# PX4FMUv2_4_5.net
KiCad netlist of a schematic drawn in EAGLE
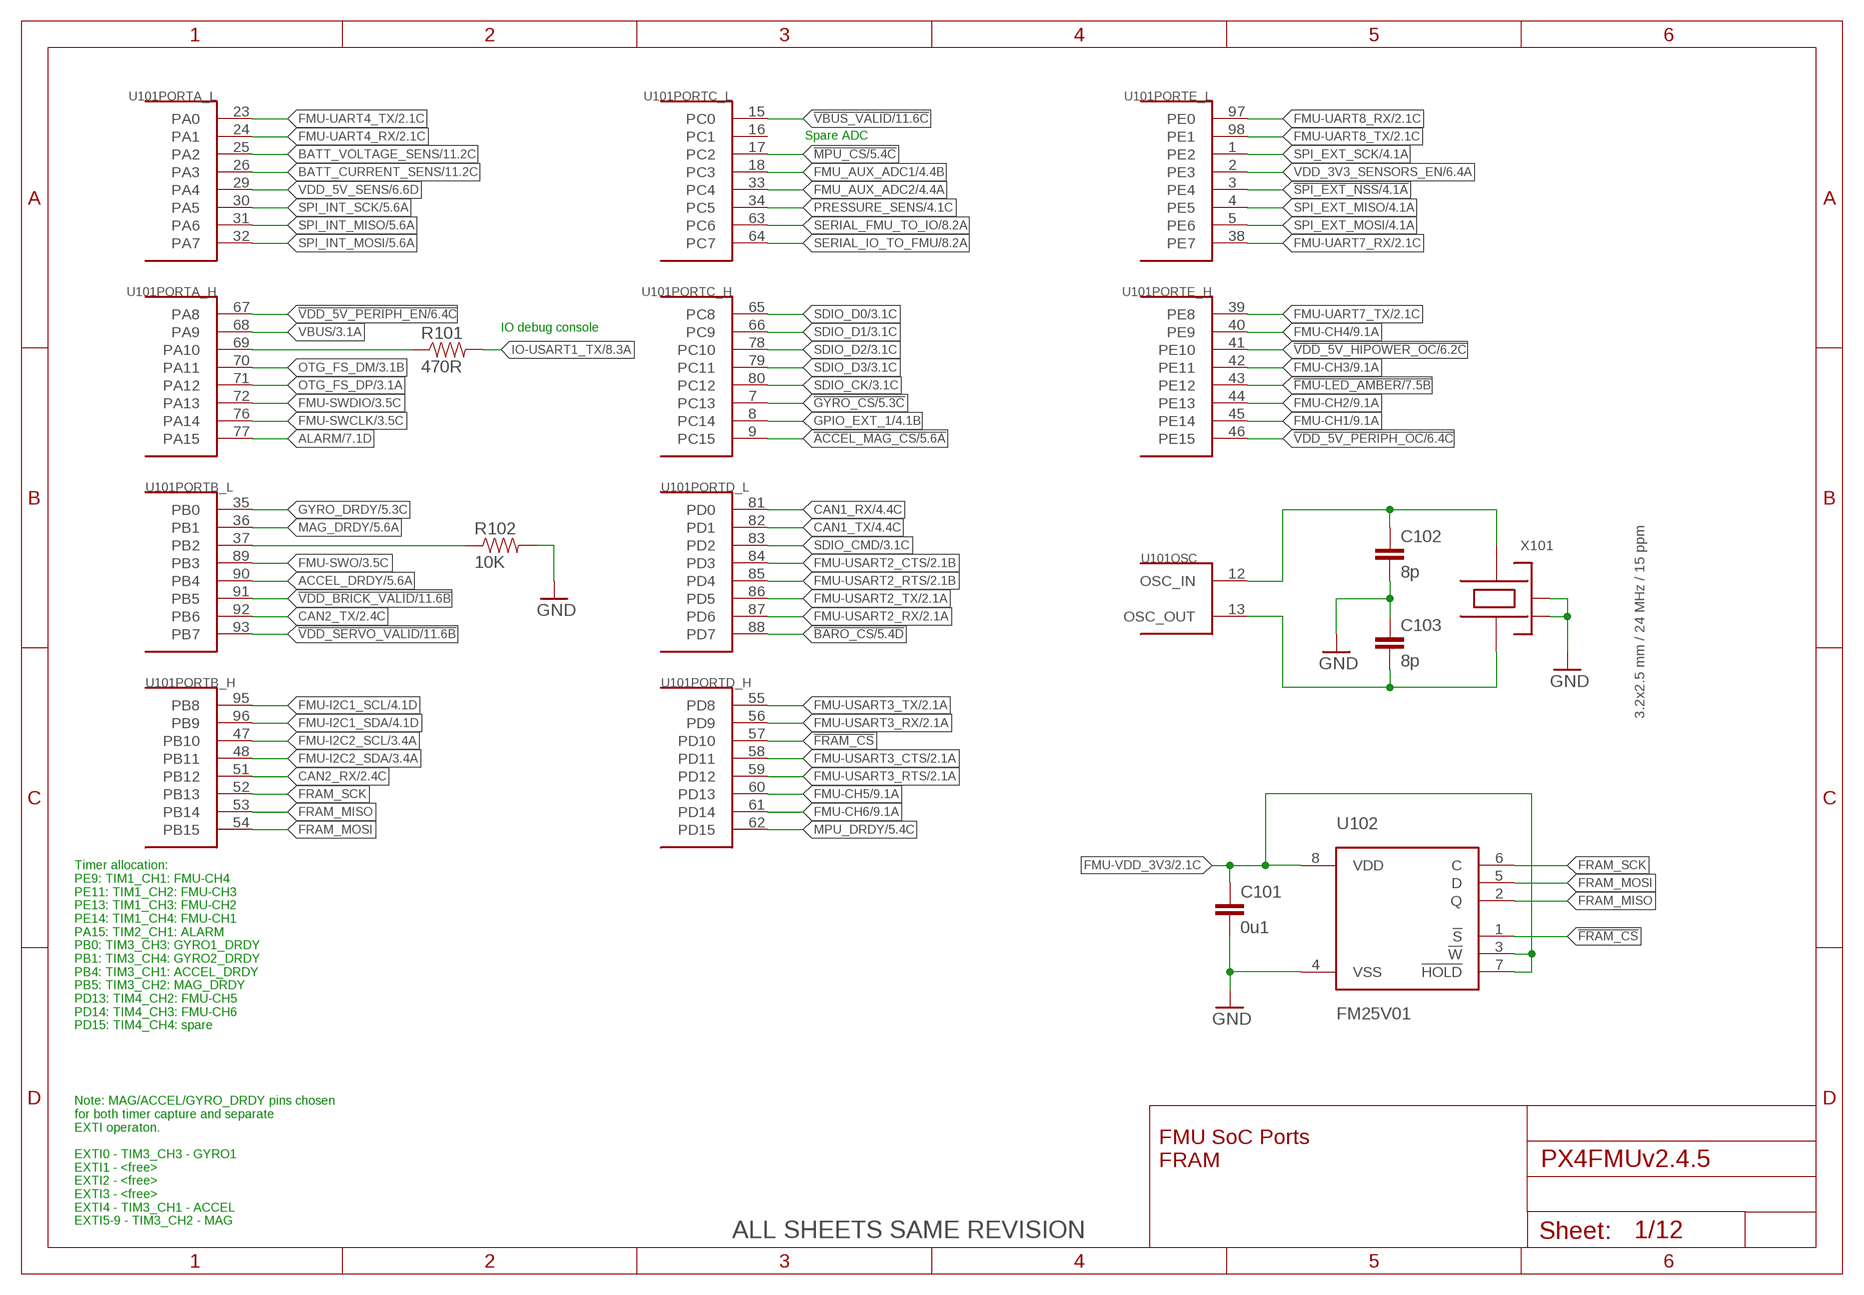
[diagram p0: schematic, sheet 1]
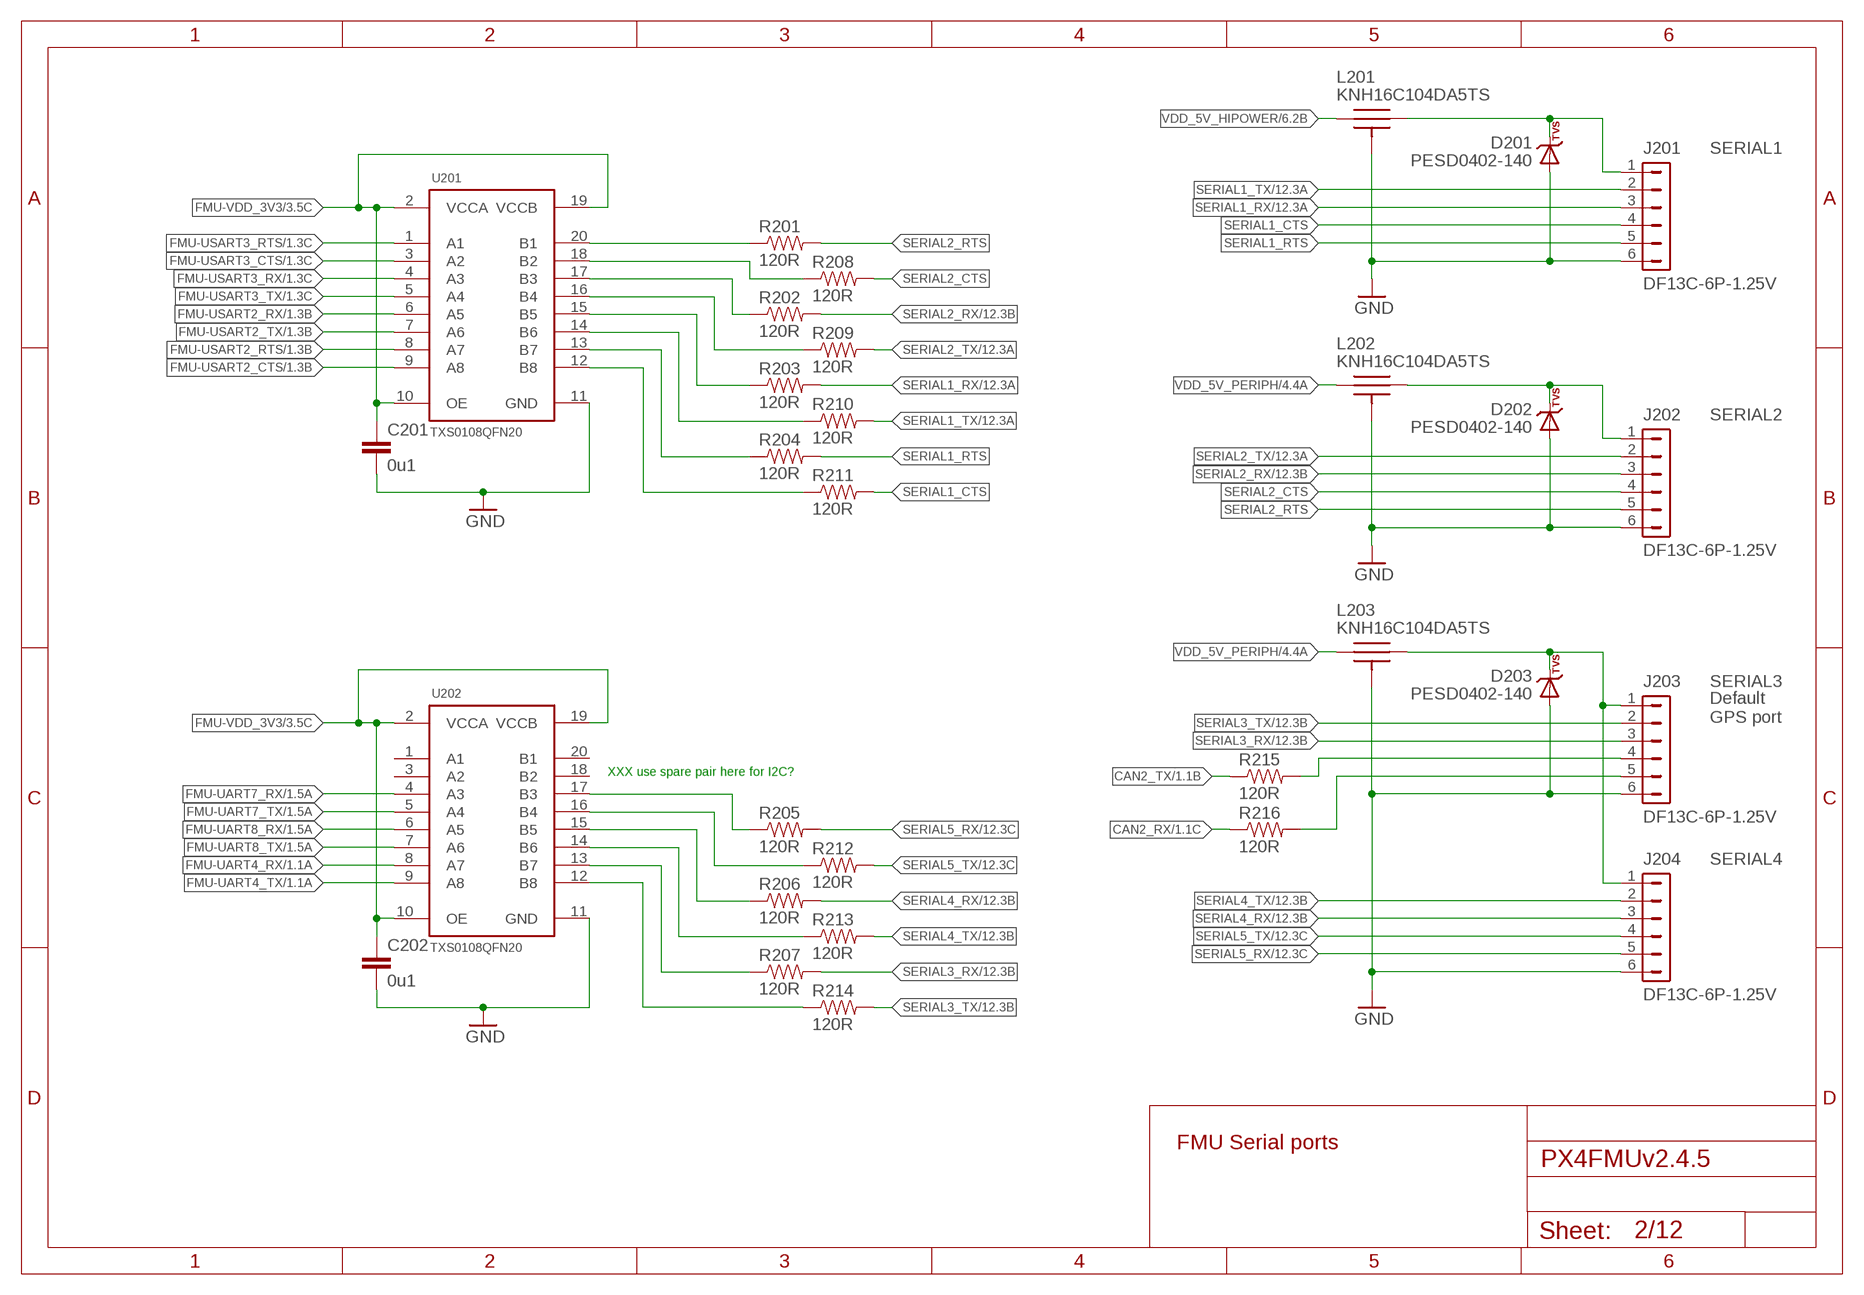
[diagram p1: schematic, sheet 2]
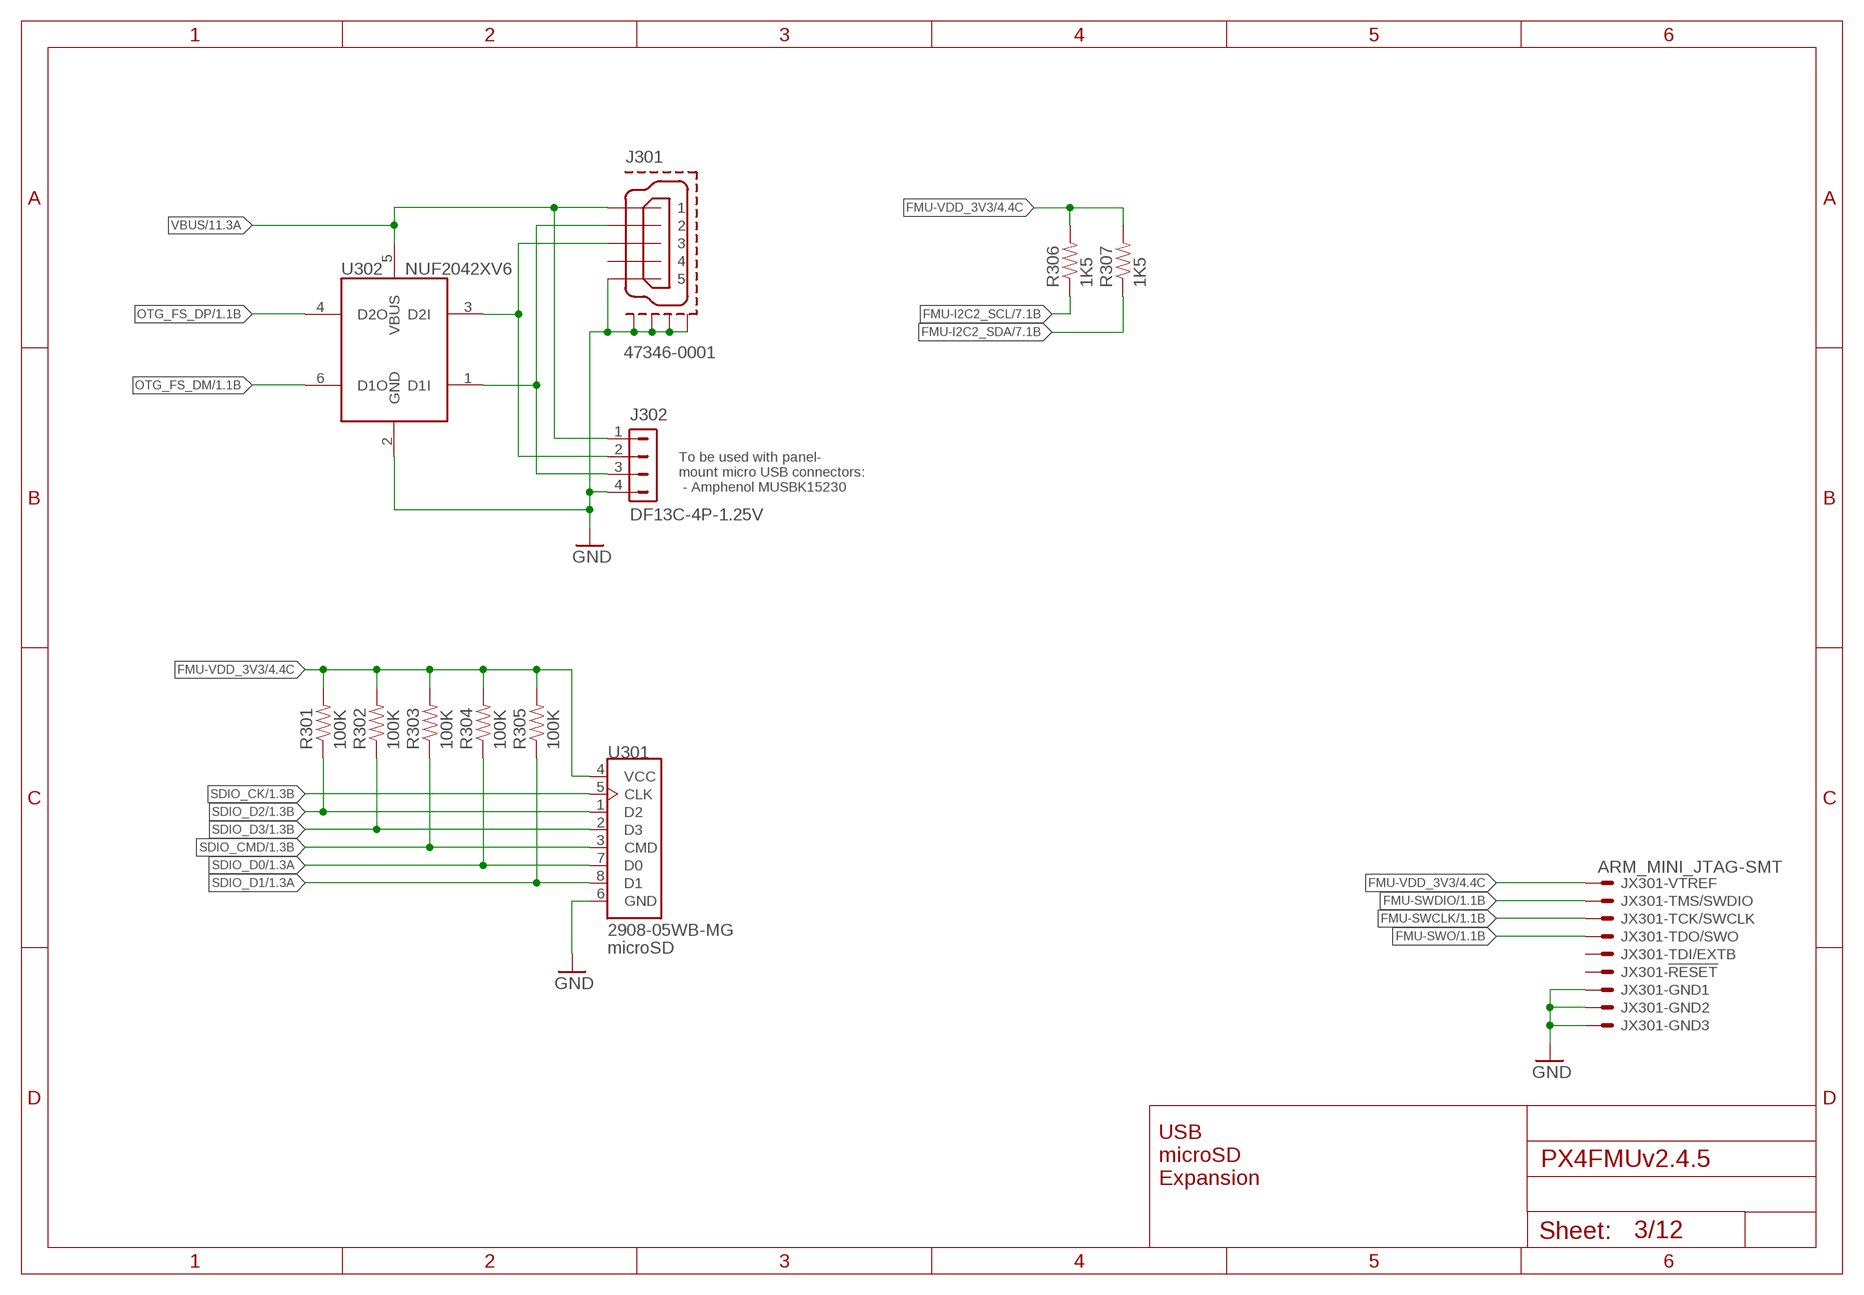
[diagram p2: schematic, sheet 3]
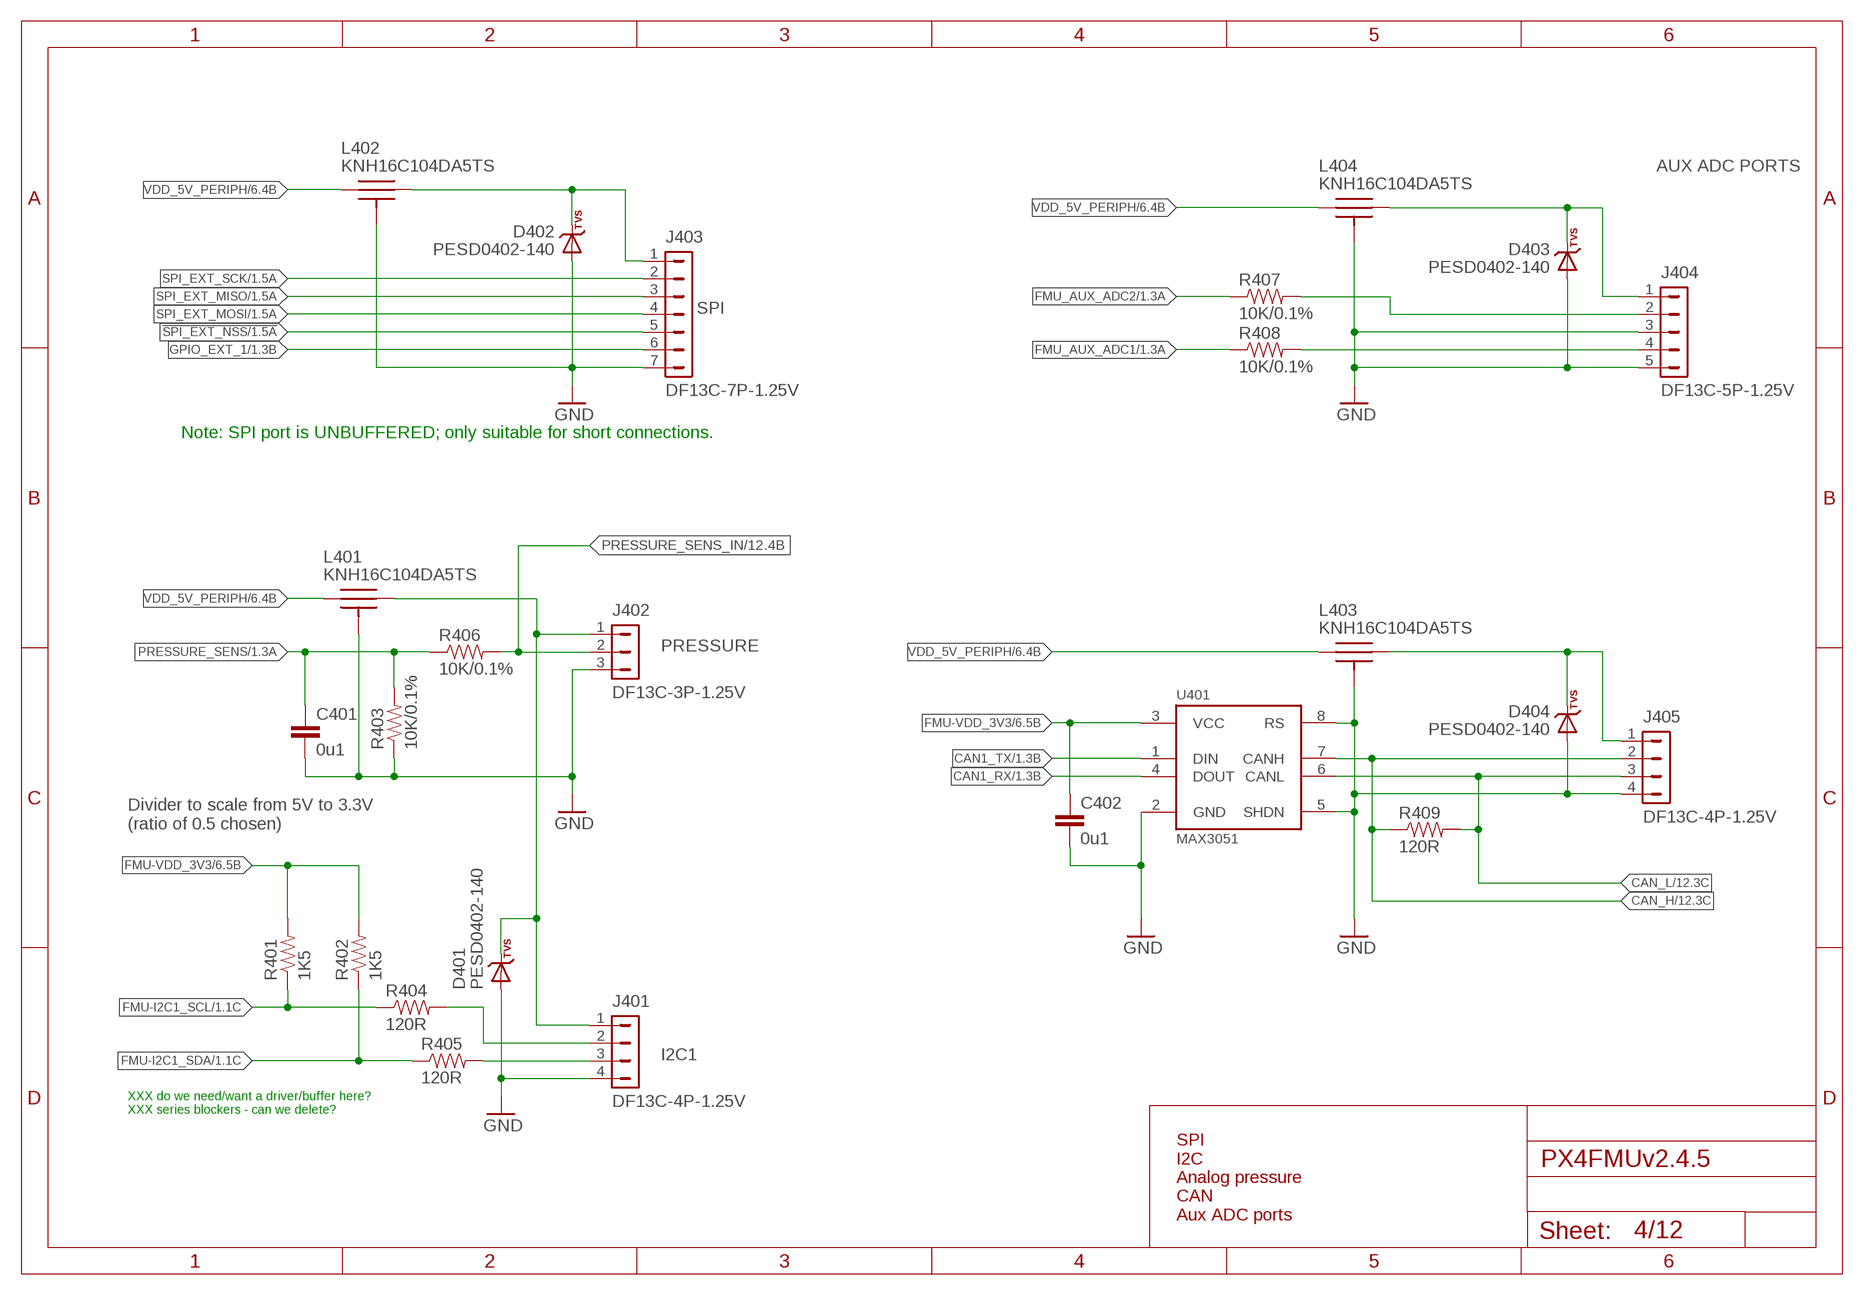
[diagram p3: schematic, sheet 4]
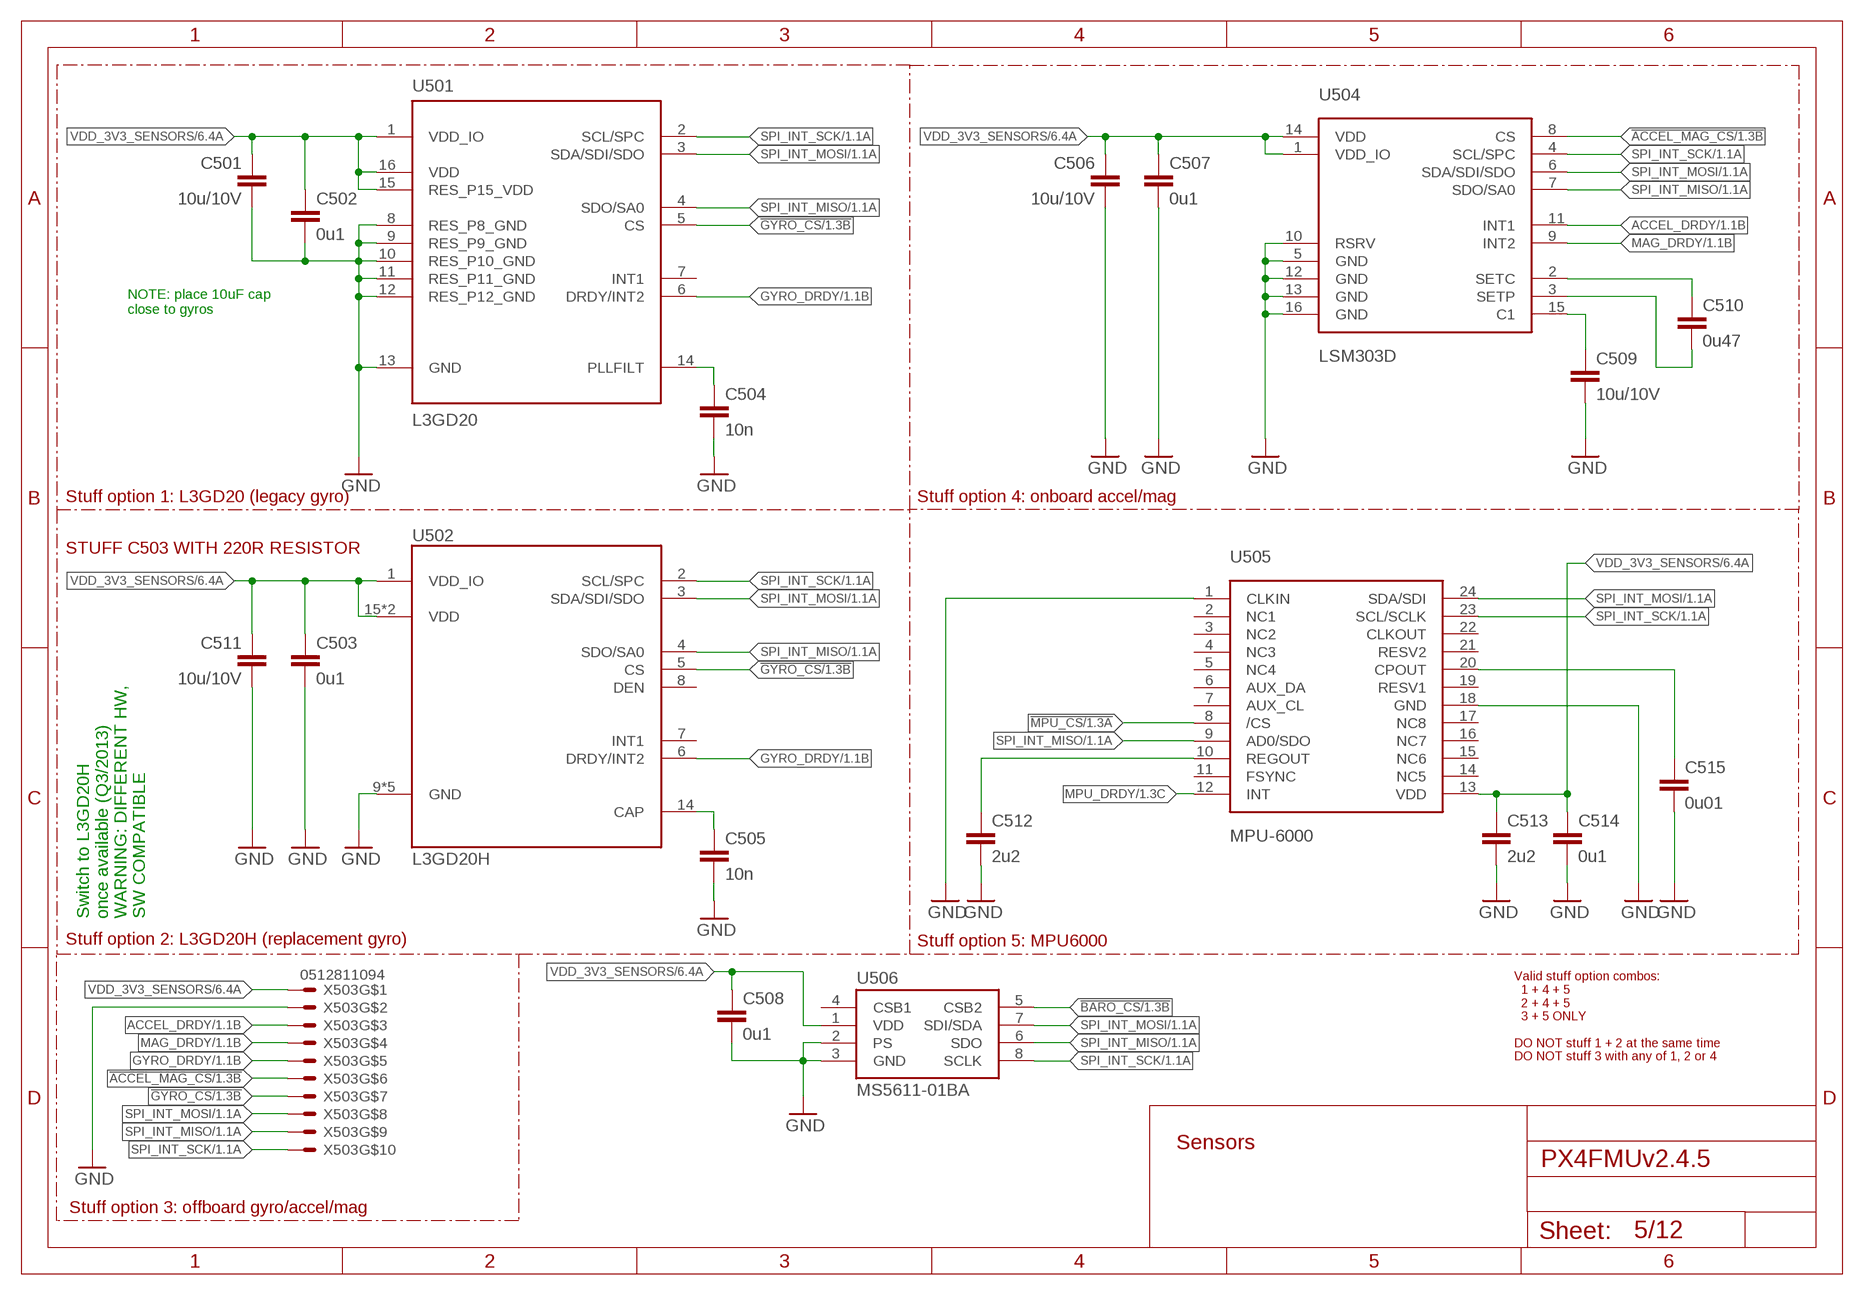
[diagram p4: schematic, sheet 5]
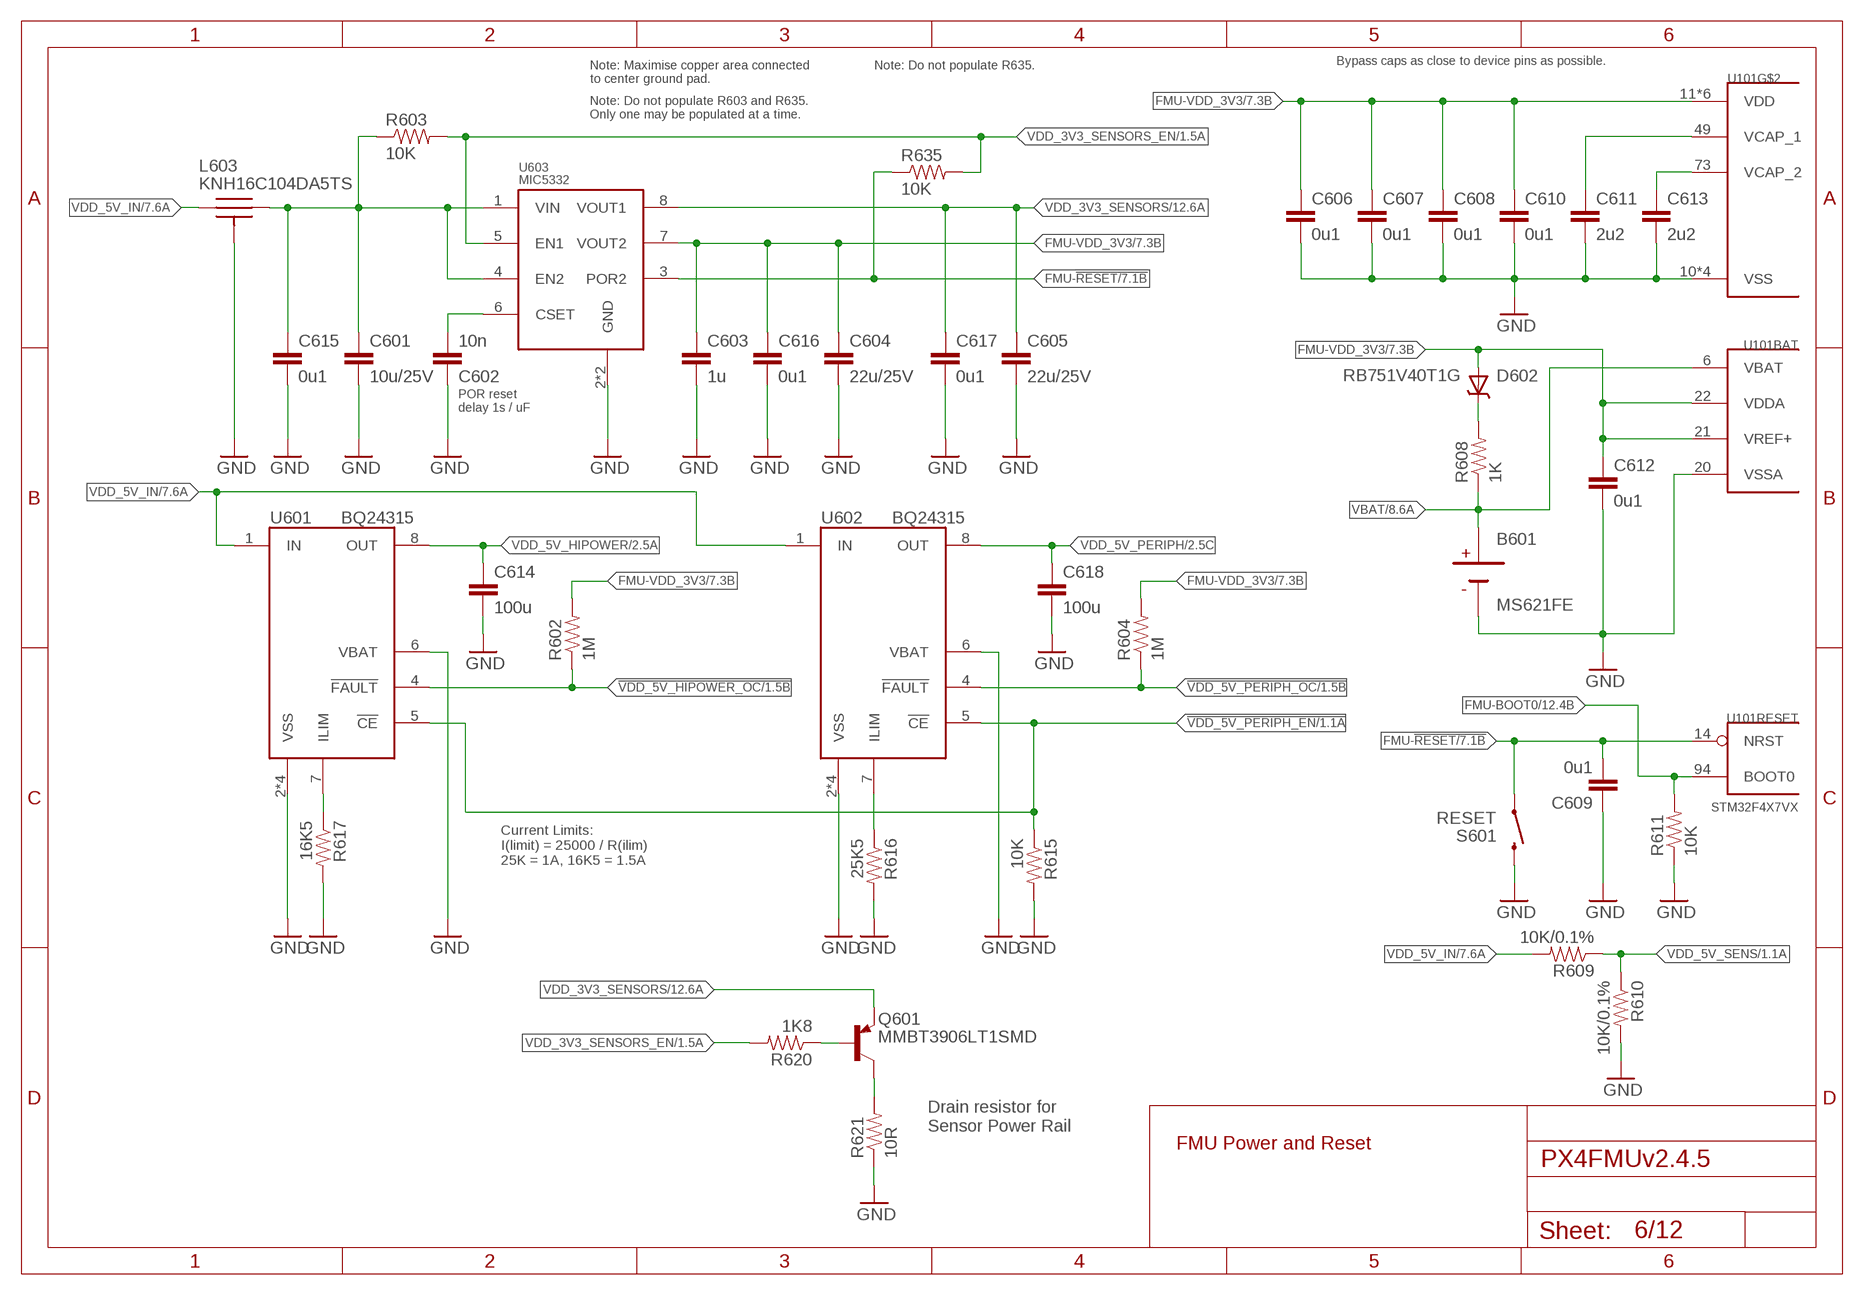
[diagram p5: schematic, sheet 6]
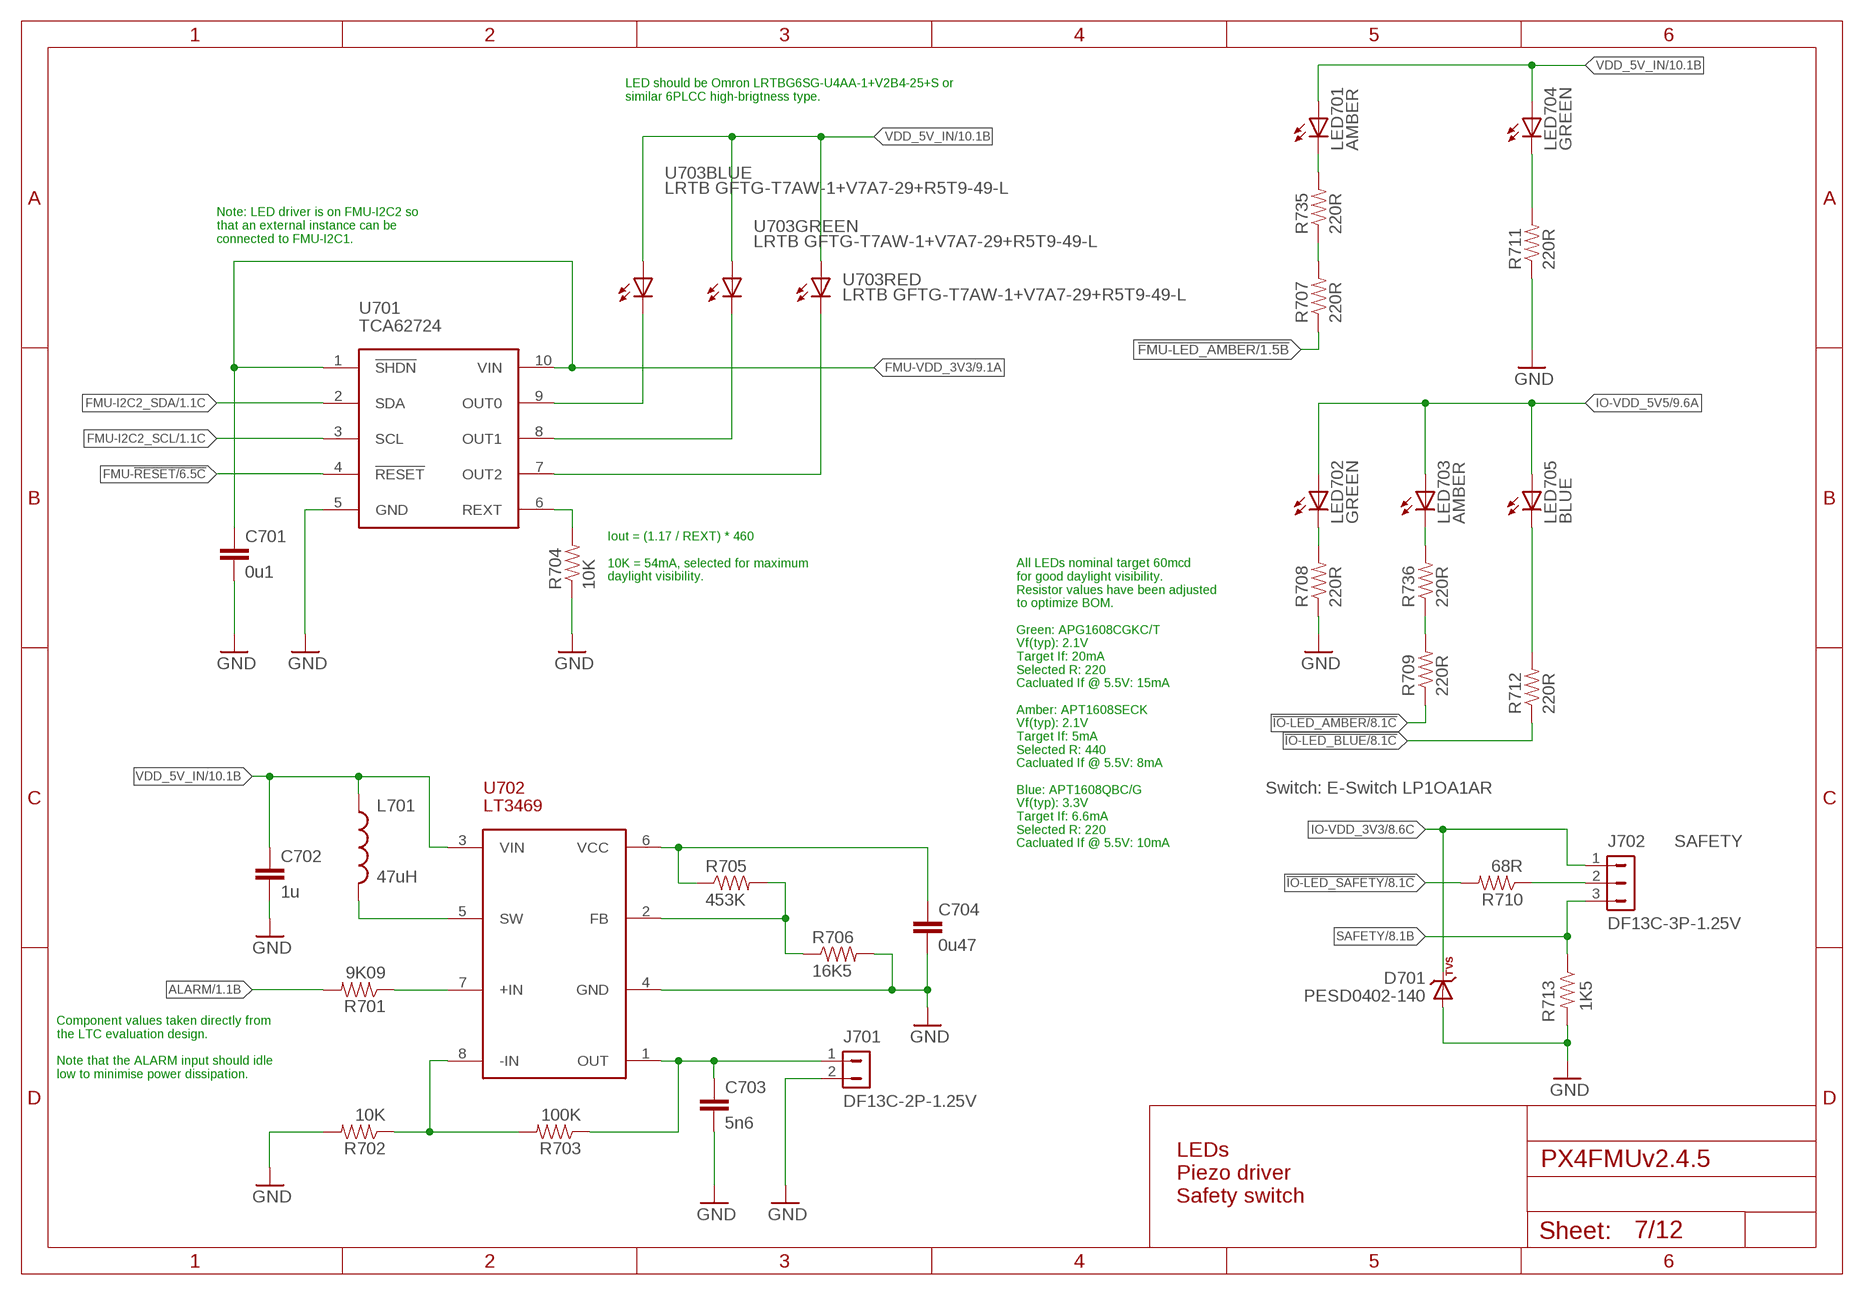
[diagram p6: schematic, sheet 7]
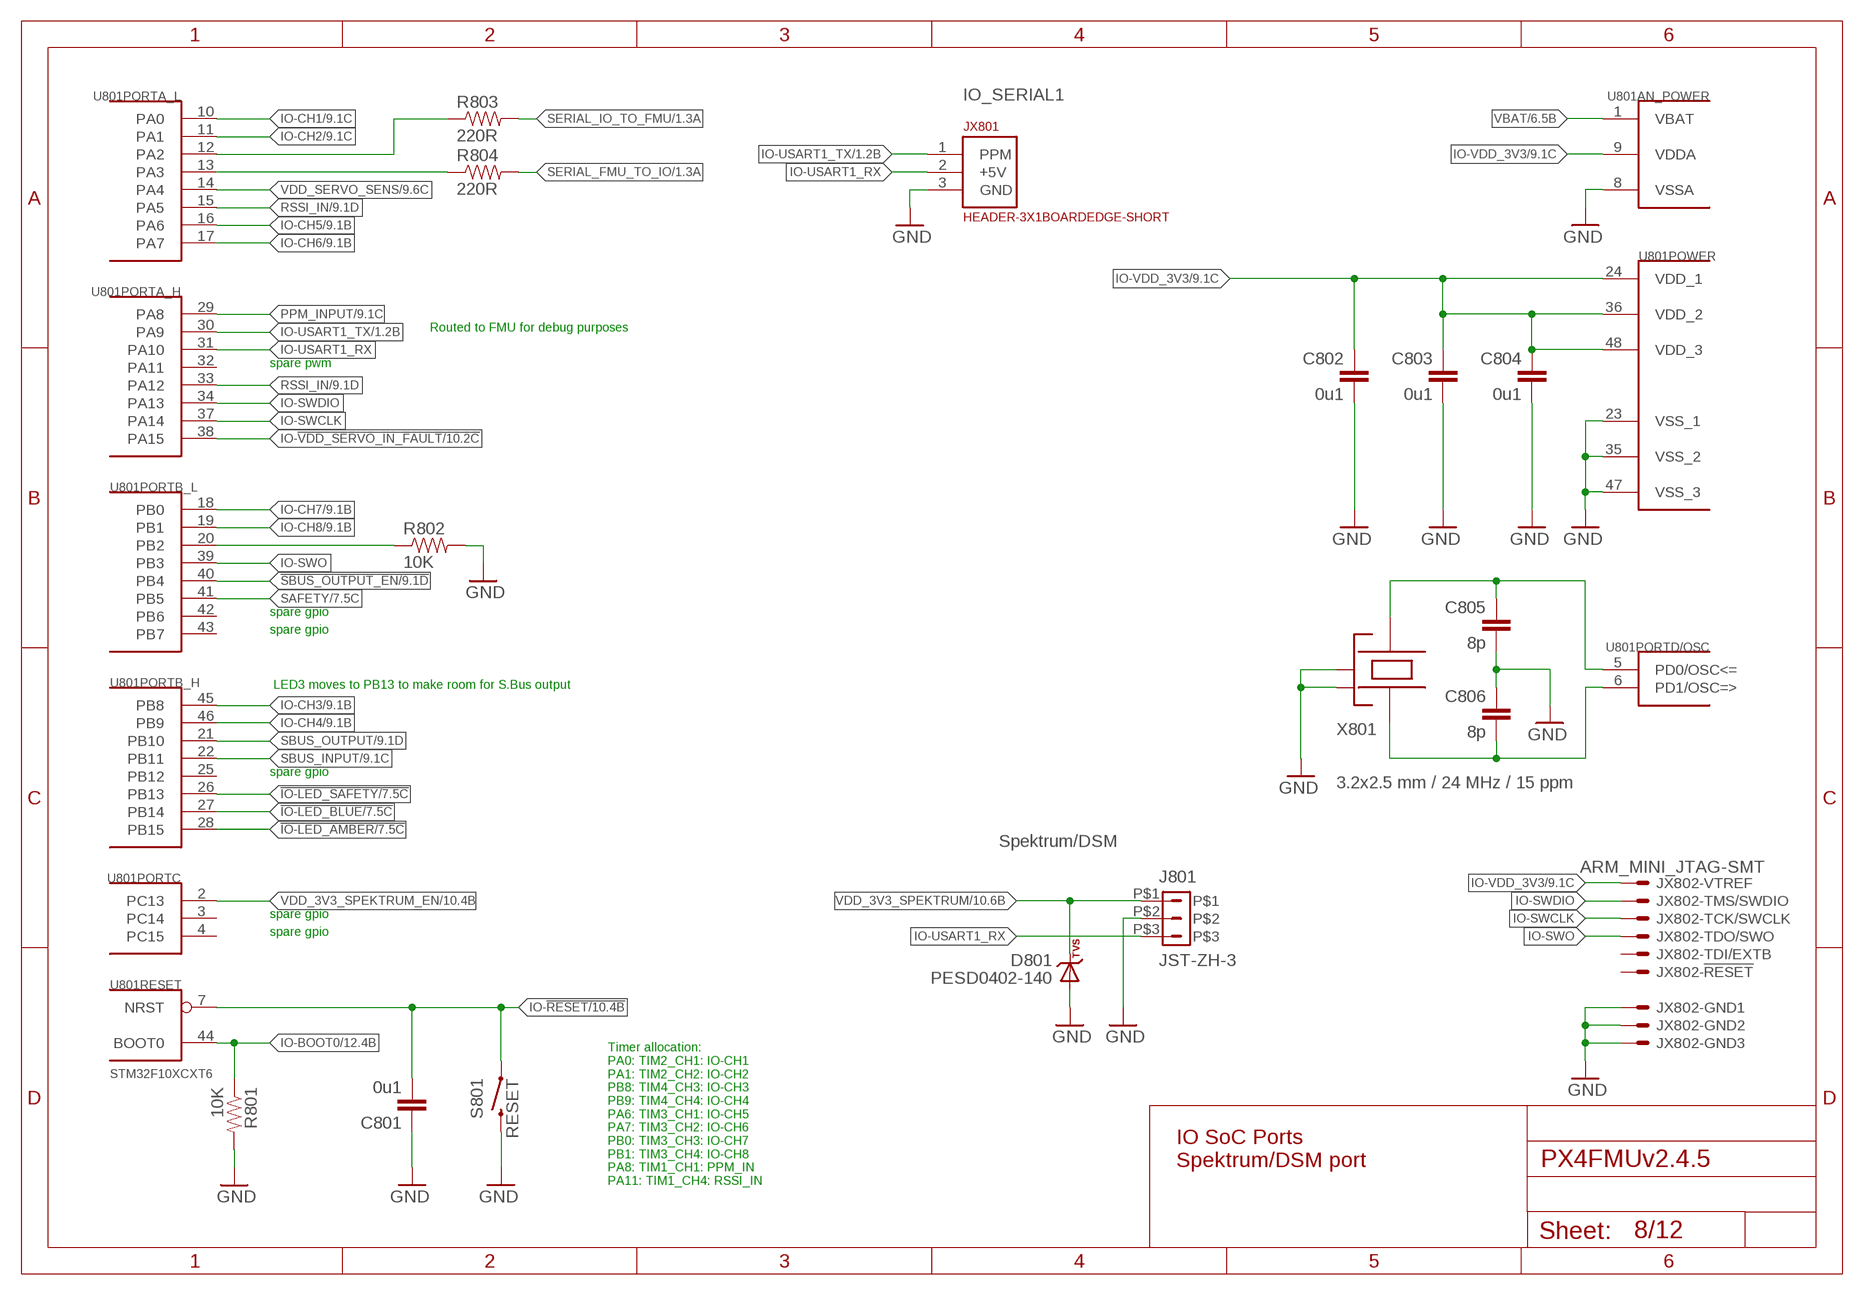
[diagram p7: schematic, sheet 8]
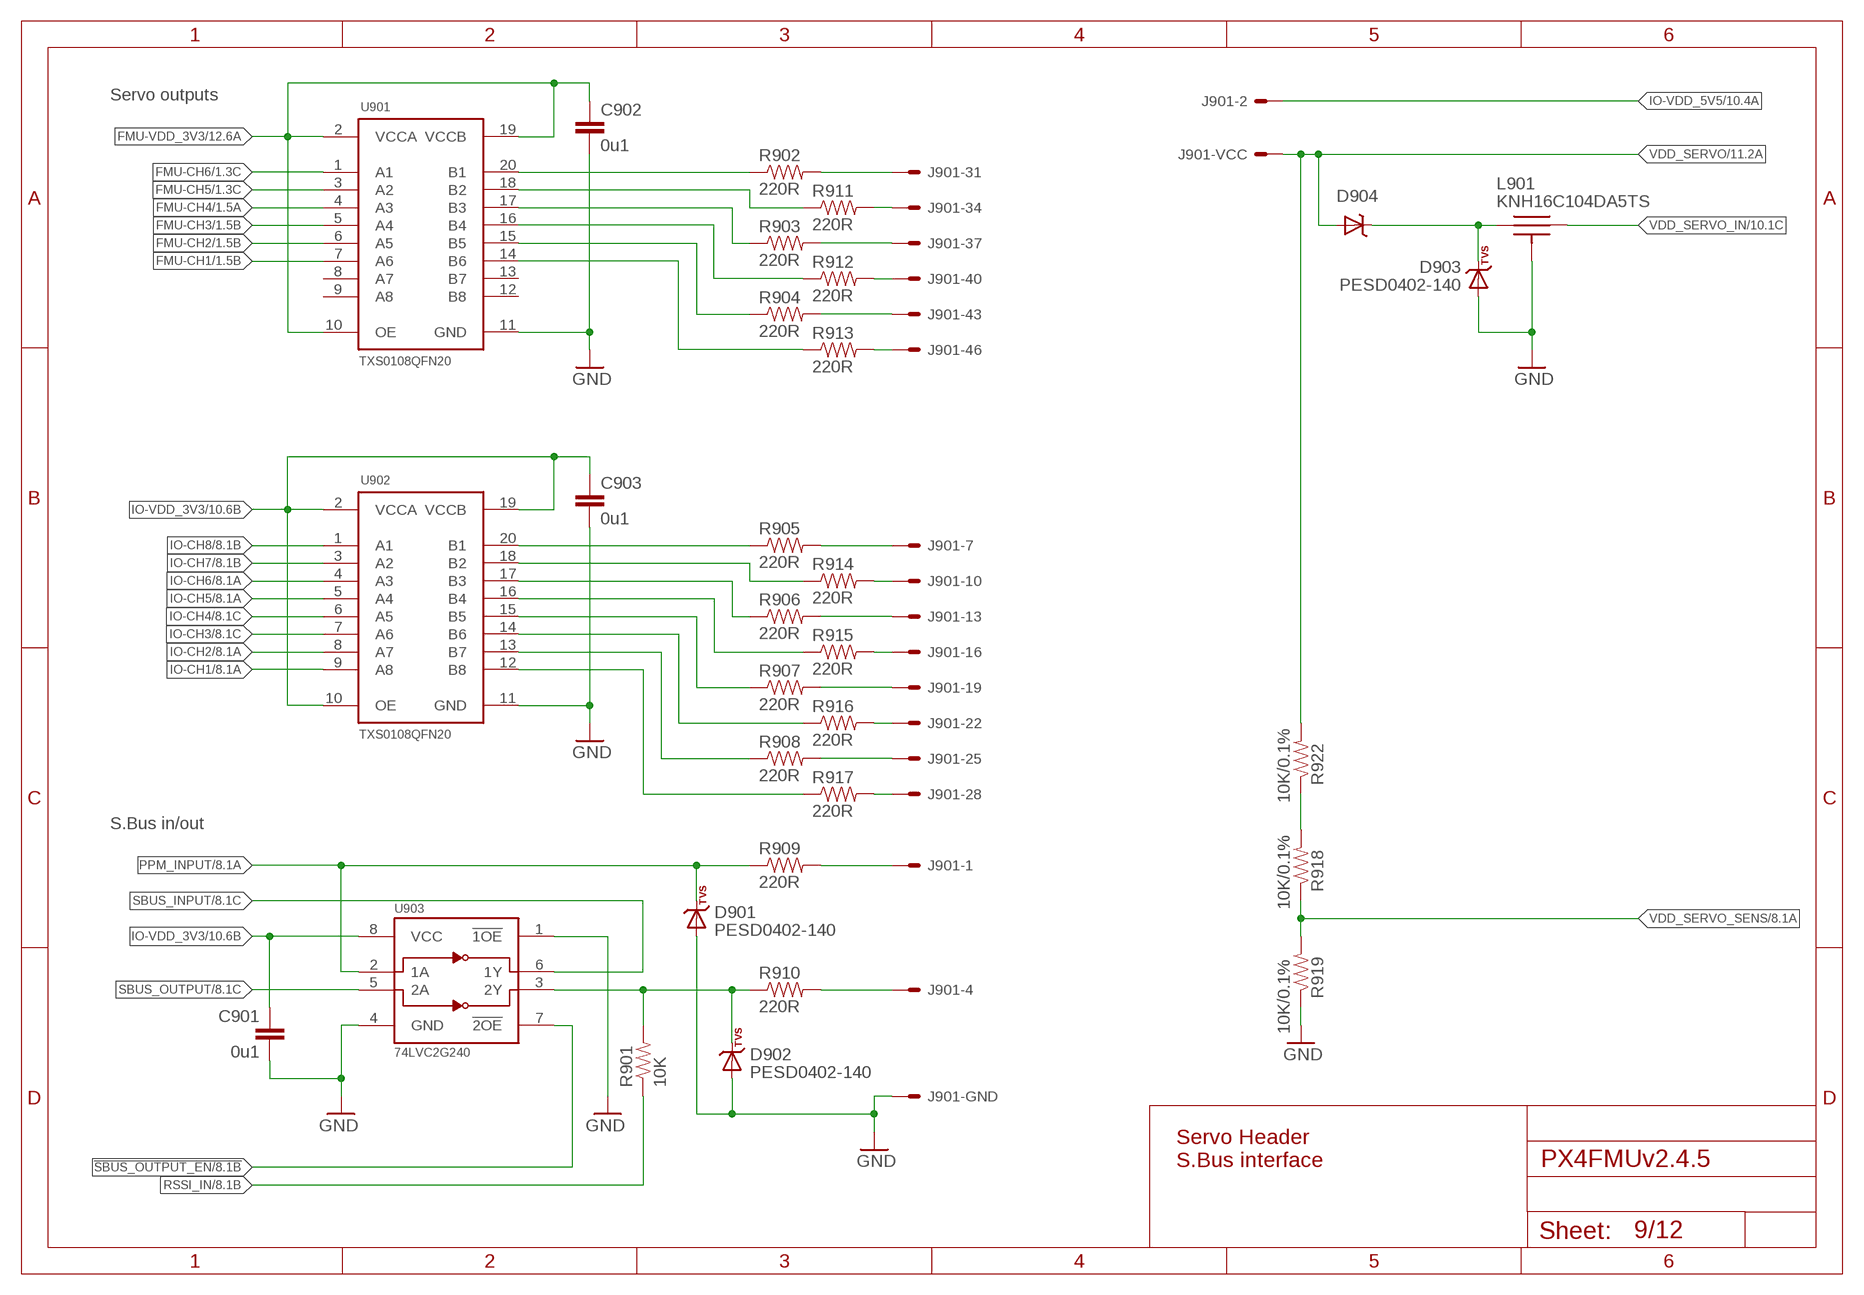
[diagram p8: schematic, sheet 9]
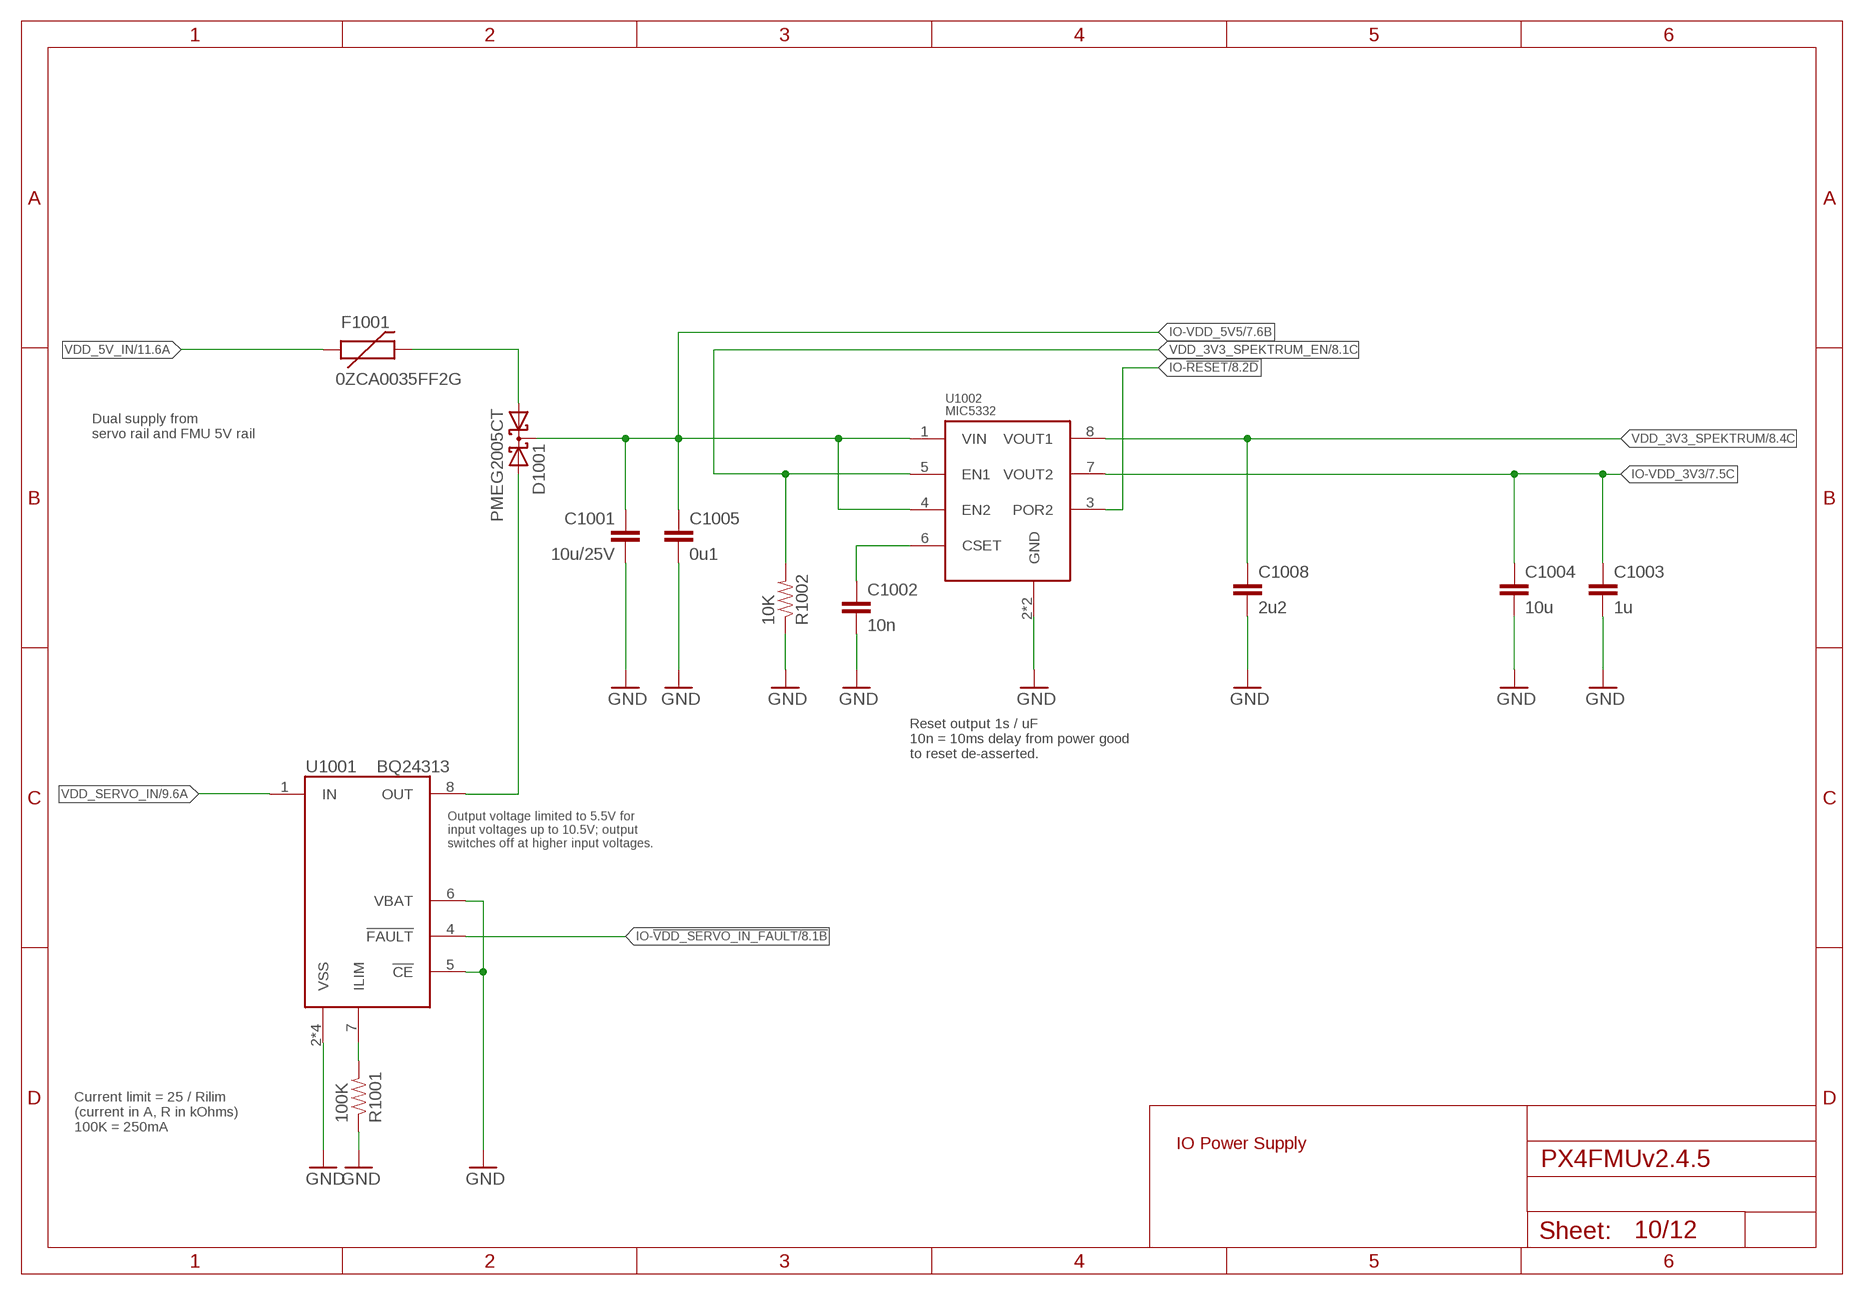
[diagram p9: schematic, sheet 10]
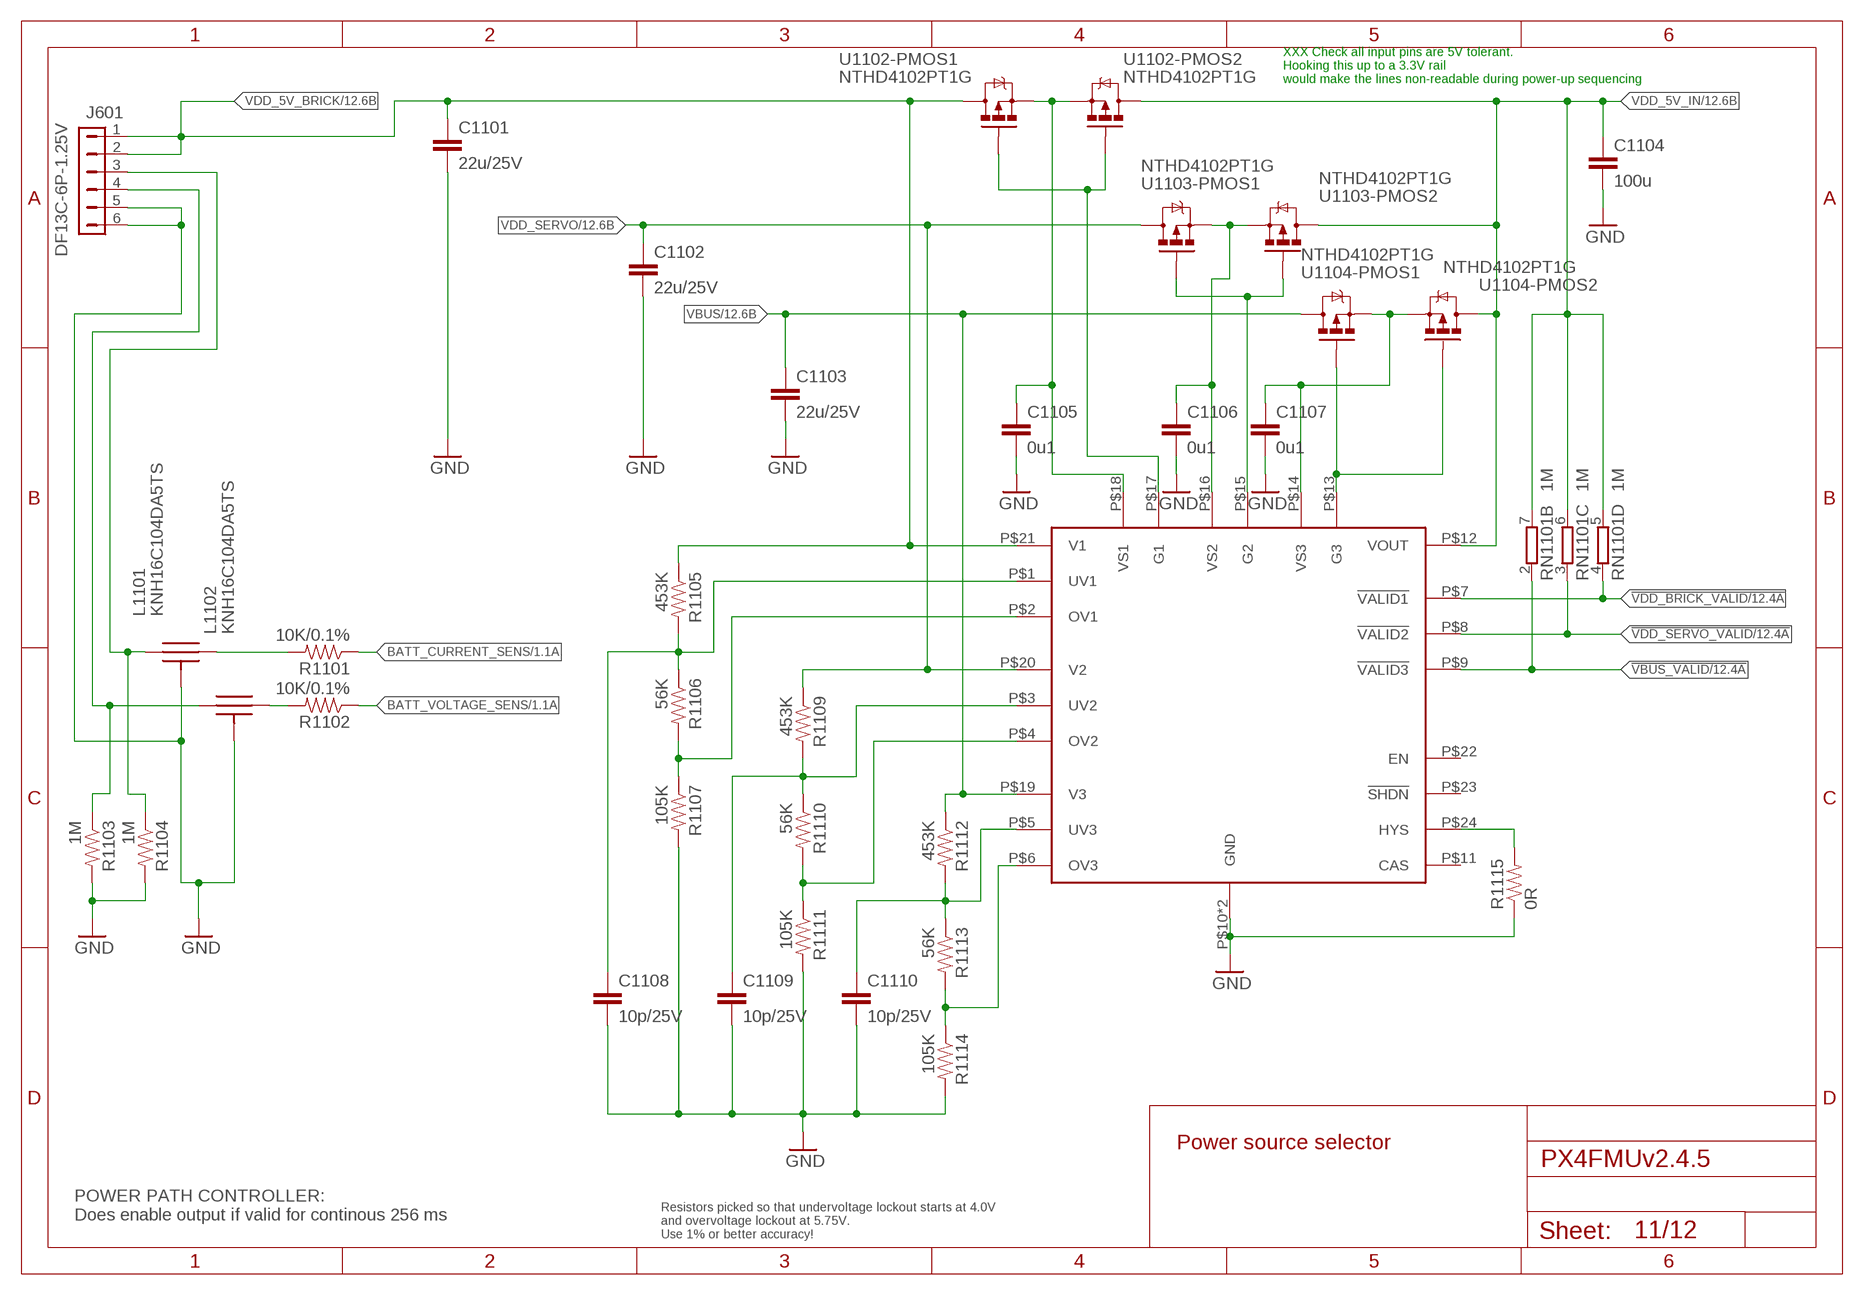
[diagram p10: schematic, sheet 11]
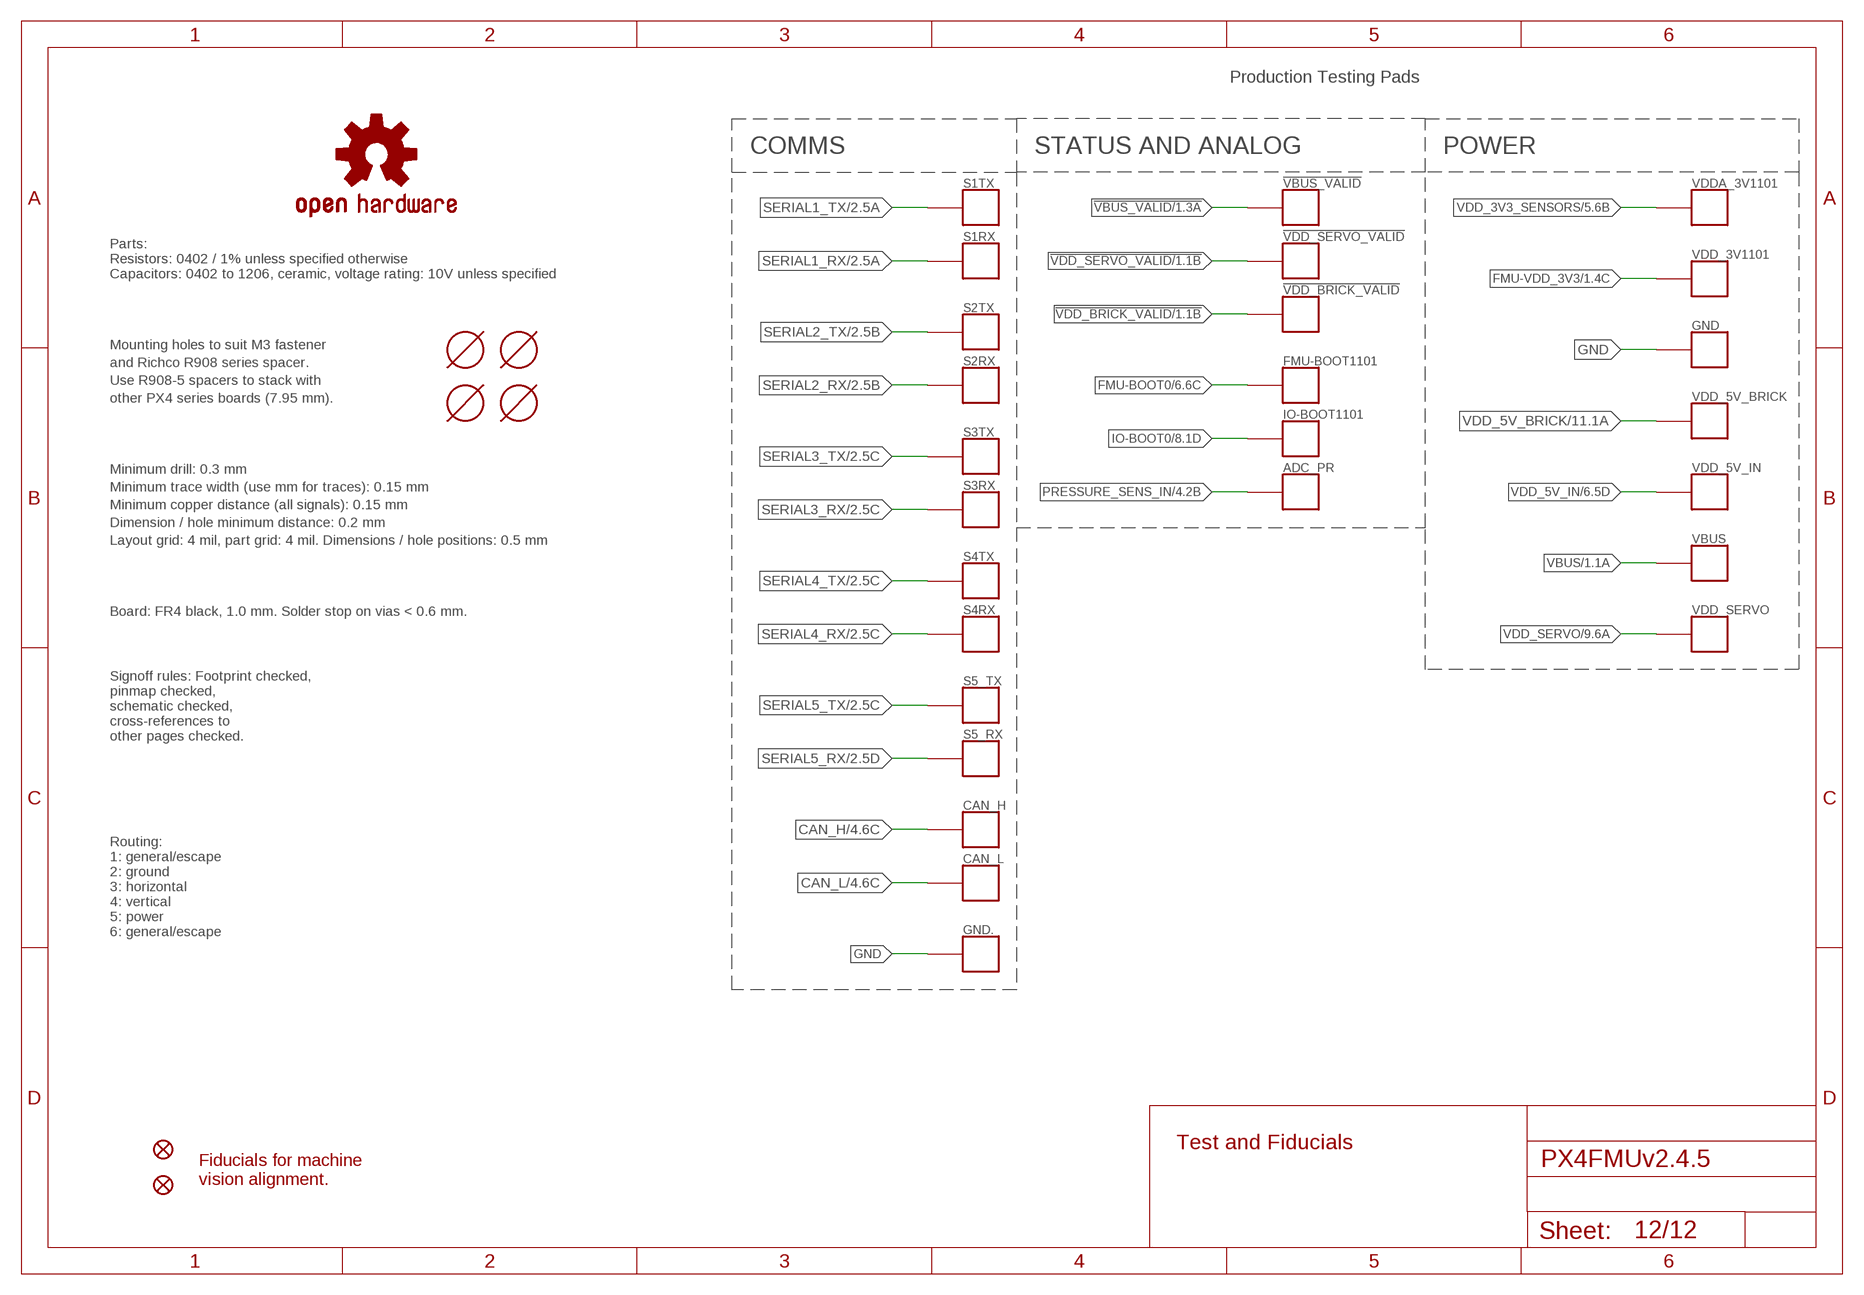
[diagram p11: schematic, sheet 12]

(export (version "E")
  (design (tool "Eeschema 10.0.6"))
  (components
    (comp (ref "C1001")
      (value "10u/25V")
      (footprint "eagle-import:0805-CAP")
      (fields (field (name "PARTNO") "CL21A106KAYNNNE"))
      (libsource (lib "eagle-import") (part "CAP0805"))
    )
    (comp (ref "C1002")
      (value "10n")
      (footprint "eagle-import:0402-CAP")
      (fields (field (name "PARTNO") "CC0402KRX7R7BB103"))
      (libsource (lib "eagle-import") (part "CAP0402"))
    )
    (comp (ref "C1003")
      (value "1u")
      (footprint "eagle-import:0603-CAP")
      (fields (field (name "PARTNO") "CC0603ZRY5V7BB105"))
      (libsource (lib "eagle-import") (part "CAP0603"))
    )
    (comp (ref "C1004")
      (value "10u")
      (footprint "eagle-import:0603-CAP")
      (fields (field (name "PARTNO") "C1608X5R1A106K080AC"))
      (libsource (lib "eagle-import") (part "CAP0603"))
    )
    (comp (ref "C1005")
      (value "0u1")
      (footprint "eagle-import:0402-CAP")
      (fields (field (name "PARTNO") "CC0402ZRY5V7BB104"))
      (libsource (lib "eagle-import") (part "CAP0402"))
    )
    (comp (ref "C1008")
      (value "2u2")
      (footprint "eagle-import:0402-CAP")
      (fields (field (name "PARTNO") "C1005X6S1C225K050BC"))
      (libsource (lib "eagle-import") (part "CAP0402"))
    )
    (comp (ref "D1001")
      (value "PMEG2005CT")
      (footprint "eagle-import:SOT23-3")
      (libsource (lib "eagle-import") (part "PMEG2005CT"))
    )
    (comp (ref "F1001")
      (value "0ZCA0035FF2G")
      (footprint "eagle-import:PTC-1206")
      (libsource (lib "eagle-import") (part "PTCSMD"))
    )
    (comp (ref "R1001")
      (value "100K")
      (footprint "eagle-import:0402-RES")
      (fields (field (name "PARTNO") "RC0402FR-07100KL"))
      (libsource (lib "eagle-import") (part "RESISTOR0402-RES"))
    )
    (comp (ref "R1002")
      (value "10K")
      (footprint "eagle-import:0402-RES")
      (fields (field (name "PARTNO") "RC0402FR-0710KL"))
      (libsource (lib "eagle-import") (part "RESISTOR0402-RES"))
    )
    (comp (ref "U1001")
      (value "BQ24313")
      (footprint "eagle-import:QFN8-DSG")
      (fields (field (name "PARTNO") "BQ24313DSGT"))
      (libsource (lib "eagle-import") (part "BQ24313"))
    )
    (comp (ref "U1002")
      (value "MIC5332")
      (footprint "eagle-import:MLF-8-EPAD")
      (fields (field (name "PARTNO") "MIC5332-SSYMT"))
      (libsource (lib "eagle-import") (part "MIC5332"))
    )
    (comp (ref "C201")
      (value "0u1")
      (footprint "eagle-import:0402-CAP")
      (fields (field (name "PARTNO") "CC0402ZRY5V7BB104"))
      (libsource (lib "eagle-import") (part "CAP0402"))
    )
    (comp (ref "C202")
      (value "0u1")
      (footprint "eagle-import:0402-CAP")
      (fields (field (name "PARTNO") "CC0402ZRY5V7BB104"))
      (libsource (lib "eagle-import") (part "CAP0402"))
    )
    (comp (ref "D201")
      (value "PESD0402-140")
      (footprint "eagle-import:0402-TVS")
      (libsource (lib "eagle-import") (part "DIODE-TVS"))
    )
    (comp (ref "D202")
      (value "PESD0402-140")
      (footprint "eagle-import:0402-TVS")
      (libsource (lib "eagle-import") (part "DIODE-TVS"))
    )
    (comp (ref "D203")
      (value "PESD0402-140")
      (footprint "eagle-import:0402-TVS")
      (libsource (lib "eagle-import") (part "DIODE-TVS"))
    )
    (comp (ref "J201")
      (value "DF13C-6P-1.25V")
      (footprint "eagle-import:DF13C-6P-1.25V")
      (fields (field (name "PARTNO") "DF13C-6P-1.25V(20)"))
      (libsource (lib "eagle-import") (part "DF13-6P-1.25V"))
    )
    (comp (ref "J202")
      (value "DF13C-6P-1.25V")
      (footprint "eagle-import:DF13C-6P-1.25V")
      (fields (field (name "PARTNO") "DF13C-6P-1.25V(20)"))
      (libsource (lib "eagle-import") (part "DF13-6P-1.25V"))
    )
    (comp (ref "J203")
      (value "DF13C-6P-1.25V")
      (footprint "eagle-import:DF13C-6P-1.25V")
      (fields (field (name "PARTNO") "DF13C-6P-1.25V(20)"))
      (libsource (lib "eagle-import") (part "DF13-6P-1.25V"))
    )
    (comp (ref "J204")
      (value "DF13C-6P-1.25V")
      (footprint "eagle-import:DF13C-6P-1.25V")
      (fields (field (name "PARTNO") "DF13C-6P-1.25V(20)"))
      (libsource (lib "eagle-import") (part "DF13-6P-1.25V"))
    )
    (comp (ref "L201")
      (value "KNH16C104DA5TS")
      (footprint "eagle-import:KYOCERA-KNH16-DA")
      (libsource (lib "eagle-import") (part "KNH16C104DA5TS"))
    )
    (comp (ref "L202")
      (value "KNH16C104DA5TS")
      (footprint "eagle-import:KYOCERA-KNH16-DA")
      (libsource (lib "eagle-import") (part "KNH16C104DA5TS"))
    )
    (comp (ref "L203")
      (value "KNH16C104DA5TS")
      (footprint "eagle-import:KYOCERA-KNH16-DA")
      (libsource (lib "eagle-import") (part "KNH16C104DA5TS"))
    )
    (comp (ref "R201")
      (value "120R")
      (footprint "eagle-import:0402-RES")
      (fields (field (name "PARTNO") "RC0402FR-07120RL"))
      (libsource (lib "eagle-import") (part "RESISTOR0402-RES"))
    )
    (comp (ref "R202")
      (value "120R")
      (footprint "eagle-import:0402-RES")
      (fields (field (name "PARTNO") "RC0402FR-07120RL"))
      (libsource (lib "eagle-import") (part "RESISTOR0402-RES"))
    )
    (comp (ref "R203")
      (value "120R")
      (footprint "eagle-import:0402-RES")
      (fields (field (name "PARTNO") "RC0402FR-07120RL"))
      (libsource (lib "eagle-import") (part "RESISTOR0402-RES"))
    )
    (comp (ref "R204")
      (value "120R")
      (footprint "eagle-import:0402-RES")
      (fields (field (name "PARTNO") "RC0402FR-07120RL"))
      (libsource (lib "eagle-import") (part "RESISTOR0402-RES"))
    )
    (comp (ref "R205")
      (value "120R")
      (footprint "eagle-import:0402-RES")
      (fields (field (name "PARTNO") "RC0402FR-07120RL"))
      (libsource (lib "eagle-import") (part "RESISTOR0402-RES"))
    )
    (comp (ref "R206")
      (value "120R")
      (footprint "eagle-import:0402-RES")
      (fields (field (name "PARTNO") "RC0402FR-07120RL"))
      (libsource (lib "eagle-import") (part "RESISTOR0402-RES"))
    )
    (comp (ref "R207")
      (value "120R")
      (footprint "eagle-import:0402-RES")
      (fields (field (name "PARTNO") "RC0402FR-07120RL"))
      (libsource (lib "eagle-import") (part "RESISTOR0402-RES"))
    )
    (comp (ref "R208")
      (value "120R")
      (footprint "eagle-import:0402-RES")
      (fields (field (name "PARTNO") "RC0402FR-07120RL"))
      (libsource (lib "eagle-import") (part "RESISTOR0402-RES"))
    )
    (comp (ref "R209")
      (value "120R")
      (footprint "eagle-import:0402-RES")
      (fields (field (name "PARTNO") "RC0402FR-07120RL"))
      (libsource (lib "eagle-import") (part "RESISTOR0402-RES"))
    )
    (comp (ref "R210")
      (value "120R")
      (footprint "eagle-import:0402-RES")
      (fields (field (name "PARTNO") "RC0402FR-07120RL"))
      (libsource (lib "eagle-import") (part "RESISTOR0402-RES"))
    )
    (comp (ref "R211")
      (value "120R")
      (footprint "eagle-import:0402-RES")
      (fields (field (name "PARTNO") "RC0402FR-07120RL"))
      (libsource (lib "eagle-import") (part "RESISTOR0402-RES"))
    )
    (comp (ref "R212")
      (value "120R")
      (footprint "eagle-import:0402-RES")
      (fields (field (name "PARTNO") "RC0402FR-07120RL"))
      (libsource (lib "eagle-import") (part "RESISTOR0402-RES"))
    )
    (comp (ref "R213")
      (value "120R")
      (footprint "eagle-import:0402-RES")
      (fields (field (name "PARTNO") "RC0402FR-07120RL"))
      (libsource (lib "eagle-import") (part "RESISTOR0402-RES"))
    )
    (comp (ref "R214")
      (value "120R")
      (footprint "eagle-import:0402-RES")
      (fields (field (name "PARTNO") "RC0402FR-07120RL"))
      (libsource (lib "eagle-import") (part "RESISTOR0402-RES"))
    )
    (comp (ref "R215")
      (value "120R")
      (footprint "eagle-import:0402-RES")
      (fields (field (name "PARTNO") "RC0402FR-07120RL"))
      (libsource (lib "eagle-import") (part "RESISTOR0402-RES"))
    )
    (comp (ref "R216")
      (value "120R")
      (footprint "eagle-import:0402-RES")
      (fields (field (name "PARTNO") "RC0402FR-07120RL"))
      (libsource (lib "eagle-import") (part "RESISTOR0402-RES"))
    )
    (comp (ref "U201")
      (value "TXS0108QFN20")
      (footprint "eagle-import:QFN20-RGY")
      (fields (field (name "PARTNO") "TXS0108ERGYR"))
      (libsource (lib "eagle-import") (part "TXS0108QFN20"))
    )
    (comp (ref "U202")
      (value "TXS0108QFN20")
      (footprint "eagle-import:QFN20-RGY")
      (fields (field (name "PARTNO") "TXS0108ERGYR"))
      (libsource (lib "eagle-import") (part "TXS0108QFN20"))
    )
    (comp (ref "!VBUS_VALID")
      (value "PAD.04")
      (footprint "eagle-import:PAD.04X.04")
      (libsource (lib "eagle-import") (part "PAD.04"))
    )
    (comp (ref "!VDD_BRICK_VALID")
      (value "PAD.04")
      (footprint "eagle-import:PAD.04X.04")
      (libsource (lib "eagle-import") (part "PAD.04"))
    )
    (comp (ref "!VDD_SERVO_VALID")
      (value "PAD.04")
      (footprint "eagle-import:PAD.04X.04")
      (libsource (lib "eagle-import") (part "PAD.04"))
    )
    (comp (ref "ADC_PR")
      (value "PAD.04")
      (footprint "eagle-import:PAD.04X.04")
      (libsource (lib "eagle-import") (part "PAD.04"))
    )
    (comp (ref "CAN_H")
      (value "PAD.04")
      (footprint "eagle-import:PAD.04X.04")
      (libsource (lib "eagle-import") (part "PAD.04"))
    )
    (comp (ref "CAN_L")
      (value "PAD.04")
      (footprint "eagle-import:PAD.04X.04")
      (libsource (lib "eagle-import") (part "PAD.04"))
    )
    (comp (ref "FMU-BOOT1101")
      (value "PAD.04")
      (footprint "eagle-import:PAD.04X.04")
      (libsource (lib "eagle-import") (part "PAD.04"))
    )
    (comp (ref "GND")
      (value "PAD.04")
      (footprint "eagle-import:PAD.04X.04")
      (libsource (lib "eagle-import") (part "PAD.04"))
    )
    (comp (ref "GND.")
      (value "PAD.04")
      (footprint "eagle-import:PAD.04X.04")
      (libsource (lib "eagle-import") (part "PAD.04"))
    )
    (comp (ref "IO-BOOT1101")
      (value "PAD.04")
      (footprint "eagle-import:PAD.04X.04")
      (libsource (lib "eagle-import") (part "PAD.04"))
    )
    (comp (ref "JP1")
      (value "FIDUCIAL1.5X3")
      (footprint "eagle-import:FIDUCIAL-1.5X3")
      (libsource (lib "eagle-import") (part "FIDUCIAL1.5X3"))
    )
    (comp (ref "JP2")
      (value "FIDUCIAL1.5X3")
      (footprint "eagle-import:FIDUCIAL-1.5X3")
      (libsource (lib "eagle-import") (part "FIDUCIAL1.5X3"))
    )
    (comp (ref "M3_MOUNT1101")
      (value "MOUNT-HOLE3.1MM")
      (footprint "eagle-import:MOUNT-HOLE3.1")
      (libsource (lib "eagle-import") (part "MOUNT-HOLE3.1MM"))
    )
    (comp (ref "M3_MOUNT1102")
      (value "MOUNT-HOLE3.1MM")
      (footprint "eagle-import:MOUNT-HOLE3.1")
      (libsource (lib "eagle-import") (part "MOUNT-HOLE3.1MM"))
    )
    (comp (ref "M3_MOUNT1103")
      (value "MOUNT-HOLE3.1MM")
      (footprint "eagle-import:MOUNT-HOLE3.1")
      (libsource (lib "eagle-import") (part "MOUNT-HOLE3.1MM"))
    )
    (comp (ref "M3_MOUNT1104")
      (value "MOUNT-HOLE3.1MM")
      (footprint "eagle-import:MOUNT-HOLE3.1")
      (libsource (lib "eagle-import") (part "MOUNT-HOLE3.1MM"))
    )
    (comp (ref "OSHW_LOGO")
      (value "OSHW-LOGOS")
      (footprint "eagle-import:OSHW-LOGO-S")
      (libsource (lib "eagle-import") (part "OSHW-LOGOS"))
    )
    (comp (ref "S1RX")
      (value "PAD.04")
      (footprint "eagle-import:PAD.04X.04")
      (libsource (lib "eagle-import") (part "PAD.04"))
    )
    (comp (ref "S1TX")
      (value "PAD.04")
      (footprint "eagle-import:PAD.04X.04")
      (libsource (lib "eagle-import") (part "PAD.04"))
    )
    (comp (ref "S2RX")
      (value "PAD.04")
      (footprint "eagle-import:PAD.04X.04")
      (libsource (lib "eagle-import") (part "PAD.04"))
    )
    (comp (ref "S2TX")
      (value "PAD.04")
      (footprint "eagle-import:PAD.04X.04")
      (libsource (lib "eagle-import") (part "PAD.04"))
    )
    (comp (ref "S3RX")
      (value "PAD.04")
      (footprint "eagle-import:PAD.04X.04")
      (libsource (lib "eagle-import") (part "PAD.04"))
    )
    (comp (ref "S3TX")
      (value "PAD.04")
      (footprint "eagle-import:PAD.04X.04")
      (libsource (lib "eagle-import") (part "PAD.04"))
    )
    (comp (ref "S4RX")
      (value "PAD.04")
      (footprint "eagle-import:PAD.04X.04")
      (libsource (lib "eagle-import") (part "PAD.04"))
    )
    (comp (ref "S4TX")
      (value "PAD.04")
      (footprint "eagle-import:PAD.04X.04")
      (libsource (lib "eagle-import") (part "PAD.04"))
    )
    (comp (ref "S5_RX")
      (value "PAD.04")
      (footprint "eagle-import:PAD.04X.04")
      (libsource (lib "eagle-import") (part "PAD.04"))
    )
    (comp (ref "S5_TX")
      (value "PAD.04")
      (footprint "eagle-import:PAD.04X.04")
      (libsource (lib "eagle-import") (part "PAD.04"))
    )
    (comp (ref "VBUS")
      (value "PAD.04")
      (footprint "eagle-import:PAD.04X.04")
      (libsource (lib "eagle-import") (part "PAD.04"))
    )
    (comp (ref "VDDA_3V1101")
      (value "PAD.04")
      (footprint "eagle-import:PAD.04X.04")
      (libsource (lib "eagle-import") (part "PAD.04"))
    )
    (comp (ref "VDD_3V1101")
      (value "PAD.04")
      (footprint "eagle-import:PAD.04X.04")
      (libsource (lib "eagle-import") (part "PAD.04"))
    )
    (comp (ref "VDD_5V_BRICK")
      (value "PAD.04")
      (footprint "eagle-import:PAD.04X.04")
      (libsource (lib "eagle-import") (part "PAD.04"))
    )
    (comp (ref "VDD_5V_IN")
      (value "PAD.04")
      (footprint "eagle-import:PAD.04X.04")
      (libsource (lib "eagle-import") (part "PAD.04"))
    )
    (comp (ref "VDD_SERVO")
      (value "PAD.04")
      (footprint "eagle-import:PAD.04X.04")
      (libsource (lib "eagle-import") (part "PAD.04"))
    )
    (comp (ref "C101")
      (value "0u1")
      (footprint "eagle-import:0402-CAP")
      (fields (field (name "PARTNO") "CC0402ZRY5V7BB104"))
      (libsource (lib "eagle-import") (part "CAP0402"))
    )
    (comp (ref "C102")
      (value "8p")
      (footprint "eagle-import:0402-CAP")
      (fields (field (name "PARTNO") "C1005C0G1H080C"))
      (libsource (lib "eagle-import") (part "CAP0402"))
    )
    (comp (ref "C103")
      (value "8p")
      (footprint "eagle-import:0402-CAP")
      (fields (field (name "PARTNO") "C1005C0G1H080C"))
      (libsource (lib "eagle-import") (part "CAP0402"))
    )
    (comp (ref "R101")
      (value "470R")
      (footprint "eagle-import:0402-RES")
      (fields (field (name "PARTNO") "RC0402FR-07470RL"))
      (libsource (lib "eagle-import") (part "RESISTOR0402-RES"))
    )
    (comp (ref "R102")
      (value "10K")
      (footprint "eagle-import:0402-RES")
      (fields (field (name "PARTNO") "RC0402FR-0710KL"))
      (libsource (lib "eagle-import") (part "RESISTOR0402-RES"))
    )
    (comp (ref "U101")
      (value "STM32F4X7VX")
      (footprint "eagle-import:TQFP100")
      (fields (field (name "PARTNO") "STM32F427VI"))
      (libsource (lib "eagle-import") (part "STM32F4X7VX"))
    )
    (comp (ref "U102")
      (value "FM25V01")
      (footprint "eagle-import:SO08")
      (fields (field (name "PARTNO") "FM25V01-G"))
      (libsource (lib "eagle-import") (part "FM25V01"))
    )
    (comp (ref "X101")
      (value "3.2x2.5 mm / 24 MHz / 15 ppm")
      (footprint "eagle-import:OSCILLATOR-3.2X2.5")
      (fields (field (name "PARTNO") "NX3225SA-24.000000MHZ"))
      (libsource (lib "eagle-import") (part "OSCILLATOR-3.2X2.5"))
    )
    (comp (ref "C1101")
      (value "22u/25V")
      (footprint "eagle-import:0805-CAP")
      (fields (field (name "PARTNO") "CL21A226MAQNNNE"))
      (libsource (lib "eagle-import") (part "CAP0805"))
    )
    (comp (ref "C1102")
      (value "22u/25V")
      (footprint "eagle-import:0805-CAP")
      (fields (field (name "PARTNO") "CL21A226MAQNNNE"))
      (libsource (lib "eagle-import") (part "CAP0805"))
    )
    (comp (ref "C1103")
      (value "22u/25V")
      (footprint "eagle-import:0805-CAP")
      (fields (field (name "PARTNO") "CL21A226MAQNNNE"))
      (libsource (lib "eagle-import") (part "CAP0805"))
    )
    (comp (ref "C1104")
      (value "100u")
      (footprint "eagle-import:1206-CAP")
      (fields (field (name "PARTNO") "C3216X5R1A107M160AC"))
      (libsource (lib "eagle-import") (part "CAP1206"))
    )
    (comp (ref "C1105")
      (value "0u1")
      (footprint "eagle-import:0402-CAP")
      (fields (field (name "PARTNO") "C1005X7R1E104K050BB"))
      (libsource (lib "eagle-import") (part "CAP0402"))
    )
    (comp (ref "C1106")
      (value "0u1")
      (footprint "eagle-import:0402-CAP")
      (fields (field (name "PARTNO") "C1005X7R1E104K050BB"))
      (libsource (lib "eagle-import") (part "CAP0402"))
    )
    (comp (ref "C1107")
      (value "0u1")
      (footprint "eagle-import:0402-CAP")
      (fields (field (name "PARTNO") "C1005X7R1E104K050BB"))
      (libsource (lib "eagle-import") (part "CAP0402"))
    )
    (comp (ref "C1108")
      (value "10p/25V")
      (footprint "eagle-import:0402-CAP")
      (fields (field (name "PARTNO") "C0402C100J3GACTU"))
      (libsource (lib "eagle-import") (part "CAP0402"))
    )
    (comp (ref "C1109")
      (value "10p/25V")
      (footprint "eagle-import:0402-CAP")
      (fields (field (name "PARTNO") "C0402C100J3GACTU"))
      (libsource (lib "eagle-import") (part "CAP0402"))
    )
    (comp (ref "C1110")
      (value "10p/25V")
      (footprint "eagle-import:0402-CAP")
      (fields (field (name "PARTNO") "C0402C100J3GACTU"))
      (libsource (lib "eagle-import") (part "CAP0402"))
    )
    (comp (ref "J601")
      (value "DF13C-6P-1.25V")
      (footprint "eagle-import:DF13C-6P-1.25V")
      (fields (field (name "PARTNO") "DF13C-6P-1.25V(20)"))
      (libsource (lib "eagle-import") (part "DF13-6P-1.25V"))
    )
    (comp (ref "L1101")
      (value "KNH16C104DA5TS")
      (footprint "eagle-import:KYOCERA-KNH16-DA")
      (libsource (lib "eagle-import") (part "KNH16C104DA5TS"))
    )
    (comp (ref "L1102")
      (value "KNH16C104DA5TS")
      (footprint "eagle-import:KYOCERA-KNH16-DA")
      (libsource (lib "eagle-import") (part "KNH16C104DA5TS"))
    )
    (comp (ref "R1101")
      (value "10K/0.1%")
      (footprint "eagle-import:0402-RES")
      (fields (field (name "PARTNO") "ERA-2AEB103X"))
      (libsource (lib "eagle-import") (part "RESISTOR0402-RES"))
    )
    (comp (ref "R1102")
      (value "10K/0.1%")
      (footprint "eagle-import:0402-RES")
      (fields (field (name "PARTNO") "ERA-2AEB103X"))
      (libsource (lib "eagle-import") (part "RESISTOR0402-RES"))
    )
    (comp (ref "R1103")
      (value "1M")
      (footprint "eagle-import:0402-RES")
      (fields (field (name "PARTNO") "RC0402FR-071ML"))
      (libsource (lib "eagle-import") (part "RESISTOR0402-RES"))
    )
    (comp (ref "R1104")
      (value "1M")
      (footprint "eagle-import:0402-RES")
      (fields (field (name "PARTNO") "RC0402FR-071ML"))
      (libsource (lib "eagle-import") (part "RESISTOR0402-RES"))
    )
    (comp (ref "R1105")
      (value "453K")
      (footprint "eagle-import:0402-RES")
      (fields (field (name "PARTNO") "RMCF0402FT453K"))
      (libsource (lib "eagle-import") (part "RESISTOR0402-RES"))
    )
    (comp (ref "R1106")
      (value "56K")
      (footprint "eagle-import:0402-RES")
      (fields (field (name "PARTNO") "ERA-2AEB563X"))
      (libsource (lib "eagle-import") (part "RESISTOR0402-RES"))
    )
    (comp (ref "R1107")
      (value "105K")
      (footprint "eagle-import:0402-RES")
      (fields (field (name "PARTNO") "ERJ-2RKF1053X"))
      (libsource (lib "eagle-import") (part "RESISTOR0402-RES"))
    )
    (comp (ref "R1109")
      (value "453K")
      (footprint "eagle-import:0402-RES")
      (fields (field (name "PARTNO") "RMCF0402FT453K"))
      (libsource (lib "eagle-import") (part "RESISTOR0402-RES"))
    )
    (comp (ref "R1110")
      (value "56K")
      (footprint "eagle-import:0402-RES")
      (fields (field (name "PARTNO") "ERA-2AEB563X"))
      (libsource (lib "eagle-import") (part "RESISTOR0402-RES"))
    )
    (comp (ref "R1111")
      (value "105K")
      (footprint "eagle-import:0402-RES")
      (fields (field (name "PARTNO") "ERJ-2RKF1053X"))
      (libsource (lib "eagle-import") (part "RESISTOR0402-RES"))
    )
    (comp (ref "R1112")
      (value "453K")
      (footprint "eagle-import:0402-RES")
      (fields (field (name "PARTNO") "RMCF0402FT453K"))
      (libsource (lib "eagle-import") (part "RESISTOR0402-RES"))
    )
    (comp (ref "R1113")
      (value "56K")
      (footprint "eagle-import:0402-RES")
      (fields (field (name "PARTNO") "ERA-2AEB563X"))
      (libsource (lib "eagle-import") (part "RESISTOR0402-RES"))
    )
    (comp (ref "R1114")
      (value "105K")
      (footprint "eagle-import:0402-RES")
      (fields (field (name "PARTNO") "ERJ-2RKF1053X"))
      (libsource (lib "eagle-import") (part "RESISTOR0402-RES"))
    )
    (comp (ref "R1115")
      (value "0R")
      (footprint "eagle-import:0402-RES")
      (fields (field (name "PARTNO") "ERJ-2GE0R00X"))
      (libsource (lib "eagle-import") (part "RESISTOR0402-RES"))
    )
    (comp (ref "RN1101")
      (value "1M")
      (footprint "eagle-import:EXB28V")
      (fields (field (name "PARTNO") "EXB-28V105JX"))
      (libsource (lib "eagle-import") (part "4R-NEXB28V"))
    )
    (comp (ref "U1101")
      (value "LTC4417")
      (footprint "eagle-import:MO-220")
      (fields (field (name "PARTNO") "LTC4417IUF#PBF"))
      (libsource (lib "eagle-import") (part "LTC4117"))
    )
    (comp (ref "U1102")
      (value "NTHD4102PT1G")
      (footprint "eagle-import:1206-8")
      (fields (field (name "PARTNO") "NTHD4102PT1G"))
      (libsource (lib "eagle-import") (part "MOSFET-DUAL-PCHANNEL-CHIPFET"))
    )
    (comp (ref "U1103")
      (value "NTHD4102PT1G")
      (footprint "eagle-import:1206-8")
      (fields (field (name "PARTNO") "NTHD4102PT1G"))
      (libsource (lib "eagle-import") (part "MOSFET-DUAL-PCHANNEL-CHIPFET"))
    )
    (comp (ref "U1104")
      (value "NTHD4102PT1G")
      (footprint "eagle-import:1206-8")
      (fields (field (name "PARTNO") "NTHD4102PT1G"))
      (libsource (lib "eagle-import") (part "MOSFET-DUAL-PCHANNEL-CHIPFET"))
    )
    (comp (ref "J301")
      (value "47346-0001")
      (footprint "eagle-import:MOLEX-47346-0001")
      (libsource (lib "eagle-import") (part "MOLEX-47346-0001"))
    )
    (comp (ref "J302")
      (value "DF13C-4P-1.25V")
      (footprint "eagle-import:DF13C-4P-1.25V")
      (fields (field (name "PARTNO") "DF13C-4P-1.25V(20)"))
      (libsource (lib "eagle-import") (part "DF13-4P-1.25V"))
    )
    (comp (ref "JX301")
      (value "ARM_MINI_JTAG-SMT")
      (footprint "eagle-import:FTSH-105-01-XXX-DV-K")
      (fields (field (name "BOM") "EXCLUDE") (field (name "PARTNO") "M50-3900542"))
      (libsource (lib "eagle-import") (part "ARM_MINI_JTAG-SMT"))
    )
    (comp (ref "R301")
      (value "100K")
      (footprint "eagle-import:0402-RES")
      (fields (field (name "PARTNO") "RC0402FR-07100KL"))
      (libsource (lib "eagle-import") (part "RESISTOR0402-RES"))
    )
    (comp (ref "R302")
      (value "100K")
      (footprint "eagle-import:0402-RES")
      (fields (field (name "PARTNO") "RC0402FR-07100KL"))
      (libsource (lib "eagle-import") (part "RESISTOR0402-RES"))
    )
    (comp (ref "R303")
      (value "100K")
      (footprint "eagle-import:0402-RES")
      (fields (field (name "PARTNO") "RC0402FR-07100KL"))
      (libsource (lib "eagle-import") (part "RESISTOR0402-RES"))
    )
    (comp (ref "R304")
      (value "100K")
      (footprint "eagle-import:0402-RES")
      (fields (field (name "PARTNO") "RC0402FR-07100KL"))
      (libsource (lib "eagle-import") (part "RESISTOR0402-RES"))
    )
    (comp (ref "R305")
      (value "100K")
      (footprint "eagle-import:0402-RES")
      (fields (field (name "PARTNO") "RC0402FR-07100KL"))
      (libsource (lib "eagle-import") (part "RESISTOR0402-RES"))
    )
    (comp (ref "R306")
      (value "1K5")
      (footprint "eagle-import:0402-RES")
      (fields (field (name "PARTNO") "RC0402FR-071K5L"))
      (libsource (lib "eagle-import") (part "RESISTOR0402-RES"))
    )
    (comp (ref "R307")
      (value "1K5")
      (footprint "eagle-import:0402-RES")
      (fields (field (name "PARTNO") "RC0402FR-071K5L"))
      (libsource (lib "eagle-import") (part "RESISTOR0402-RES"))
    )
    (comp (ref "U301")
      (value "2908-05WB-MG")
      (footprint "eagle-import:MICROSD")
      (libsource (lib "eagle-import") (part "MICROSDSDI"))
    )
    (comp (ref "U302")
      (value "NUF2042XV6")
      (footprint "eagle-import:SOT563-6")
      (fields (field (name "PARTNO") "NUF2042XV6T1G"))
      (libsource (lib "eagle-import") (part "NUF2042XV6"))
    )
    (comp (ref "C901")
      (value "0u1")
      (footprint "eagle-import:0402-CAP")
      (fields (field (name "PARTNO") "CC0402ZRY5V7BB104"))
      (libsource (lib "eagle-import") (part "CAP0402"))
    )
    (comp (ref "C902")
      (value "0u1")
      (footprint "eagle-import:0402-CAP")
      (fields (field (name "PARTNO") "CC0402ZRY5V7BB104"))
      (libsource (lib "eagle-import") (part "CAP0402"))
    )
    (comp (ref "C903")
      (value "0u1")
      (footprint "eagle-import:0402-CAP")
      (fields (field (name "PARTNO") "CC0402ZRY5V7BB104"))
      (libsource (lib "eagle-import") (part "CAP0402"))
    )
    (comp (ref "D901")
      (value "PESD0402-140")
      (footprint "eagle-import:0402-TVS")
      (libsource (lib "eagle-import") (part "DIODE-TVS"))
    )
    (comp (ref "D902")
      (value "PESD0402-140")
      (footprint "eagle-import:0402-TVS")
      (libsource (lib "eagle-import") (part "DIODE-TVS"))
    )
    (comp (ref "D903")
      (value "PESD0402-140")
      (footprint "eagle-import:0402-TVS")
      (libsource (lib "eagle-import") (part "DIODE-TVS"))
    )
    (comp (ref "D904")
      (value "MSS1P4-M3")
      (footprint "eagle-import:MICROSMP")
      (fields (field (name "PARTNO") "MSS1P4-M3/89A"))
      (libsource (lib "eagle-import") (part "DIODE-SCHOTTKY_MSMP"))
    )
    (comp (ref "J901")
      (value "HEADER-3X163X16RA")
      (footprint "eagle-import:3X16RA")
      (fields (field (name "BOM") "EXCLUDE"))
      (libsource (lib "eagle-import") (part "HEADER-3X163X16RA"))
    )
    (comp (ref "L901")
      (value "KNH16C104DA5TS")
      (footprint "eagle-import:KYOCERA-KNH16-DA")
      (libsource (lib "eagle-import") (part "KNH16C104DA5TS"))
    )
    (comp (ref "R901")
      (value "10K")
      (footprint "eagle-import:0402-RES")
      (fields (field (name "PARTNO") "RC0402FR-0710KL"))
      (libsource (lib "eagle-import") (part "RESISTOR0402-RES"))
    )
    (comp (ref "R902")
      (value "220R")
      (footprint "eagle-import:0402-RES")
      (fields (field (name "PARTNO") "RC0402FR-07220RL"))
      (libsource (lib "eagle-import") (part "RESISTOR0402-RES"))
    )
    (comp (ref "R903")
      (value "220R")
      (footprint "eagle-import:0402-RES")
      (fields (field (name "PARTNO") "RC0402FR-07220RL"))
      (libsource (lib "eagle-import") (part "RESISTOR0402-RES"))
    )
    (comp (ref "R904")
      (value "220R")
      (footprint "eagle-import:0402-RES")
      (fields (field (name "PARTNO") "RC0402FR-07220RL"))
      (libsource (lib "eagle-import") (part "RESISTOR0402-RES"))
    )
    (comp (ref "R905")
      (value "220R")
      (footprint "eagle-import:0402-RES")
      (fields (field (name "PARTNO") "RC0402FR-07220RL"))
      (libsource (lib "eagle-import") (part "RESISTOR0402-RES"))
    )
    (comp (ref "R906")
      (value "220R")
      (footprint "eagle-import:0402-RES")
      (fields (field (name "PARTNO") "RC0402FR-07220RL"))
      (libsource (lib "eagle-import") (part "RESISTOR0402-RES"))
    )
    (comp (ref "R907")
      (value "220R")
      (footprint "eagle-import:0402-RES")
      (fields (field (name "PARTNO") "RC0402FR-07220RL"))
      (libsource (lib "eagle-import") (part "RESISTOR0402-RES"))
    )
    (comp (ref "R908")
      (value "220R")
      (footprint "eagle-import:0402-RES")
      (fields (field (name "PARTNO") "RC0402FR-07220RL"))
      (libsource (lib "eagle-import") (part "RESISTOR0402-RES"))
    )
    (comp (ref "R909")
      (value "220R")
      (footprint "eagle-import:0402-RES")
      (fields (field (name "PARTNO") "RC0402FR-07220RL"))
      (libsource (lib "eagle-import") (part "RESISTOR0402-RES"))
    )
    (comp (ref "R910")
      (value "220R")
      (footprint "eagle-import:0402-RES")
      (fields (field (name "PARTNO") "RC0402FR-07220RL"))
      (libsource (lib "eagle-import") (part "RESISTOR0402-RES"))
    )
    (comp (ref "R911")
      (value "220R")
      (footprint "eagle-import:0402-RES")
      (fields (field (name "PARTNO") "RC0402FR-07220RL"))
      (libsource (lib "eagle-import") (part "RESISTOR0402-RES"))
    )
    (comp (ref "R912")
      (value "220R")
      (footprint "eagle-import:0402-RES")
      (fields (field (name "PARTNO") "RC0402FR-07220RL"))
      (libsource (lib "eagle-import") (part "RESISTOR0402-RES"))
    )
    (comp (ref "R913")
      (value "220R")
      (footprint "eagle-import:0402-RES")
      (fields (field (name "PARTNO") "RC0402FR-07220RL"))
      (libsource (lib "eagle-import") (part "RESISTOR0402-RES"))
    )
    (comp (ref "R914")
      (value "220R")
      (footprint "eagle-import:0402-RES")
      (fields (field (name "PARTNO") "RC0402FR-07220RL"))
      (libsource (lib "eagle-import") (part "RESISTOR0402-RES"))
    )
    (comp (ref "R915")
      (value "220R")
      (footprint "eagle-import:0402-RES")
      (fields (field (name "PARTNO") "RC0402FR-07220RL"))
      (libsource (lib "eagle-import") (part "RESISTOR0402-RES"))
    )
    (comp (ref "R916")
      (value "220R")
      (footprint "eagle-import:0402-RES")
      (fields (field (name "PARTNO") "RC0402FR-07220RL"))
      (libsource (lib "eagle-import") (part "RESISTOR0402-RES"))
    )
    (comp (ref "R917")
      (value "220R")
      (footprint "eagle-import:0402-RES")
      (fields (field (name "PARTNO") "RC0402FR-07220RL"))
      (libsource (lib "eagle-import") (part "RESISTOR0402-RES"))
    )
    (comp (ref "R918")
      (value "10K/0.1%")
      (footprint "eagle-import:0402-RES")
      (fields (field (name "PARTNO") "ERA-2AEB103X"))
      (libsource (lib "eagle-import") (part "RESISTOR0402-RES"))
    )
    (comp (ref "R919")
      (value "10K/0.1%")
      (footprint "eagle-import:0402-RES")
      (fields (field (name "PARTNO") "ERA-2AEB103X"))
      (libsource (lib "eagle-import") (part "RESISTOR0402-RES"))
    )
    (comp (ref "R922")
      (value "10K/0.1%")
      (footprint "eagle-import:0402-RES")
      (fields (field (name "PARTNO") "ERA-2AEB103X"))
      (libsource (lib "eagle-import") (part "RESISTOR0402-RES"))
    )
    (comp (ref "U901")
      (value "TXS0108QFN20")
      (footprint "eagle-import:QFN20-RGY")
      (fields (field (name "PARTNO") "TXS0108ERGYR"))
      (libsource (lib "eagle-import") (part "TXS0108QFN20"))
    )
    (comp (ref "U902")
      (value "TXS0108QFN20")
      (footprint "eagle-import:QFN20-RGY")
      (fields (field (name "PARTNO") "TXS0108ERGYR"))
      (libsource (lib "eagle-import") (part "TXS0108QFN20"))
    )
    (comp (ref "U903")
      (value "74LVC2G240")
      (footprint "eagle-import:TSSOP8_SOT505-2")
      (fields (field (name "PARTNO") "74LVC2G240DP,125"))
      (libsource (lib "eagle-import") (part "74LVC2G240-TSSOP-8"))
    )
    (comp (ref "B601")
      (value "MS621FE")
      (footprint "eagle-import:MS621FE")
      (fields (field (name "PARTNO") "MS621FE-FL11E"))
      (libsource (lib "eagle-import") (part "MS621FE"))
    )
    (comp (ref "C601")
      (value "10u/25V")
      (footprint "eagle-import:0805-CAP")
      (fields (field (name "PARTNO") "CL21A106KAYNNNE"))
      (libsource (lib "eagle-import") (part "CAP0805"))
    )
    (comp (ref "C602")
      (value "10n")
      (footprint "eagle-import:0402-CAP")
      (fields (field (name "PARTNO") "CC0402KRX7R7BB103"))
      (libsource (lib "eagle-import") (part "CAP0402"))
    )
    (comp (ref "C603")
      (value "1u")
      (footprint "eagle-import:0603-CAP")
      (fields (field (name "PARTNO") "CC0603ZRY5V7BB105"))
      (libsource (lib "eagle-import") (part "CAP0603"))
    )
    (comp (ref "C604")
      (value "22u/25V")
      (footprint "eagle-import:0805-CAP")
      (fields (field (name "PARTNO") "CL21A226MAQNNNE"))
      (libsource (lib "eagle-import") (part "CAP0805"))
    )
    (comp (ref "C605")
      (value "22u/25V")
      (footprint "eagle-import:0805-CAP")
      (fields (field (name "PARTNO") "CL21A226MAQNNNE"))
      (libsource (lib "eagle-import") (part "CAP0805"))
    )
    (comp (ref "C606")
      (value "0u1")
      (footprint "eagle-import:0402-CAP")
      (fields (field (name "PARTNO") "CC0402ZRY5V7BB104"))
      (libsource (lib "eagle-import") (part "CAP0402"))
    )
    (comp (ref "C607")
      (value "0u1")
      (footprint "eagle-import:0402-CAP")
      (fields (field (name "PARTNO") "CC0402ZRY5V7BB104"))
      (libsource (lib "eagle-import") (part "CAP0402"))
    )
    (comp (ref "C608")
      (value "0u1")
      (footprint "eagle-import:0402-CAP")
      (fields (field (name "PARTNO") "CC0402ZRY5V7BB104"))
      (libsource (lib "eagle-import") (part "CAP0402"))
    )
    (comp (ref "C609")
      (value "0u1")
      (footprint "eagle-import:0402-CAP")
      (fields (field (name "PARTNO") "CC0402ZRY5V7BB104"))
      (libsource (lib "eagle-import") (part "CAP0402"))
    )
    (comp (ref "C610")
      (value "0u1")
      (footprint "eagle-import:0402-CAP")
      (fields (field (name "PARTNO") "CC0402ZRY5V7BB104"))
      (libsource (lib "eagle-import") (part "CAP0402"))
    )
    (comp (ref "C611")
      (value "2u2")
      (footprint "eagle-import:0603-CAP")
      (fields (field (name "PARTNO") "C1608X6S1C225K080AC"))
      (libsource (lib "eagle-import") (part "CAP0603"))
    )
    (comp (ref "C612")
      (value "0u1")
      (footprint "eagle-import:0402-CAP")
      (fields (field (name "PARTNO") "CC0402ZRY5V7BB104"))
      (libsource (lib "eagle-import") (part "CAP0402"))
    )
    (comp (ref "C613")
      (value "2u2")
      (footprint "eagle-import:0603-CAP")
      (fields (field (name "PARTNO") "C1608X6S1C225K080AC"))
      (libsource (lib "eagle-import") (part "CAP0603"))
    )
    (comp (ref "C614")
      (value "100u")
      (footprint "eagle-import:1206-CAP")
      (fields (field (name "PARTNO") "C3216X5R1A107M160AC"))
      (libsource (lib "eagle-import") (part "CAP1206"))
    )
    (comp (ref "C615")
      (value "0u1")
      (footprint "eagle-import:0402-CAP")
      (fields (field (name "PARTNO") "CC0402ZRY5V7BB104"))
      (libsource (lib "eagle-import") (part "CAP0402"))
    )
    (comp (ref "C616")
      (value "0u1")
      (footprint "eagle-import:0402-CAP")
      (fields (field (name "PARTNO") "CC0402ZRY5V7BB104"))
      (libsource (lib "eagle-import") (part "CAP0402"))
    )
    (comp (ref "C617")
      (value "0u1")
      (footprint "eagle-import:0402-CAP")
      (fields (field (name "PARTNO") "CC0402ZRY5V7BB104"))
      (libsource (lib "eagle-import") (part "CAP0402"))
    )
    (comp (ref "C618")
      (value "100u")
      (footprint "eagle-import:1206-CAP")
      (fields (field (name "PARTNO") "C3216X5R1A107M160AC"))
      (libsource (lib "eagle-import") (part "CAP1206"))
    )
    (comp (ref "D602")
      (value "RB751V40T1G")
      (footprint "eagle-import:SOD323")
      (libsource (lib "eagle-import") (part "DIODE-SCHOTTKY_SOD323"))
    )
    (comp (ref "L603")
      (value "KNH16C104DA5TS")
      (footprint "eagle-import:KYOCERA-KNH16-DA")
      (libsource (lib "eagle-import") (part "KNH16C104DA5TS"))
    )
    (comp (ref "Q601")
      (value "MMBT3906LT1SMD")
      (footprint "eagle-import:SOT23-BEC")
      (fields (field (name "PARTNO") "MMBT 3906 LT1"))
      (libsource (lib "eagle-import") (part "MMBT3906SMDLT1"))
    )
    (comp (ref "R602")
      (value "1M")
      (footprint "eagle-import:0402-RES")
      (fields (field (name "PARTNO") "RC0402FR-071ML"))
      (libsource (lib "eagle-import") (part "RESISTOR0402-RES"))
    )
    (comp (ref "R603")
      (value "10K")
      (footprint "eagle-import:0402-RES")
      (fields (field (name "PARTNO") "RC0402FR-0710KL"))
      (libsource (lib "eagle-import") (part "RESISTOR0402-RES"))
    )
    (comp (ref "R604")
      (value "1M")
      (footprint "eagle-import:0402-RES")
      (fields (field (name "PARTNO") "RC0402FR-071ML"))
      (libsource (lib "eagle-import") (part "RESISTOR0402-RES"))
    )
    (comp (ref "R608")
      (value "1K")
      (footprint "eagle-import:0402-RES")
      (fields (field (name "PARTNO") "RC0402FR-071KL"))
      (libsource (lib "eagle-import") (part "RESISTOR0402-RES"))
    )
    (comp (ref "R609")
      (value "10K/0.1%")
      (footprint "eagle-import:0402-RES")
      (fields (field (name "PARTNO") "ERA-2AEB103X"))
      (libsource (lib "eagle-import") (part "RESISTOR0402-RES"))
    )
    (comp (ref "R610")
      (value "10K/0.1%")
      (footprint "eagle-import:0402-RES")
      (fields (field (name "PARTNO") "ERA-2AEB103X"))
      (libsource (lib "eagle-import") (part "RESISTOR0402-RES"))
    )
    (comp (ref "R611")
      (value "10K")
      (footprint "eagle-import:0402-RES")
      (fields (field (name "PARTNO") "RC0402FR-0710KL"))
      (libsource (lib "eagle-import") (part "RESISTOR0402-RES"))
    )
    (comp (ref "R615")
      (value "10K")
      (footprint "eagle-import:0402-RES")
      (fields (field (name "PARTNO") "RC0402FR-0710KL"))
      (libsource (lib "eagle-import") (part "RESISTOR0402-RES"))
    )
    (comp (ref "R616")
      (value "25K5")
      (footprint "eagle-import:0402-RES")
      (fields (field (name "PARTNO") "RMCF0402FT25K5"))
      (libsource (lib "eagle-import") (part "RESISTOR0402-RES"))
    )
    (comp (ref "R617")
      (value "16K5")
      (footprint "eagle-import:0402-RES")
      (fields (field (name "PARTNO") "RMCF0402FT16K5"))
      (libsource (lib "eagle-import") (part "RESISTOR0402-RES"))
    )
    (comp (ref "R620")
      (value "1K8")
      (footprint "eagle-import:0402-RES")
      (fields (field (name "PARTNO") "RC1005F182CS"))
      (libsource (lib "eagle-import") (part "RESISTOR0402-RES"))
    )
    (comp (ref "R621")
      (value "10R")
      (footprint "eagle-import:0603-RES")
      (fields (field (name "PARTNO") "RC1608J100CS"))
      (libsource (lib "eagle-import") (part "RESISTOR0603-RES"))
    )
    (comp (ref "R635")
      (value "10K")
      (footprint "eagle-import:0402-RES")
      (fields (field (name "PARTNO") "RC0402FR-0710KL"))
      (libsource (lib "eagle-import") (part "RESISTOR0402-RES"))
    )
    (comp (ref "S601")
      (value "RESET")
      (footprint "eagle-import:EVQP7J01K")
      (fields (field (name "PARTNO") "EVQ-P7J01P"))
      (libsource (lib "eagle-import") (part "SWITCH-MOMENTARY-2"))
    )
    (comp (ref "U601")
      (value "BQ24315")
      (footprint "eagle-import:QFN8-DSG")
      (fields (field (name "PARTNO") "BQ24315DSGR"))
      (libsource (lib "eagle-import") (part "BQ24315"))
    )
    (comp (ref "U602")
      (value "BQ24315")
      (footprint "eagle-import:QFN8-DSG")
      (fields (field (name "PARTNO") "BQ24315DSGR"))
      (libsource (lib "eagle-import") (part "BQ24315"))
    )
    (comp (ref "U603")
      (value "MIC5332")
      (footprint "eagle-import:MLF-8-EPAD")
      (fields (field (name "PARTNO") "MIC5332-SSYMT"))
      (libsource (lib "eagle-import") (part "MIC5332"))
    )
    (comp (ref "C501")
      (value "10u/10V")
      (footprint "eagle-import:0805-CAP")
      (fields (field (name "PARTNO") "CC0805ZKY5V6BB106"))
      (libsource (lib "eagle-import") (part "CAP0805"))
    )
    (comp (ref "C502")
      (value "0u1")
      (footprint "eagle-import:0402-CAP")
      (fields (field (name "PARTNO") "CC0402ZRY5V7BB104"))
      (libsource (lib "eagle-import") (part "CAP0402"))
    )
    (comp (ref "C503")
      (value "0u1")
      (footprint "eagle-import:0402-CAP")
      (fields (field (name "PARTNO") "CC0402ZRY5V7BB104"))
      (libsource (lib "eagle-import") (part "CAP0402"))
    )
    (comp (ref "C504")
      (value "10n")
      (footprint "eagle-import:0402-CAP")
      (fields (field (name "PARTNO") "CC0402KRX7R7BB103"))
      (libsource (lib "eagle-import") (part "CAP0402"))
    )
    (comp (ref "C505")
      (value "10n")
      (footprint "eagle-import:0402-CAP")
      (fields (field (name "PARTNO") "CC0402KRX7R7BB103"))
      (libsource (lib "eagle-import") (part "CAP0402"))
    )
    (comp (ref "C506")
      (value "10u/10V")
      (footprint "eagle-import:0805-CAP")
      (fields (field (name "PARTNO") "CC0805ZKY5V6BB106"))
      (libsource (lib "eagle-import") (part "CAP0805"))
    )
    (comp (ref "C507")
      (value "0u1")
      (footprint "eagle-import:0402-CAP")
      (fields (field (name "PARTNO") "CC0402ZRY5V7BB104"))
      (libsource (lib "eagle-import") (part "CAP0402"))
    )
    (comp (ref "C508")
      (value "0u1")
      (footprint "eagle-import:0402-CAP")
      (fields (field (name "PARTNO") "CC0402ZRY5V7BB104"))
      (libsource (lib "eagle-import") (part "CAP0402"))
    )
    (comp (ref "C509")
      (value "10u/10V")
      (footprint "eagle-import:0805-CAP")
      (fields (field (name "PARTNO") "CC0805ZKY5V6BB106"))
      (libsource (lib "eagle-import") (part "CAP0805"))
    )
    (comp (ref "C510")
      (value "0u47")
      (footprint "eagle-import:0402-CAP")
      (fields (field (name "PARTNO") "C1005X5R1C474K050BC"))
      (libsource (lib "eagle-import") (part "CAP0402"))
    )
    (comp (ref "C511")
      (value "10u/10V")
      (footprint "eagle-import:0805-CAP")
      (fields (field (name "PARTNO") "CC0805ZKY5V6BB106"))
      (libsource (lib "eagle-import") (part "CAP0805"))
    )
    (comp (ref "C512")
      (value "2u2")
      (footprint "eagle-import:0603-CAP")
      (fields (field (name "PARTNO") "C1608X6S1C225K080AC"))
      (libsource (lib "eagle-import") (part "CAP0603"))
    )
    (comp (ref "C513")
      (value "2u2")
      (footprint "eagle-import:0603-CAP")
      (fields (field (name "PARTNO") "C1608X6S1C225K080AC"))
      (libsource (lib "eagle-import") (part "CAP0603"))
    )
    (comp (ref "C514")
      (value "0u1")
      (footprint "eagle-import:0402-CAP")
      (fields (field (name "PARTNO") "CC0402ZRY5V7BB104"))
      (libsource (lib "eagle-import") (part "CAP0402"))
    )
    (comp (ref "C515")
      (value "0u01")
      (footprint "eagle-import:0603-CAP")
      (fields (field (name "PARTNO") "06033C103JAT2A"))
      (libsource (lib "eagle-import") (part "CAP0603"))
    )
    (comp (ref "U501")
      (value "L3GD20")
      (footprint "eagle-import:L3G4200DH-MAN")
      (libsource (lib "eagle-import") (part "L3G4200DH-LL"))
    )
    (comp (ref "U502")
      (value "L3GD20H")
      (footprint "eagle-import:LGA-16L")
      (libsource (lib "eagle-import") (part "L3GD20H"))
    )
    (comp (ref "U504")
      (value "LSM303D")
      (footprint "eagle-import:LGA-16L")
      (libsource (lib "eagle-import") (part "LSM303D"))
    )
    (comp (ref "U505")
      (value "MPU-6000")
      (footprint "eagle-import:QFN-24")
      (libsource (lib "eagle-import") (part "MPU-6000"))
    )
    (comp (ref "U506")
      (value "MS5611-01BA")
      (footprint "eagle-import:MS5611-01BA")
      (libsource (lib "eagle-import") (part "MS5611-01BA"))
    )
    (comp (ref "X503")
      (value "0512811094")
      (footprint "eagle-import:51281-1094")
      (fields (field (name "PARTNO") "0781191109") (field (name "BOM") "EXCLUDE"))
      (libsource (lib "eagle-import") (part "CONN_FPC_10RA"))
    )
    (comp (ref "C701")
      (value "0u1")
      (footprint "eagle-import:0402-CAP")
      (fields (field (name "PARTNO") "CC0402ZRY5V7BB104"))
      (libsource (lib "eagle-import") (part "CAP0402"))
    )
    (comp (ref "C702")
      (value "1u")
      (footprint "eagle-import:0603-CAP")
      (fields (field (name "PARTNO") "CC0603ZRY5V7BB105"))
      (libsource (lib "eagle-import") (part "CAP0603"))
    )
    (comp (ref "C703")
      (value "5n6")
      (footprint "eagle-import:0402-CAP")
      (fields (field (name "PARTNO") "C0402C562K5RACTU"))
      (libsource (lib "eagle-import") (part "CAP0402"))
    )
    (comp (ref "C704")
      (value "0u47")
      (footprint "eagle-import:0402-CAP")
      (fields (field (name "PARTNO") "C1005X5R1C474K050BC"))
      (libsource (lib "eagle-import") (part "CAP0402"))
    )
    (comp (ref "D701")
      (value "PESD0402-140")
      (footprint "eagle-import:0402-TVS")
      (libsource (lib "eagle-import") (part "DIODE-TVS"))
    )
    (comp (ref "J701")
      (value "DF13C-2P-1.25V")
      (footprint "eagle-import:DF13C-2P-1.25V")
      (fields (field (name "PARTNO") "DF13C-2P-1.25V(20)"))
      (libsource (lib "eagle-import") (part "DF13-2P-1.25V"))
    )
    (comp (ref "J702")
      (value "DF13C-3P-1.25V")
      (footprint "eagle-import:DF13C-3P-1.25V")
      (fields (field (name "PARTNO") "DF13C-3P-1.25V(20)"))
      (libsource (lib "eagle-import") (part "DF13-3P-1.25V"))
    )
    (comp (ref "L701")
      (value "47uH")
      (footprint "eagle-import:0805-IND")
      (fields (field (name "PARTNO") "MLZ2012M470W"))
      (libsource (lib "eagle-import") (part "INDUCTOR0805"))
    )
    (comp (ref "LED701")
      (value "AMBER")
      (footprint "eagle-import:0603-LED")
      (fields (field (name "PARTNO") "APTD1608SECK"))
      (libsource (lib "eagle-import") (part "LED0603"))
    )
    (comp (ref "LED702")
      (value "GREEN")
      (footprint "eagle-import:0603-LED")
      (fields (field (name "PARTNO") "APTD1608CGCK"))
      (libsource (lib "eagle-import") (part "LED0603"))
    )
    (comp (ref "LED703")
      (value "AMBER")
      (footprint "eagle-import:0603-LED")
      (fields (field (name "PARTNO") "APTD1608SECK"))
      (libsource (lib "eagle-import") (part "LED0603"))
    )
    (comp (ref "LED704")
      (value "GREEN")
      (footprint "eagle-import:0603-LED")
      (fields (field (name "PARTNO") "APTD1608CGCK"))
      (libsource (lib "eagle-import") (part "LED0603"))
    )
    (comp (ref "LED705")
      (value "BLUE")
      (footprint "eagle-import:0603-LED")
      (fields (field (name "PARTNO") "APTD1608QBC/D"))
      (libsource (lib "eagle-import") (part "LED0603"))
    )
    (comp (ref "R701")
      (value "9K09")
      (footprint "eagle-import:0402-RES")
      (fields (field (name "PARTNO") "RMCF0402FT9K09"))
      (libsource (lib "eagle-import") (part "RESISTOR0402-RES"))
    )
    (comp (ref "R702")
      (value "10K")
      (footprint "eagle-import:0402-RES")
      (fields (field (name "PARTNO") "RC0402FR-0710KL"))
      (libsource (lib "eagle-import") (part "RESISTOR0402-RES"))
    )
    (comp (ref "R703")
      (value "100K")
      (footprint "eagle-import:0402-RES")
      (fields (field (name "PARTNO") "RC0402FR-07100KL"))
      (libsource (lib "eagle-import") (part "RESISTOR0402-RES"))
    )
    (comp (ref "R704")
      (value "10K")
      (footprint "eagle-import:0402-RES")
      (fields (field (name "PARTNO") "RC0402FR-0710KL"))
      (libsource (lib "eagle-import") (part "RESISTOR0402-RES"))
    )
    (comp (ref "R705")
      (value "453K")
      (footprint "eagle-import:0402-RES")
      (fields (field (name "PARTNO") "RMCF0402FT453K"))
      (libsource (lib "eagle-import") (part "RESISTOR0402-RES"))
    )
    (comp (ref "R706")
      (value "16K5")
      (footprint "eagle-import:0402-RES")
      (fields (field (name "PARTNO") "RMCF0402FT16K5"))
      (libsource (lib "eagle-import") (part "RESISTOR0402-RES"))
    )
    (comp (ref "R707")
      (value "220R")
      (footprint "eagle-import:0402-RES")
      (fields (field (name "PARTNO") "RC0402FR-07220RL"))
      (libsource (lib "eagle-import") (part "RESISTOR0402-RES"))
    )
    (comp (ref "R708")
      (value "220R")
      (footprint "eagle-import:0402-RES")
      (fields (field (name "PARTNO") "RC0402FR-07220RL"))
      (libsource (lib "eagle-import") (part "RESISTOR0402-RES"))
    )
    (comp (ref "R709")
      (value "220R")
      (footprint "eagle-import:0402-RES")
      (fields (field (name "PARTNO") "RC0402FR-07220RL"))
      (libsource (lib "eagle-import") (part "RESISTOR0402-RES"))
    )
    (comp (ref "R710")
      (value "68R")
      (footprint "eagle-import:0402-RES")
      (fields (field (name "PARTNO") "ERJ-2GEJ680X"))
      (libsource (lib "eagle-import") (part "RESISTOR0402-RES"))
    )
    (comp (ref "R711")
      (value "220R")
      (footprint "eagle-import:0402-RES")
      (fields (field (name "PARTNO") "RC0402FR-07220RL"))
      (libsource (lib "eagle-import") (part "RESISTOR0402-RES"))
    )
    (comp (ref "R712")
      (value "220R")
      (footprint "eagle-import:0402-RES")
      (fields (field (name "PARTNO") "RC0402FR-07220RL"))
      (libsource (lib "eagle-import") (part "RESISTOR0402-RES"))
    )
    (comp (ref "R713")
      (value "1K5")
      (footprint "eagle-import:0402-RES")
      (fields (field (name "PARTNO") "RC0402FR-071K5L"))
      (libsource (lib "eagle-import") (part "RESISTOR0402-RES"))
    )
    (comp (ref "R735")
      (value "220R")
      (footprint "eagle-import:0402-RES")
      (fields (field (name "PARTNO") "RC0402FR-07220RL"))
      (libsource (lib "eagle-import") (part "RESISTOR0402-RES"))
    )
    (comp (ref "R736")
      (value "220R")
      (footprint "eagle-import:0402-RES")
      (fields (field (name "PARTNO") "RC0402FR-07220RL"))
      (libsource (lib "eagle-import") (part "RESISTOR0402-RES"))
    )
    (comp (ref "U701")
      (value "TCA62724FMG")
      (footprint "eagle-import:SON10")
      (libsource (lib "eagle-import") (part "TCA62724FMG"))
    )
    (comp (ref "U702")
      (value "LT3469")
      (footprint "eagle-import:SOT23-8")
      (fields (field (name "PARTNO") "LT3469ETS8"))
      (libsource (lib "eagle-import") (part "LT3469"))
    )
    (comp (ref "U703")
      (value "LRTB GFTG-T7AW-1+V7A7-29+R5T9-49-L")
      (footprint "eagle-import:6-PLCC")
      (fields (field (name "PARTNO") "LRTB GFTG-T7AW-1+V7A7-29+R5T9-49-L"))
      (libsource (lib "eagle-import") (part "RGB-LED6-PLCC"))
    )
    (comp (ref "C401")
      (value "0u1")
      (footprint "eagle-import:0402-CAP")
      (fields (field (name "PARTNO") "CC0402ZRY5V7BB104"))
      (libsource (lib "eagle-import") (part "CAP0402"))
    )
    (comp (ref "C402")
      (value "0u1")
      (footprint "eagle-import:0402-CAP")
      (fields (field (name "PARTNO") "CC0402ZRY5V7BB104"))
      (libsource (lib "eagle-import") (part "CAP0402"))
    )
    (comp (ref "D401")
      (value "PESD0402-140")
      (footprint "eagle-import:0402-TVS")
      (libsource (lib "eagle-import") (part "DIODE-TVS"))
    )
    (comp (ref "D402")
      (value "PESD0402-140")
      (footprint "eagle-import:0402-TVS")
      (libsource (lib "eagle-import") (part "DIODE-TVS"))
    )
    (comp (ref "D403")
      (value "PESD0402-140")
      (footprint "eagle-import:0402-TVS")
      (libsource (lib "eagle-import") (part "DIODE-TVS"))
    )
    (comp (ref "D404")
      (value "PESD0402-140")
      (footprint "eagle-import:0402-TVS")
      (libsource (lib "eagle-import") (part "DIODE-TVS"))
    )
    (comp (ref "J401")
      (value "DF13C-4P-1.25V")
      (footprint "eagle-import:DF13C-4P-1.25V")
      (fields (field (name "PARTNO") "DF13C-4P-1.25V(20)"))
      (libsource (lib "eagle-import") (part "DF13-4P-1.25V"))
    )
    (comp (ref "J402")
      (value "DF13C-3P-1.25V")
      (footprint "eagle-import:DF13C-3P-1.25V")
      (fields (field (name "PARTNO") "DF13C-3P-1.25V(20)"))
      (libsource (lib "eagle-import") (part "DF13-3P-1.25V"))
    )
    (comp (ref "J403")
      (value "DF13C-7P-1.25V")
      (footprint "eagle-import:DF13C-7P-1.25V")
      (fields (field (name "PARTNO") "DF13C-7P-1.25V(20)"))
      (libsource (lib "eagle-import") (part "DF13-7P-1.25V"))
    )
    (comp (ref "J404")
      (value "DF13C-5P-1.25V")
      (footprint "eagle-import:DF13C-5P-1.25V")
      (fields (field (name "PARTNO") "DF13C-5P-1.25V(20)"))
      (libsource (lib "eagle-import") (part "DF13-5P-1.25V"))
    )
    (comp (ref "J405")
      (value "DF13C-4P-1.25V")
      (footprint "eagle-import:DF13C-4P-1.25V")
      (fields (field (name "PARTNO") "DF13C-4P-1.25V(20)"))
      (libsource (lib "eagle-import") (part "DF13-4P-1.25V"))
    )
    (comp (ref "L401")
      (value "KNH16C104DA5TS")
      (footprint "eagle-import:KYOCERA-KNH16-DA")
      (libsource (lib "eagle-import") (part "KNH16C104DA5TS"))
    )
    (comp (ref "L402")
      (value "KNH16C104DA5TS")
      (footprint "eagle-import:KYOCERA-KNH16-DA")
      (libsource (lib "eagle-import") (part "KNH16C104DA5TS"))
    )
    (comp (ref "L403")
      (value "KNH16C104DA5TS")
      (footprint "eagle-import:KYOCERA-KNH16-DA")
      (libsource (lib "eagle-import") (part "KNH16C104DA5TS"))
    )
    (comp (ref "L404")
      (value "KNH16C104DA5TS")
      (footprint "eagle-import:KYOCERA-KNH16-DA")
      (libsource (lib "eagle-import") (part "KNH16C104DA5TS"))
    )
    (comp (ref "R401")
      (value "1K5")
      (footprint "eagle-import:0402-RES")
      (fields (field (name "PARTNO") "RC0402FR-071K5L"))
      (libsource (lib "eagle-import") (part "RESISTOR0402-RES"))
    )
    (comp (ref "R402")
      (value "1K5")
      (footprint "eagle-import:0402-RES")
      (fields (field (name "PARTNO") "RC0402FR-071K5L"))
      (libsource (lib "eagle-import") (part "RESISTOR0402-RES"))
    )
    (comp (ref "R403")
      (value "10K/0.1%")
      (footprint "eagle-import:0402-RES")
      (fields (field (name "PARTNO") "ERA-2AEB103X"))
      (libsource (lib "eagle-import") (part "RESISTOR0402-RES"))
    )
    (comp (ref "R404")
      (value "120R")
      (footprint "eagle-import:0402-RES")
      (fields (field (name "PARTNO") "RC0402FR-07120RL"))
      (libsource (lib "eagle-import") (part "RESISTOR0402-RES"))
    )
    (comp (ref "R405")
      (value "120R")
      (footprint "eagle-import:0402-RES")
      (fields (field (name "PARTNO") "RC0402FR-07120RL"))
      (libsource (lib "eagle-import") (part "RESISTOR0402-RES"))
    )
    (comp (ref "R406")
      (value "10K/0.1%")
      (footprint "eagle-import:0402-RES")
      (fields (field (name "PARTNO") "ERA-2AEB103X"))
      (libsource (lib "eagle-import") (part "RESISTOR0402-RES"))
    )
    (comp (ref "R407")
      (value "10K/0.1%")
      (footprint "eagle-import:0402-RES")
      (fields (field (name "PARTNO") "ERA-2AEB103X"))
      (libsource (lib "eagle-import") (part "RESISTOR0402-RES"))
    )
    (comp (ref "R408")
      (value "10K/0.1%")
      (footprint "eagle-import:0402-RES")
      (fields (field (name "PARTNO") "ERA-2AEB103X"))
      (libsource (lib "eagle-import") (part "RESISTOR0402-RES"))
    )
    (comp (ref "R409")
      (value "120R")
      (footprint "eagle-import:0402-RES")
      (fields (field (name "PARTNO") "RC0402FR-07120RL"))
      (libsource (lib "eagle-import") (part "RESISTOR0402-RES"))
    )
    (comp (ref "U401")
      (value "MAX3051")
      (footprint "eagle-import:SOT23-8")
      (fields (field (name "PARTNO") "MAX3051EKA"))
      (libsource (lib "eagle-import") (part "MAX3051MAX3051EKA"))
    )
    (comp (ref "C801")
      (value "0u1")
      (footprint "eagle-import:0402-CAP")
      (fields (field (name "PARTNO") "CC0402ZRY5V7BB104"))
      (libsource (lib "eagle-import") (part "CAP0402"))
    )
    (comp (ref "C802")
      (value "0u1")
      (footprint "eagle-import:0402-CAP")
      (fields (field (name "PARTNO") "CC0402ZRY5V7BB104"))
      (libsource (lib "eagle-import") (part "CAP0402"))
    )
    (comp (ref "C803")
      (value "0u1")
      (footprint "eagle-import:0402-CAP")
      (fields (field (name "PARTNO") "CC0402ZRY5V7BB104"))
      (libsource (lib "eagle-import") (part "CAP0402"))
    )
    (comp (ref "C804")
      (value "0u1")
      (footprint "eagle-import:0402-CAP")
      (fields (field (name "PARTNO") "CC0402ZRY5V7BB104"))
      (libsource (lib "eagle-import") (part "CAP0402"))
    )
    (comp (ref "C805")
      (value "8p")
      (footprint "eagle-import:0402-CAP")
      (fields (field (name "PARTNO") "C1005C0G1H080C"))
      (libsource (lib "eagle-import") (part "CAP0402"))
    )
    (comp (ref "C806")
      (value "8p")
      (footprint "eagle-import:0402-CAP")
      (fields (field (name "PARTNO") "C1005C0G1H080C"))
      (libsource (lib "eagle-import") (part "CAP0402"))
    )
    (comp (ref "D801")
      (value "PESD0402-140")
      (footprint "eagle-import:0402-TVS")
      (libsource (lib "eagle-import") (part "DIODE-TVS"))
    )
    (comp (ref "J801")
      (value "JST-ZH-3")
      (footprint "eagle-import:JST-ZH-SMT-VERTICAL")
      (fields (field (name "PARTNO") "B3B-ZR-SM4-TF (LF)(SN)(P)"))
      (libsource (lib "eagle-import") (part "JST-ZH-3"))
    )
    (comp (ref "JX801")
      (value "HEADER-3X1BOARDEDGE-SHORT")
      (footprint "eagle-import:HEADER_3X01_SMD_H_BOARD_EDGE_SHORT")
      (libsource (lib "eagle-import") (part "HEADER-3X1BOARDEDGE-SHORT"))
    )
    (comp (ref "JX802")
      (value "ARM_MINI_JTAG-SMT")
      (footprint "eagle-import:FTSH-105-01-XXX-DV-K")
      (fields (field (name "BOM") "EXCLUDE") (field (name "PARTNO") "M50-3900542"))
      (libsource (lib "eagle-import") (part "ARM_MINI_JTAG-SMT"))
    )
    (comp (ref "R801")
      (value "10K")
      (footprint "eagle-import:0402-RES")
      (fields (field (name "PARTNO") "RC0402FR-0710KL"))
      (libsource (lib "eagle-import") (part "RESISTOR0402-RES"))
    )
    (comp (ref "R802")
      (value "10K")
      (footprint "eagle-import:0402-RES")
      (fields (field (name "PARTNO") "RC0402FR-0710KL"))
      (libsource (lib "eagle-import") (part "RESISTOR0402-RES"))
    )
    (comp (ref "R803")
      (value "220R")
      (footprint "eagle-import:0402-RES")
      (fields (field (name "PARTNO") "RC0402FR-07220RL"))
      (libsource (lib "eagle-import") (part "RESISTOR0402-RES"))
    )
    (comp (ref "R804")
      (value "220R")
      (footprint "eagle-import:0402-RES")
      (fields (field (name "PARTNO") "RC0402FR-07220RL"))
      (libsource (lib "eagle-import") (part "RESISTOR0402-RES"))
    )
    (comp (ref "S801")
      (value "RESET")
      (footprint "eagle-import:EVQP7J01K")
      (fields (field (name "PARTNO") "EVQ-P7J01P"))
      (libsource (lib "eagle-import") (part "SWITCH-MOMENTARY-2"))
    )
    (comp (ref "U801")
      (value "STM32F10XCXT6")
      (footprint "eagle-import:TQFP48")
      (fields (field (name "PARTNO") "STM32F100C8T6B"))
      (libsource (lib "eagle-import") (part "STM32F10XCXT6"))
    )
    (comp (ref "X801")
      (value "3.2x2.5 mm / 24 MHz / 15 ppm")
      (footprint "eagle-import:OSCILLATOR-3.2X2.5")
      (fields (field (name "PARTNO") "NX3225SA-24.000000MHZ"))
      (libsource (lib "eagle-import") (part "OSCILLATOR-3.2X2.5"))
    )
  )
  (nets
    (net (code "1") (name "ACCEL_DRDY") (class "Default")
      (node (ref "U101") (pin "90") (pinfunction "PB4_90") (pintype "bidirectional"))
      (node (ref "U504") (pin "11") (pinfunction "INT1_11") (pintype "bidirectional"))
      (node (ref "X503") (pin "3") (pinfunction "S_3") (pintype "passive"))
    )
    (net (code "2") (name "ALARM") (class "Default")
      (node (ref "R701") (pin "P$2") (pinfunction "2_P$2") (pintype "passive"))
      (node (ref "U101") (pin "77") (pinfunction "PA15_77") (pintype "bidirectional"))
    )
    (net (code "3") (name "BATT_CURRENT_SENS") (class "Default")
      (node (ref "R1101") (pin "P$1") (pinfunction "1_P$1") (pintype "passive"))
      (node (ref "U101") (pin "26") (pinfunction "PA3_26") (pintype "bidirectional"))
    )
    (net (code "4") (name "BATT_VOLTAGE_SENS") (class "Default")
      (node (ref "R1102") (pin "P$1") (pinfunction "1_P$1") (pintype "passive"))
      (node (ref "U101") (pin "25") (pinfunction "PA2_25") (pintype "bidirectional"))
    )
    (net (code "5") (name "CAN1_RX") (class "Default")
      (node (ref "U101") (pin "81") (pinfunction "PD0_81") (pintype "bidirectional"))
      (node (ref "U401") (pin "4") (pinfunction "DOUT_4") (pintype "output"))
    )
    (net (code "6") (name "CAN1_TX") (class "Default")
      (node (ref "U101") (pin "82") (pinfunction "PD1_82") (pintype "bidirectional"))
      (node (ref "U401") (pin "1") (pinfunction "DIN_1") (pintype "input"))
    )
    (net (code "7") (name "CAN2_RX") (class "Default")
      (node (ref "R216") (pin "P$1") (pinfunction "1_P$1") (pintype "passive"))
      (node (ref "U101") (pin "51") (pinfunction "PB12_51") (pintype "bidirectional"))
    )
    (net (code "8") (name "CAN2_TX") (class "Default")
      (node (ref "R215") (pin "P$1") (pinfunction "1_P$1") (pintype "passive"))
      (node (ref "U101") (pin "92") (pinfunction "PB6_92") (pintype "bidirectional"))
    )
    (net (code "9") (name "CAN_H") (class "Default")
      (node (ref "CAN_H") (pin "P$1") (pinfunction "P$1_P$1") (pintype "passive"))
      (node (ref "J405") (pin "2") (pinfunction "2_2") (pintype "passive"))
      (node (ref "R409") (pin "P$1") (pinfunction "1_P$1") (pintype "passive"))
      (node (ref "U401") (pin "7") (pinfunction "CANH_7") (pintype "bidirectional"))
    )
    (net (code "10") (name "CAN_L") (class "Default")
      (node (ref "CAN_L") (pin "P$1") (pinfunction "P$1_P$1") (pintype "passive"))
      (node (ref "J405") (pin "3") (pinfunction "3_3") (pintype "passive"))
      (node (ref "R409") (pin "P$2") (pinfunction "2_P$2") (pintype "passive"))
      (node (ref "U401") (pin "6") (pinfunction "CANL_6") (pintype "bidirectional"))
    )
    (net (code "11") (name "FMU-BOOT0") (class "Default")
      (node (ref "FMU-BOOT1101") (pin "P$1") (pinfunction "P$1_P$1") (pintype "passive"))
      (node (ref "R611") (pin "P$2") (pinfunction "2_P$2") (pintype "passive"))
      (node (ref "U101") (pin "94") (pinfunction "BOOT0_94") (pintype "input"))
    )
    (net (code "12") (name "FMU-CH1") (class "Default")
      (node (ref "U101") (pin "45") (pinfunction "PE14_45") (pintype "bidirectional"))
      (node (ref "U901") (pin "7") (pinfunction "A6_7") (pintype "bidirectional"))
    )
    (net (code "13") (name "FMU-CH2") (class "Default")
      (node (ref "U101") (pin "44") (pinfunction "PE13_44") (pintype "bidirectional"))
      (node (ref "U901") (pin "6") (pinfunction "A5_6") (pintype "bidirectional"))
    )
    (net (code "14") (name "FMU-CH3") (class "Default")
      (node (ref "U101") (pin "42") (pinfunction "PE11_42") (pintype "bidirectional"))
      (node (ref "U901") (pin "5") (pinfunction "A4_5") (pintype "bidirectional"))
    )
    (net (code "15") (name "FMU-CH4") (class "Default")
      (node (ref "U101") (pin "40") (pinfunction "PE9_40") (pintype "bidirectional"))
      (node (ref "U901") (pin "4") (pinfunction "A3_4") (pintype "bidirectional"))
    )
    (net (code "16") (name "FMU-CH5") (class "Default")
      (node (ref "U101") (pin "60") (pinfunction "PD13_60") (pintype "bidirectional"))
      (node (ref "U901") (pin "3") (pinfunction "A2_3") (pintype "bidirectional"))
    )
    (net (code "17") (name "FMU-CH6") (class "Default")
      (node (ref "U101") (pin "61") (pinfunction "PD14_61") (pintype "bidirectional"))
      (node (ref "U901") (pin "1") (pinfunction "A1_1") (pintype "bidirectional"))
    )
    (net (code "18") (name "FMU-I2C1_SCL") (class "Default")
      (node (ref "R401") (pin "P$1") (pinfunction "1_P$1") (pintype "passive"))
      (node (ref "R404") (pin "P$1") (pinfunction "1_P$1") (pintype "passive"))
      (node (ref "U101") (pin "95") (pinfunction "PB8_95") (pintype "bidirectional"))
    )
    (net (code "19") (name "FMU-I2C1_SDA") (class "Default")
      (node (ref "R402") (pin "P$1") (pinfunction "1_P$1") (pintype "passive"))
      (node (ref "R405") (pin "P$1") (pinfunction "1_P$1") (pintype "passive"))
      (node (ref "U101") (pin "96") (pinfunction "PB9_96") (pintype "bidirectional"))
    )
    (net (code "20") (name "FMU-I2C2_SCL") (class "Default")
      (node (ref "R306") (pin "P$1") (pinfunction "1_P$1") (pintype "passive"))
      (node (ref "U101") (pin "47") (pinfunction "PB10_47") (pintype "bidirectional"))
      (node (ref "U701") (pin "3") (pinfunction "SCL_3") (pintype "bidirectional"))
    )
    (net (code "21") (name "FMU-I2C2_SDA") (class "Default")
      (node (ref "R307") (pin "P$1") (pinfunction "1_P$1") (pintype "passive"))
      (node (ref "U101") (pin "48") (pinfunction "PB11_48") (pintype "bidirectional"))
      (node (ref "U701") (pin "2") (pinfunction "SDA_2") (pintype "bidirectional"))
    )
    (net (code "22") (name "FMU-SWCLK") (class "Default")
      (node (ref "JX301") (pin "4") (pinfunction "S_4") (pintype "passive"))
      (node (ref "U101") (pin "76") (pinfunction "PA14_76") (pintype "bidirectional"))
    )
    (net (code "23") (name "FMU-SWDIO") (class "Default")
      (node (ref "JX301") (pin "2") (pinfunction "S_2") (pintype "passive"))
      (node (ref "U101") (pin "72") (pinfunction "PA13_72") (pintype "bidirectional"))
    )
    (net (code "24") (name "FMU-SWO") (class "Default")
      (node (ref "JX301") (pin "6") (pinfunction "S_6") (pintype "passive"))
      (node (ref "U101") (pin "89") (pinfunction "PB3_89") (pintype "bidirectional"))
    )
    (net (code "25") (name "FMU-UART4_RX") (class "Default")
      (node (ref "U101") (pin "24") (pinfunction "PA1_24") (pintype "bidirectional"))
      (node (ref "U202") (pin "8") (pinfunction "A7_8") (pintype "bidirectional"))
    )
    (net (code "26") (name "FMU-UART4_TX") (class "Default")
      (node (ref "U101") (pin "23") (pinfunction "PA0_23") (pintype "bidirectional"))
      (node (ref "U202") (pin "9") (pinfunction "A8_9") (pintype "bidirectional"))
    )
    (net (code "27") (name "FMU-UART7_RX") (class "Default")
      (node (ref "U101") (pin "38") (pinfunction "PE7_38") (pintype "bidirectional"))
      (node (ref "U202") (pin "4") (pinfunction "A3_4") (pintype "bidirectional"))
    )
    (net (code "28") (name "FMU-UART7_TX") (class "Default")
      (node (ref "U101") (pin "39") (pinfunction "PE8_39") (pintype "bidirectional"))
      (node (ref "U202") (pin "5") (pinfunction "A4_5") (pintype "bidirectional"))
    )
    (net (code "29") (name "FMU-UART8_RX") (class "Default")
      (node (ref "U101") (pin "97") (pinfunction "PE0_97") (pintype "bidirectional"))
      (node (ref "U202") (pin "6") (pinfunction "A5_6") (pintype "bidirectional"))
    )
    (net (code "30") (name "FMU-UART8_TX") (class "Default")
      (node (ref "U101") (pin "98") (pinfunction "PE1_98") (pintype "bidirectional"))
      (node (ref "U202") (pin "7") (pinfunction "A6_7") (pintype "bidirectional"))
    )
    (net (code "31") (name "FMU-USART2_CTS") (class "Default")
      (node (ref "U101") (pin "84") (pinfunction "PD3_84") (pintype "bidirectional"))
      (node (ref "U201") (pin "9") (pinfunction "A8_9") (pintype "bidirectional"))
    )
    (net (code "32") (name "FMU-USART2_RTS") (class "Default")
      (node (ref "U101") (pin "85") (pinfunction "PD4_85") (pintype "bidirectional"))
      (node (ref "U201") (pin "8") (pinfunction "A7_8") (pintype "bidirectional"))
    )
    (net (code "33") (name "FMU-USART2_RX") (class "Default")
      (node (ref "U101") (pin "87") (pinfunction "PD6_87") (pintype "bidirectional"))
      (node (ref "U201") (pin "6") (pinfunction "A5_6") (pintype "bidirectional"))
    )
    (net (code "34") (name "FMU-USART2_TX") (class "Default")
      (node (ref "U101") (pin "86") (pinfunction "PD5_86") (pintype "bidirectional"))
      (node (ref "U201") (pin "7") (pinfunction "A6_7") (pintype "bidirectional"))
    )
    (net (code "35") (name "FMU-USART3_CTS") (class "Default")
      (node (ref "U101") (pin "58") (pinfunction "PD11_58") (pintype "bidirectional"))
      (node (ref "U201") (pin "3") (pinfunction "A2_3") (pintype "bidirectional"))
    )
    (net (code "36") (name "FMU-USART3_RTS") (class "Default")
      (node (ref "U101") (pin "59") (pinfunction "PD12_59") (pintype "bidirectional"))
      (node (ref "U201") (pin "1") (pinfunction "A1_1") (pintype "bidirectional"))
    )
    (net (code "37") (name "FMU-USART3_RX") (class "Default")
      (node (ref "U101") (pin "56") (pinfunction "PD9_56") (pintype "bidirectional"))
      (node (ref "U201") (pin "4") (pinfunction "A3_4") (pintype "bidirectional"))
    )
    (net (code "38") (name "FMU-USART3_TX") (class "Default")
      (node (ref "U101") (pin "55") (pinfunction "PD8_55") (pintype "bidirectional"))
      (node (ref "U201") (pin "5") (pinfunction "A4_5") (pintype "bidirectional"))
    )
    (net (code "39") (name "FMU-VDD_3V3") (class "Default")
      (node (ref "C101") (pin "P$1") (pinfunction "1_P$1") (pintype "passive"))
      (node (ref "C201") (pin "P$1") (pinfunction "1_P$1") (pintype "passive"))
      (node (ref "C202") (pin "P$1") (pinfunction "1_P$1") (pintype "passive"))
      (node (ref "C402") (pin "P$1") (pinfunction "1_P$1") (pintype "passive"))
      (node (ref "C603") (pin "P$1") (pinfunction "1_P$1") (pintype "passive"))
      (node (ref "C604") (pin "P$1") (pinfunction "1_P$1") (pintype "passive"))
      (node (ref "C606") (pin "P$1") (pinfunction "1_P$1") (pintype "passive"))
      (node (ref "C607") (pin "P$1") (pinfunction "1_P$1") (pintype "passive"))
      (node (ref "C608") (pin "P$1") (pinfunction "1_P$1") (pintype "passive"))
      (node (ref "C610") (pin "P$1") (pinfunction "1_P$1") (pintype "passive"))
      (node (ref "C612") (pin "P$1") (pinfunction "1_P$1") (pintype "passive"))
      (node (ref "C616") (pin "P$1") (pinfunction "1_P$1") (pintype "passive"))
      (node (ref "C701") (pin "P$1") (pinfunction "1_P$1") (pintype "passive"))
      (node (ref "C902") (pin "P$1") (pinfunction "1_P$1") (pintype "passive"))
      (node (ref "D602") (pin "A") (pinfunction "A_A") (pintype "passive"))
      (node (ref "JX301") (pin "1") (pinfunction "S_1") (pintype "passive"))
      (node (ref "R301") (pin "P$2") (pinfunction "2_P$2") (pintype "passive"))
      (node (ref "R302") (pin "P$2") (pinfunction "2_P$2") (pintype "passive"))
      (node (ref "R303") (pin "P$2") (pinfunction "2_P$2") (pintype "passive"))
      (node (ref "R304") (pin "P$2") (pinfunction "2_P$2") (pintype "passive"))
      (node (ref "R305") (pin "P$2") (pinfunction "2_P$2") (pintype "passive"))
      (node (ref "R306") (pin "P$2") (pinfunction "2_P$2") (pintype "passive"))
      (node (ref "R307") (pin "P$2") (pinfunction "2_P$2") (pintype "passive"))
      (node (ref "R401") (pin "P$2") (pinfunction "2_P$2") (pintype "passive"))
      (node (ref "R402") (pin "P$2") (pinfunction "2_P$2") (pintype "passive"))
      (node (ref "R602") (pin "P$2") (pinfunction "2_P$2") (pintype "passive"))
      (node (ref "R604") (pin "P$2") (pinfunction "2_P$2") (pintype "passive"))
      (node (ref "U101") (pin "100") (pinfunction "VDD_100") (pintype "power_in"))
      (node (ref "U101") (pin "11") (pinfunction "VDD_11") (pintype "power_in"))
      (node (ref "U101") (pin "19") (pinfunction "VDD_19") (pintype "power_in"))
      (node (ref "U101") (pin "21") (pinfunction "VREF+_21") (pintype "input"))
      (node (ref "U101") (pin "22") (pinfunction "VDDA_22") (pintype "power_in"))
      (node (ref "U101") (pin "28") (pinfunction "VDD_28") (pintype "power_in"))
      (node (ref "U101") (pin "50") (pinfunction "VDD_50") (pintype "power_in"))
      (node (ref "U101") (pin "75") (pinfunction "VDD_75") (pintype "power_in"))
      (node (ref "U102") (pin "3") (pinfunction "~{W}_3") (pintype "bidirectional"))
      (node (ref "U102") (pin "7") (pinfunction "~{HOLD}_7") (pintype "bidirectional"))
      (node (ref "U102") (pin "8") (pinfunction "VDD_8") (pintype "bidirectional"))
      (node (ref "U201") (pin "10") (pinfunction "OE_10") (pintype "input"))
      (node (ref "U201") (pin "19") (pinfunction "VCCB_19") (pintype "input"))
      (node (ref "U201") (pin "2") (pinfunction "VCCA_2") (pintype "input"))
      (node (ref "U202") (pin "10") (pinfunction "OE_10") (pintype "input"))
      (node (ref "U202") (pin "19") (pinfunction "VCCB_19") (pintype "input"))
      (node (ref "U202") (pin "2") (pinfunction "VCCA_2") (pintype "input"))
      (node (ref "U301") (pin "4") (pinfunction "VCC_4") (pintype "passive"))
      (node (ref "U401") (pin "3") (pinfunction "VCC_3") (pintype "input"))
      (node (ref "U603") (pin "7") (pinfunction "VOUT2_7") (pintype "bidirectional"))
      (node (ref "U701") (pin "1") (pinfunction "~{SHDN}_1") (pintype "input"))
      (node (ref "U701") (pin "10") (pinfunction "VIN_10") (pintype "power_in"))
      (node (ref "U901") (pin "10") (pinfunction "OE_10") (pintype "input"))
      (node (ref "U901") (pin "19") (pinfunction "VCCB_19") (pintype "input"))
      (node (ref "U901") (pin "2") (pinfunction "VCCA_2") (pintype "input"))
      (node (ref "VDD_3V1101") (pin "P$1") (pinfunction "P$1_P$1") (pintype "passive"))
    )
    (net (code "40") (name "FMU-~{RESET}") (class "Default")
      (node (ref "C609") (pin "P$2") (pinfunction "2_P$2") (pintype "passive"))
      (node (ref "R635") (pin "P$1") (pinfunction "1_P$1") (pintype "passive"))
      (node (ref "S601") (pin "A1") (pinfunction "1_A1") (pintype "passive"))
      (node (ref "U101") (pin "14") (pinfunction "NRST_14") (pintype "input"))
      (node (ref "U603") (pin "3") (pinfunction "POR2_3") (pintype "bidirectional"))
      (node (ref "U701") (pin "4") (pinfunction "~{RESET}_4") (pintype "input"))
    )
    (net (code "41") (name "FMU_AUX_ADC1") (class "Default")
      (node (ref "R408") (pin "P$1") (pinfunction "1_P$1") (pintype "passive"))
      (node (ref "U101") (pin "18") (pinfunction "PC3_18") (pintype "bidirectional"))
    )
    (net (code "42") (name "FMU_AUX_ADC2") (class "Default")
      (node (ref "R407") (pin "P$1") (pinfunction "1_P$1") (pintype "passive"))
      (node (ref "U101") (pin "33") (pinfunction "PC4_33") (pintype "bidirectional"))
    )
    (net (code "43") (name "FRAM_MISO") (class "Default")
      (node (ref "U101") (pin "53") (pinfunction "PB14_53") (pintype "bidirectional"))
      (node (ref "U102") (pin "2") (pinfunction "Q_2") (pintype "bidirectional"))
    )
    (net (code "44") (name "FRAM_MOSI") (class "Default")
      (node (ref "U101") (pin "54") (pinfunction "PB15_54") (pintype "bidirectional"))
      (node (ref "U102") (pin "5") (pinfunction "D_5") (pintype "bidirectional"))
    )
    (net (code "45") (name "FRAM_SCK") (class "Default")
      (node (ref "U101") (pin "52") (pinfunction "PB13_52") (pintype "bidirectional"))
      (node (ref "U102") (pin "6") (pinfunction "C_6") (pintype "bidirectional"))
    )
    (net (code "46") (name "GND") (class "Default")
      (node (ref "B601") (pin "2") (pinfunction "NEG_2") (pintype "bidirectional"))
      (node (ref "C1001") (pin "P$2") (pinfunction "2_P$2") (pintype "passive"))
      (node (ref "C1002") (pin "P$2") (pinfunction "2_P$2") (pintype "passive"))
      (node (ref "C1003") (pin "P$2") (pinfunction "2_P$2") (pintype "passive"))
      (node (ref "C1004") (pin "P$2") (pinfunction "2_P$2") (pintype "passive"))
      (node (ref "C1005") (pin "P$2") (pinfunction "2_P$2") (pintype "passive"))
      (node (ref "C1008") (pin "P$2") (pinfunction "2_P$2") (pintype "passive"))
      (node (ref "C101") (pin "P$2") (pinfunction "2_P$2") (pintype "passive"))
      (node (ref "C102") (pin "P$2") (pinfunction "2_P$2") (pintype "passive"))
      (node (ref "C103") (pin "P$1") (pinfunction "1_P$1") (pintype "passive"))
      (node (ref "C1101") (pin "P$2") (pinfunction "2_P$2") (pintype "passive"))
      (node (ref "C1102") (pin "P$2") (pinfunction "2_P$2") (pintype "passive"))
      (node (ref "C1103") (pin "P$2") (pinfunction "2_P$2") (pintype "passive"))
      (node (ref "C1104") (pin "P$2") (pinfunction "2_P$2") (pintype "passive"))
      (node (ref "C1105") (pin "P$2") (pinfunction "2_P$2") (pintype "passive"))
      (node (ref "C1106") (pin "P$2") (pinfunction "2_P$2") (pintype "passive"))
      (node (ref "C1107") (pin "P$2") (pinfunction "2_P$2") (pintype "passive"))
      (node (ref "C1108") (pin "P$2") (pinfunction "2_P$2") (pintype "passive"))
      (node (ref "C1109") (pin "P$2") (pinfunction "2_P$2") (pintype "passive"))
      (node (ref "C1110") (pin "P$2") (pinfunction "2_P$2") (pintype "passive"))
      (node (ref "C201") (pin "P$2") (pinfunction "2_P$2") (pintype "passive"))
      (node (ref "C202") (pin "P$2") (pinfunction "2_P$2") (pintype "passive"))
      (node (ref "C401") (pin "P$2") (pinfunction "2_P$2") (pintype "passive"))
      (node (ref "C402") (pin "P$2") (pinfunction "2_P$2") (pintype "passive"))
      (node (ref "C501") (pin "P$2") (pinfunction "2_P$2") (pintype "passive"))
      (node (ref "C502") (pin "P$2") (pinfunction "2_P$2") (pintype "passive"))
      (node (ref "C503") (pin "P$2") (pinfunction "2_P$2") (pintype "passive"))
      (node (ref "C504") (pin "P$2") (pinfunction "2_P$2") (pintype "passive"))
      (node (ref "C505") (pin "P$2") (pinfunction "2_P$2") (pintype "passive"))
      (node (ref "C506") (pin "P$2") (pinfunction "2_P$2") (pintype "passive"))
      (node (ref "C507") (pin "P$2") (pinfunction "2_P$2") (pintype "passive"))
      (node (ref "C508") (pin "P$2") (pinfunction "2_P$2") (pintype "passive"))
      (node (ref "C509") (pin "P$2") (pinfunction "2_P$2") (pintype "passive"))
      (node (ref "C511") (pin "P$2") (pinfunction "2_P$2") (pintype "passive"))
      (node (ref "C512") (pin "P$2") (pinfunction "2_P$2") (pintype "passive"))
      (node (ref "C513") (pin "P$2") (pinfunction "2_P$2") (pintype "passive"))
      (node (ref "C514") (pin "P$2") (pinfunction "2_P$2") (pintype "passive"))
      (node (ref "C515") (pin "P$2") (pinfunction "2_P$2") (pintype "passive"))
      (node (ref "C601") (pin "P$2") (pinfunction "2_P$2") (pintype "passive"))
      (node (ref "C602") (pin "P$1") (pinfunction "1_P$1") (pintype "passive"))
      (node (ref "C603") (pin "P$2") (pinfunction "2_P$2") (pintype "passive"))
      (node (ref "C604") (pin "P$2") (pinfunction "2_P$2") (pintype "passive"))
      (node (ref "C605") (pin "P$2") (pinfunction "2_P$2") (pintype "passive"))
      (node (ref "C606") (pin "P$2") (pinfunction "2_P$2") (pintype "passive"))
      (node (ref "C607") (pin "P$2") (pinfunction "2_P$2") (pintype "passive"))
      (node (ref "C608") (pin "P$2") (pinfunction "2_P$2") (pintype "passive"))
      (node (ref "C609") (pin "P$1") (pinfunction "1_P$1") (pintype "passive"))
      (node (ref "C610") (pin "P$2") (pinfunction "2_P$2") (pintype "passive"))
      (node (ref "C611") (pin "P$2") (pinfunction "2_P$2") (pintype "passive"))
      (node (ref "C612") (pin "P$2") (pinfunction "2_P$2") (pintype "passive"))
      (node (ref "C613") (pin "P$2") (pinfunction "2_P$2") (pintype "passive"))
      (node (ref "C614") (pin "P$2") (pinfunction "2_P$2") (pintype "passive"))
      (node (ref "C615") (pin "P$2") (pinfunction "2_P$2") (pintype "passive"))
      (node (ref "C616") (pin "P$2") (pinfunction "2_P$2") (pintype "passive"))
      (node (ref "C617") (pin "P$2") (pinfunction "2_P$2") (pintype "passive"))
      (node (ref "C618") (pin "P$2") (pinfunction "2_P$2") (pintype "passive"))
      (node (ref "C701") (pin "P$2") (pinfunction "2_P$2") (pintype "passive"))
      (node (ref "C702") (pin "P$2") (pinfunction "2_P$2") (pintype "passive"))
      (node (ref "C703") (pin "P$2") (pinfunction "2_P$2") (pintype "passive"))
      (node (ref "C704") (pin "P$2") (pinfunction "2_P$2") (pintype "passive"))
      (node (ref "C801") (pin "P$1") (pinfunction "1_P$1") (pintype "passive"))
      (node (ref "C802") (pin "P$2") (pinfunction "2_P$2") (pintype "passive"))
      (node (ref "C803") (pin "P$2") (pinfunction "2_P$2") (pintype "passive"))
      (node (ref "C804") (pin "P$2") (pinfunction "2_P$2") (pintype "passive"))
      (node (ref "C805") (pin "P$2") (pinfunction "2_P$2") (pintype "passive"))
      (node (ref "C806") (pin "P$1") (pinfunction "1_P$1") (pintype "passive"))
      (node (ref "C901") (pin "P$2") (pinfunction "2_P$2") (pintype "passive"))
      (node (ref "C902") (pin "P$2") (pinfunction "2_P$2") (pintype "passive"))
      (node (ref "C903") (pin "P$2") (pinfunction "2_P$2") (pintype "passive"))
      (node (ref "D201") (pin "A") (pinfunction "A_A") (pintype "passive"))
      (node (ref "D202") (pin "A") (pinfunction "A_A") (pintype "passive"))
      (node (ref "D203") (pin "A") (pinfunction "A_A") (pintype "passive"))
      (node (ref "D401") (pin "A") (pinfunction "A_A") (pintype "passive"))
      (node (ref "D402") (pin "A") (pinfunction "A_A") (pintype "passive"))
      (node (ref "D403") (pin "A") (pinfunction "A_A") (pintype "passive"))
      (node (ref "D404") (pin "A") (pinfunction "A_A") (pintype "passive"))
      (node (ref "D701") (pin "A") (pinfunction "A_A") (pintype "passive"))
      (node (ref "D801") (pin "A") (pinfunction "A_A") (pintype "passive"))
      (node (ref "D901") (pin "A") (pinfunction "A_A") (pintype "passive"))
      (node (ref "D902") (pin "A") (pinfunction "A_A") (pintype "passive"))
      (node (ref "D903") (pin "A") (pinfunction "A_A") (pintype "passive"))
      (node (ref "GND") (pin "P$1") (pinfunction "P$1_P$1") (pintype "passive"))
      (node (ref "GND.") (pin "P$1") (pinfunction "P$1_P$1") (pintype "passive"))
      (node (ref "J201") (pin "6") (pinfunction "6_6") (pintype "passive"))
      (node (ref "J202") (pin "6") (pinfunction "6_6") (pintype "passive"))
      (node (ref "J203") (pin "6") (pinfunction "6_6") (pintype "passive"))
      (node (ref "J204") (pin "6") (pinfunction "6_6") (pintype "passive"))
      (node (ref "J301") (pin "GND") (pinfunction "5_GND") (pintype "power_in"))
      (node (ref "J301") (pin "GND1") (pinfunction "GND1_GND1") (pintype "bidirectional"))
      (node (ref "J301") (pin "GND2") (pinfunction "GND2_GND2") (pintype "bidirectional"))
      (node (ref "J301") (pin "GND3") (pinfunction "GND3_GND3") (pintype "bidirectional"))
      (node (ref "J301") (pin "GND4") (pinfunction "GND4_GND4") (pintype "bidirectional"))
      (node (ref "J302") (pin "4") (pinfunction "4_4") (pintype "passive"))
      (node (ref "J401") (pin "4") (pinfunction "4_4") (pintype "passive"))
      (node (ref "J402") (pin "3") (pinfunction "3_3") (pintype "passive"))
      (node (ref "J403") (pin "7") (pinfunction "7_7") (pintype "passive"))
      (node (ref "J404") (pin "3") (pinfunction "3_3") (pintype "passive"))
      (node (ref "J404") (pin "5") (pinfunction "5_5") (pintype "passive"))
      (node (ref "J405") (pin "4") (pinfunction "4_4") (pintype "passive"))
      (node (ref "J601") (pin "5") (pinfunction "5_5") (pintype "passive"))
      (node (ref "J601") (pin "6") (pinfunction "6_6") (pintype "passive"))
      (node (ref "J701") (pin "2") (pinfunction "2_2") (pintype "passive"))
      (node (ref "J801") (pin "P$2") (pinfunction "P$2_P$2") (pintype "bidirectional"))
      (node (ref "J901") (pin "12") (pinfunction "S_12") (pintype "passive"))
      (node (ref "J901") (pin "15") (pinfunction "S_15") (pintype "passive"))
      (node (ref "J901") (pin "18") (pinfunction "S_18") (pintype "passive"))
      (node (ref "J901") (pin "21") (pinfunction "S_21") (pintype "passive"))
      (node (ref "J901") (pin "24") (pinfunction "S_24") (pintype "passive"))
      (node (ref "J901") (pin "27") (pinfunction "S_27") (pintype "passive"))
      (node (ref "J901") (pin "3") (pinfunction "S_3") (pintype "passive"))
      (node (ref "J901") (pin "30") (pinfunction "S_30") (pintype "passive"))
      (node (ref "J901") (pin "33") (pinfunction "S_33") (pintype "passive"))
      (node (ref "J901") (pin "36") (pinfunction "S_36") (pintype "passive"))
      (node (ref "J901") (pin "39") (pinfunction "S_39") (pintype "passive"))
      (node (ref "J901") (pin "42") (pinfunction "S_42") (pintype "passive"))
      (node (ref "J901") (pin "45") (pinfunction "S_45") (pintype "passive"))
      (node (ref "J901") (pin "48") (pinfunction "S_48") (pintype "passive"))
      (node (ref "J901") (pin "6") (pinfunction "S_6") (pintype "passive"))
      (node (ref "J901") (pin "9") (pinfunction "S_9") (pintype "passive"))
      (node (ref "JX301") (pin "3") (pinfunction "S_3") (pintype "passive"))
      (node (ref "JX301") (pin "5") (pinfunction "S_5") (pintype "passive"))
      (node (ref "JX301") (pin "9") (pinfunction "S_9") (pintype "passive"))
      (node (ref "JX801") (pin "3") (pinfunction "GND_3") (pintype "bidirectional"))
      (node (ref "JX802") (pin "3") (pinfunction "S_3") (pintype "passive"))
      (node (ref "JX802") (pin "5") (pinfunction "S_5") (pintype "passive"))
      (node (ref "JX802") (pin "9") (pinfunction "S_9") (pintype "passive"))
      (node (ref "L1101") (pin "P$3") (pinfunction "P$3_P$3") (pintype "bidirectional"))
      (node (ref "L1101") (pin "P$4") (pinfunction "P$3_P$4") (pintype "bidirectional"))
      (node (ref "L1101") (pin "P$5") (pinfunction "P$3_P$5") (pintype "bidirectional"))
      (node (ref "L1102") (pin "P$3") (pinfunction "P$3_P$3") (pintype "bidirectional"))
      (node (ref "L1102") (pin "P$4") (pinfunction "P$3_P$4") (pintype "bidirectional"))
      (node (ref "L1102") (pin "P$5") (pinfunction "P$3_P$5") (pintype "bidirectional"))
      (node (ref "L201") (pin "P$3") (pinfunction "P$3_P$3") (pintype "bidirectional"))
      (node (ref "L201") (pin "P$4") (pinfunction "P$3_P$4") (pintype "bidirectional"))
      (node (ref "L201") (pin "P$5") (pinfunction "P$3_P$5") (pintype "bidirectional"))
      (node (ref "L202") (pin "P$3") (pinfunction "P$3_P$3") (pintype "bidirectional"))
      (node (ref "L202") (pin "P$4") (pinfunction "P$3_P$4") (pintype "bidirectional"))
      (node (ref "L202") (pin "P$5") (pinfunction "P$3_P$5") (pintype "bidirectional"))
      (node (ref "L203") (pin "P$3") (pinfunction "P$3_P$3") (pintype "bidirectional"))
      (node (ref "L203") (pin "P$4") (pinfunction "P$3_P$4") (pintype "bidirectional"))
      (node (ref "L203") (pin "P$5") (pinfunction "P$3_P$5") (pintype "bidirectional"))
      (node (ref "L401") (pin "P$3") (pinfunction "P$3_P$3") (pintype "bidirectional"))
      (node (ref "L401") (pin "P$4") (pinfunction "P$3_P$4") (pintype "bidirectional"))
      (node (ref "L401") (pin "P$5") (pinfunction "P$3_P$5") (pintype "bidirectional"))
      (node (ref "L402") (pin "P$3") (pinfunction "P$3_P$3") (pintype "bidirectional"))
      (node (ref "L402") (pin "P$4") (pinfunction "P$3_P$4") (pintype "bidirectional"))
      (node (ref "L402") (pin "P$5") (pinfunction "P$3_P$5") (pintype "bidirectional"))
      (node (ref "L403") (pin "P$3") (pinfunction "P$3_P$3") (pintype "bidirectional"))
      (node (ref "L403") (pin "P$4") (pinfunction "P$3_P$4") (pintype "bidirectional"))
      (node (ref "L403") (pin "P$5") (pinfunction "P$3_P$5") (pintype "bidirectional"))
      (node (ref "L404") (pin "P$3") (pinfunction "P$3_P$3") (pintype "bidirectional"))
      (node (ref "L404") (pin "P$4") (pinfunction "P$3_P$4") (pintype "bidirectional"))
      (node (ref "L404") (pin "P$5") (pinfunction "P$3_P$5") (pintype "bidirectional"))
      (node (ref "L603") (pin "P$3") (pinfunction "P$3_P$3") (pintype "bidirectional"))
      (node (ref "L603") (pin "P$4") (pinfunction "P$3_P$4") (pintype "bidirectional"))
      (node (ref "L603") (pin "P$5") (pinfunction "P$3_P$5") (pintype "bidirectional"))
      (node (ref "L901") (pin "P$3") (pinfunction "P$3_P$3") (pintype "bidirectional"))
      (node (ref "L901") (pin "P$4") (pinfunction "P$3_P$4") (pintype "bidirectional"))
      (node (ref "L901") (pin "P$5") (pinfunction "P$3_P$5") (pintype "bidirectional"))
      (node (ref "R1001") (pin "P$1") (pinfunction "1_P$1") (pintype "passive"))
      (node (ref "R1002") (pin "P$1") (pinfunction "1_P$1") (pintype "passive"))
      (node (ref "R102") (pin "P$2") (pinfunction "2_P$2") (pintype "passive"))
      (node (ref "R1103") (pin "P$2") (pinfunction "2_P$2") (pintype "passive"))
      (node (ref "R1104") (pin "P$2") (pinfunction "2_P$2") (pintype "passive"))
      (node (ref "R1107") (pin "P$2") (pinfunction "2_P$2") (pintype "passive"))
      (node (ref "R1111") (pin "P$2") (pinfunction "2_P$2") (pintype "passive"))
      (node (ref "R1114") (pin "P$2") (pinfunction "2_P$2") (pintype "passive"))
      (node (ref "R1115") (pin "P$1") (pinfunction "1_P$1") (pintype "passive"))
      (node (ref "R403") (pin "P$1") (pinfunction "1_P$1") (pintype "passive"))
      (node (ref "R610") (pin "P$2") (pinfunction "2_P$2") (pintype "passive"))
      (node (ref "R611") (pin "P$1") (pinfunction "1_P$1") (pintype "passive"))
      (node (ref "R615") (pin "P$2") (pinfunction "2_P$2") (pintype "passive"))
      (node (ref "R616") (pin "P$2") (pinfunction "2_P$2") (pintype "passive"))
      (node (ref "R617") (pin "P$2") (pinfunction "2_P$2") (pintype "passive"))
      (node (ref "R621") (pin "1") (pinfunction "1_1") (pintype "passive"))
      (node (ref "R702") (pin "P$2") (pinfunction "2_P$2") (pintype "passive"))
      (node (ref "R704") (pin "P$1") (pinfunction "1_P$1") (pintype "passive"))
      (node (ref "R706") (pin "P$2") (pinfunction "2_P$2") (pintype "passive"))
      (node (ref "R708") (pin "P$1") (pinfunction "1_P$1") (pintype "passive"))
      (node (ref "R711") (pin "P$1") (pinfunction "1_P$1") (pintype "passive"))
      (node (ref "R713") (pin "P$2") (pinfunction "2_P$2") (pintype "passive"))
      (node (ref "R801") (pin "P$2") (pinfunction "2_P$2") (pintype "passive"))
      (node (ref "R802") (pin "P$2") (pinfunction "2_P$2") (pintype "passive"))
      (node (ref "R919") (pin "P$1") (pinfunction "1_P$1") (pintype "passive"))
      (node (ref "S601") (pin "B3") (pinfunction "2_B3") (pintype "passive"))
      (node (ref "S801") (pin "B3") (pinfunction "2_B3") (pintype "passive"))
      (node (ref "U1001") (pin "2") (pinfunction "VSS_2") (pintype "bidirectional"))
      (node (ref "U1001") (pin "5") (pinfunction "~{CE}_5") (pintype "bidirectional"))
      (node (ref "U1001") (pin "6") (pinfunction "VBAT_6") (pintype "bidirectional"))
      (node (ref "U1001") (pin "GND") (pinfunction "VSS_GND") (pintype "bidirectional"))
      (node (ref "U1001") (pin "P$2") (pinfunction "VSS_P$2") (pintype "bidirectional"))
      (node (ref "U1001") (pin "P$3") (pinfunction "VSS_P$3") (pintype "bidirectional"))
      (node (ref "U1002") (pin "2") (pinfunction "GND_2") (pintype "bidirectional"))
      (node (ref "U1002") (pin "GND") (pinfunction "GND_GND") (pintype "bidirectional"))
      (node (ref "U101") (pin "10") (pinfunction "VSS_10") (pintype "power_in"))
      (node (ref "U101") (pin "20") (pinfunction "VSSA_20") (pintype "power_in"))
      (node (ref "U101") (pin "27") (pinfunction "VSS_27") (pintype "power_in"))
      (node (ref "U101") (pin "74") (pinfunction "VSS_74") (pintype "power_in"))
      (node (ref "U101") (pin "99") (pinfunction "VSS_99") (pintype "power_in"))
      (node (ref "U102") (pin "4") (pinfunction "VSS_4") (pintype "bidirectional"))
      (node (ref "U1101") (pin "P$10") (pinfunction "GND_P$10") (pintype "bidirectional"))
      (node (ref "U1101") (pin "P$25") (pinfunction "GND_P$25") (pintype "bidirectional"))
      (node (ref "U201") (pin "11") (pinfunction "GND_11") (pintype "power_in"))
      (node (ref "U202") (pin "11") (pinfunction "GND_11") (pintype "power_in"))
      (node (ref "U301") (pin "6") (pinfunction "GND_6") (pintype "power_in"))
      (node (ref "U302") (pin "2") (pinfunction "GND_2") (pintype "bidirectional"))
      (node (ref "U401") (pin "2") (pinfunction "GND_2") (pintype "power_in"))
      (node (ref "U401") (pin "5") (pinfunction "SHDN_5") (pintype "input"))
      (node (ref "U401") (pin "8") (pinfunction "RS_8") (pintype "input"))
      (node (ref "U501") (pin "10") (pinfunction "RES_P10_GND_10") (pintype "bidirectional"))
      (node (ref "U501") (pin "11") (pinfunction "RES_P11_GND_11") (pintype "bidirectional"))
      (node (ref "U501") (pin "12") (pinfunction "RES_P12_GND_12") (pintype "bidirectional"))
      (node (ref "U501") (pin "13") (pinfunction "GND_13") (pintype "bidirectional"))
      (node (ref "U501") (pin "8") (pinfunction "RES_P8_GND_8") (pintype "bidirectional"))
      (node (ref "U501") (pin "9") (pinfunction "RES_P9_GND_9") (pintype "bidirectional"))
      (node (ref "U502") (pin "10") (pinfunction "GND_10") (pintype "bidirectional"))
      (node (ref "U502") (pin "11") (pinfunction "GND_11") (pintype "bidirectional"))
      (node (ref "U502") (pin "12") (pinfunction "GND_12") (pintype "bidirectional"))
      (node (ref "U502") (pin "13") (pinfunction "GND_13") (pintype "bidirectional"))
      (node (ref "U502") (pin "9") (pinfunction "GND_9") (pintype "bidirectional"))
      (node (ref "U504") (pin "10") (pinfunction "RSRV_10") (pintype "bidirectional"))
      (node (ref "U504") (pin "12") (pinfunction "GND_12") (pintype "bidirectional"))
      (node (ref "U504") (pin "13") (pinfunction "GND_13") (pintype "bidirectional"))
      (node (ref "U504") (pin "16") (pinfunction "GND_16") (pintype "bidirectional"))
      (node (ref "U504") (pin "5") (pinfunction "GND_5") (pintype "bidirectional"))
      (node (ref "U505") (pin "1") (pinfunction "CLKIN_1") (pintype "bidirectional"))
      (node (ref "U505") (pin "18") (pinfunction "GND_18") (pintype "bidirectional"))
      (node (ref "U506") (pin "2") (pinfunction "PS_2") (pintype "bidirectional"))
      (node (ref "U506") (pin "3") (pinfunction "GND_3") (pintype "bidirectional"))
      (node (ref "U601") (pin "2") (pinfunction "VSS_2") (pintype "bidirectional"))
      (node (ref "U601") (pin "6") (pinfunction "VBAT_6") (pintype "bidirectional"))
      (node (ref "U601") (pin "GND") (pinfunction "VSS_GND") (pintype "bidirectional"))
      (node (ref "U601") (pin "P$2") (pinfunction "VSS_P$2") (pintype "bidirectional"))
      (node (ref "U601") (pin "P$3") (pinfunction "VSS_P$3") (pintype "bidirectional"))
      (node (ref "U602") (pin "2") (pinfunction "VSS_2") (pintype "bidirectional"))
      (node (ref "U602") (pin "6") (pinfunction "VBAT_6") (pintype "bidirectional"))
      (node (ref "U602") (pin "GND") (pinfunction "VSS_GND") (pintype "bidirectional"))
      (node (ref "U602") (pin "P$2") (pinfunction "VSS_P$2") (pintype "bidirectional"))
      (node (ref "U602") (pin "P$3") (pinfunction "VSS_P$3") (pintype "bidirectional"))
      (node (ref "U603") (pin "2") (pinfunction "GND_2") (pintype "bidirectional"))
      (node (ref "U603") (pin "GND") (pinfunction "GND_GND") (pintype "bidirectional"))
      (node (ref "U701") (pin "5") (pinfunction "GND_5") (pintype "power_in"))
      (node (ref "U702") (pin "4") (pinfunction "GND_4") (pintype "power_in"))
      (node (ref "U801") (pin "23") (pinfunction "VSS_1_23") (pintype "power_in"))
      (node (ref "U801") (pin "35") (pinfunction "VSS_2_35") (pintype "power_in"))
      (node (ref "U801") (pin "47") (pinfunction "VSS_3_47") (pintype "power_in"))
      (node (ref "U801") (pin "8") (pinfunction "VSSA_8") (pintype "power_in"))
      (node (ref "U901") (pin "11") (pinfunction "GND_11") (pintype "power_in"))
      (node (ref "U902") (pin "11") (pinfunction "GND_11") (pintype "power_in"))
      (node (ref "U903") (pin "1") (pinfunction "~{1OE}_1") (pintype "input"))
      (node (ref "U903") (pin "4") (pinfunction "GND_4") (pintype "power_in"))
      (node (ref "X101") (pin "2") (pinfunction "NC_2_2") (pintype "power_in"))
      (node (ref "X101") (pin "4") (pinfunction "NC_4_4") (pintype "power_in"))
      (node (ref "X503") (pin "2") (pinfunction "S_2") (pintype "passive"))
      (node (ref "X801") (pin "2") (pinfunction "NC_2_2") (pintype "power_in"))
      (node (ref "X801") (pin "4") (pinfunction "NC_4_4") (pintype "power_in"))
    )
    (net (code "47") (name "GPIO_EXT_1") (class "Default")
      (node (ref "J403") (pin "6") (pinfunction "6_6") (pintype "passive"))
      (node (ref "U101") (pin "8") (pinfunction "PC14_8") (pintype "bidirectional"))
    )
    (net (code "48") (name "GYRO_DRDY") (class "Default")
      (node (ref "U101") (pin "35") (pinfunction "PB0_35") (pintype "bidirectional"))
      (node (ref "U501") (pin "6") (pinfunction "DRDY/INT2_6") (pintype "output"))
      (node (ref "U502") (pin "6") (pinfunction "DRDY/INT2_6") (pintype "bidirectional"))
      (node (ref "X503") (pin "5") (pinfunction "S_5") (pintype "passive"))
    )
    (net (code "49") (name "IO-BOOT0") (class "Default")
      (node (ref "IO-BOOT1101") (pin "P$1") (pinfunction "P$1_P$1") (pintype "passive"))
      (node (ref "R801") (pin "P$1") (pinfunction "1_P$1") (pintype "passive"))
      (node (ref "U801") (pin "44") (pinfunction "BOOT0_44") (pintype "input"))
    )
    (net (code "50") (name "IO-CH1") (class "Default")
      (node (ref "U801") (pin "10") (pinfunction "PA0_10") (pintype "bidirectional"))
      (node (ref "U902") (pin "9") (pinfunction "A8_9") (pintype "bidirectional"))
    )
    (net (code "51") (name "IO-CH2") (class "Default")
      (node (ref "U801") (pin "11") (pinfunction "PA1_11") (pintype "bidirectional"))
      (node (ref "U902") (pin "8") (pinfunction "A7_8") (pintype "bidirectional"))
    )
    (net (code "52") (name "IO-CH3") (class "Default")
      (node (ref "U801") (pin "45") (pinfunction "PB8_45") (pintype "bidirectional"))
      (node (ref "U902") (pin "7") (pinfunction "A6_7") (pintype "bidirectional"))
    )
    (net (code "53") (name "IO-CH4") (class "Default")
      (node (ref "U801") (pin "46") (pinfunction "PB9_46") (pintype "bidirectional"))
      (node (ref "U902") (pin "6") (pinfunction "A5_6") (pintype "bidirectional"))
    )
    (net (code "54") (name "IO-CH5") (class "Default")
      (node (ref "U801") (pin "16") (pinfunction "PA6_16") (pintype "bidirectional"))
      (node (ref "U902") (pin "5") (pinfunction "A4_5") (pintype "bidirectional"))
    )
    (net (code "55") (name "IO-CH6") (class "Default")
      (node (ref "U801") (pin "17") (pinfunction "PA7_17") (pintype "bidirectional"))
      (node (ref "U902") (pin "4") (pinfunction "A3_4") (pintype "bidirectional"))
    )
    (net (code "56") (name "IO-CH7") (class "Default")
      (node (ref "U801") (pin "18") (pinfunction "PB0_18") (pintype "bidirectional"))
      (node (ref "U902") (pin "3") (pinfunction "A2_3") (pintype "bidirectional"))
    )
    (net (code "57") (name "IO-CH8") (class "Default")
      (node (ref "U801") (pin "19") (pinfunction "PB1_19") (pintype "bidirectional"))
      (node (ref "U902") (pin "1") (pinfunction "A1_1") (pintype "bidirectional"))
    )
    (net (code "58") (name "IO-SWCLK") (class "Default")
      (node (ref "JX802") (pin "4") (pinfunction "S_4") (pintype "passive"))
      (node (ref "U801") (pin "37") (pinfunction "PA14_37") (pintype "bidirectional"))
    )
    (net (code "59") (name "IO-SWDIO") (class "Default")
      (node (ref "JX802") (pin "2") (pinfunction "S_2") (pintype "passive"))
      (node (ref "U801") (pin "34") (pinfunction "PA13_34") (pintype "bidirectional"))
    )
    (net (code "60") (name "IO-SWO") (class "Default")
      (node (ref "JX802") (pin "6") (pinfunction "S_6") (pintype "passive"))
      (node (ref "U801") (pin "39") (pinfunction "PB3_39") (pintype "bidirectional"))
    )
    (net (code "61") (name "IO-USART1_RX") (class "Default")
      (node (ref "J801") (pin "P$3") (pinfunction "P$3_P$3") (pintype "bidirectional"))
      (node (ref "JX801") (pin "2") (pinfunction "+5V_2") (pintype "bidirectional"))
      (node (ref "U801") (pin "31") (pinfunction "PA10_31") (pintype "bidirectional"))
    )
    (net (code "62") (name "IO-USART1_TX") (class "Default")
      (node (ref "JX801") (pin "1") (pinfunction "PPM_1") (pintype "bidirectional"))
      (node (ref "R101") (pin "P$2") (pinfunction "2_P$2") (pintype "passive"))
      (node (ref "U801") (pin "30") (pinfunction "PA9_30") (pintype "bidirectional"))
    )
    (net (code "63") (name "IO-VDD_3V3") (class "Default")
      (node (ref "C1003") (pin "P$1") (pinfunction "1_P$1") (pintype "passive"))
      (node (ref "C1004") (pin "P$1") (pinfunction "1_P$1") (pintype "passive"))
      (node (ref "C802") (pin "P$1") (pinfunction "1_P$1") (pintype "passive"))
      (node (ref "C803") (pin "P$1") (pinfunction "1_P$1") (pintype "passive"))
      (node (ref "C804") (pin "P$1") (pinfunction "1_P$1") (pintype "passive"))
      (node (ref "C901") (pin "P$1") (pinfunction "1_P$1") (pintype "passive"))
      (node (ref "C903") (pin "P$1") (pinfunction "1_P$1") (pintype "passive"))
      (node (ref "D701") (pin "C") (pinfunction "C_C") (pintype "passive"))
      (node (ref "J702") (pin "1") (pinfunction "1_1") (pintype "passive"))
      (node (ref "JX802") (pin "1") (pinfunction "S_1") (pintype "passive"))
      (node (ref "U1002") (pin "7") (pinfunction "VOUT2_7") (pintype "bidirectional"))
      (node (ref "U801") (pin "24") (pinfunction "VDD_1_24") (pintype "power_in"))
      (node (ref "U801") (pin "36") (pinfunction "VDD_2_36") (pintype "power_in"))
      (node (ref "U801") (pin "48") (pinfunction "VDD_3_48") (pintype "power_in"))
      (node (ref "U801") (pin "9") (pinfunction "VDDA_9") (pintype "power_in"))
      (node (ref "U902") (pin "10") (pinfunction "OE_10") (pintype "input"))
      (node (ref "U902") (pin "19") (pinfunction "VCCB_19") (pintype "input"))
      (node (ref "U902") (pin "2") (pinfunction "VCCA_2") (pintype "input"))
      (node (ref "U903") (pin "8") (pinfunction "VCC_8") (pintype "power_in"))
    )
    (net (code "64") (name "IO-VDD_5V5") (class "Default")
      (node (ref "C1001") (pin "P$1") (pinfunction "1_P$1") (pintype "passive"))
      (node (ref "C1005") (pin "P$1") (pinfunction "1_P$1") (pintype "passive"))
      (node (ref "D1001") (pin "3") (pinfunction "CC_3") (pintype "passive"))
      (node (ref "J901") (pin "2") (pinfunction "S_2") (pintype "passive"))
      (node (ref "LED702") (pin "A") (pinfunction "A_A") (pintype "passive"))
      (node (ref "LED703") (pin "A") (pinfunction "A_A") (pintype "passive"))
      (node (ref "LED705") (pin "A") (pinfunction "A_A") (pintype "passive"))
      (node (ref "U1002") (pin "1") (pinfunction "VIN_1") (pintype "bidirectional"))
      (node (ref "U1002") (pin "4") (pinfunction "EN2_4") (pintype "bidirectional"))
    )
    (net (code "65") (name "IO-~{RESET}") (class "Default")
      (node (ref "C801") (pin "P$2") (pinfunction "2_P$2") (pintype "passive"))
      (node (ref "S801") (pin "A1") (pinfunction "1_A1") (pintype "passive"))
      (node (ref "U1002") (pin "3") (pinfunction "POR2_3") (pintype "bidirectional"))
      (node (ref "U801") (pin "7") (pinfunction "NRST_7") (pintype "input"))
    )
    (net (code "66") (name "IO-~{VDD_SERVO_IN_FAULT}") (class "Default")
      (node (ref "U1001") (pin "4") (pinfunction "~{FAULT}_4") (pintype "bidirectional"))
      (node (ref "U801") (pin "38") (pinfunction "PA15_38") (pintype "bidirectional"))
    )
    (net (code "67") (name "MAG_DRDY") (class "Default")
      (node (ref "U101") (pin "36") (pinfunction "PB1_36") (pintype "bidirectional"))
      (node (ref "U504") (pin "9") (pinfunction "INT2_9") (pintype "bidirectional"))
      (node (ref "X503") (pin "4") (pinfunction "S_4") (pintype "passive"))
    )
    (net (code "68") (name "MPU_DRDY") (class "Default")
      (node (ref "U101") (pin "62") (pinfunction "PD15_62") (pintype "bidirectional"))
      (node (ref "U505") (pin "12") (pinfunction "INT_12") (pintype "bidirectional"))
    )
    (net (code "69") (name "Net-(C102-1)") (class "Default")
      (node (ref "C102") (pin "P$1") (pinfunction "1_P$1") (pintype "passive"))
      (node (ref "U101") (pin "12") (pinfunction "OSC_IN_12") (pintype "input"))
      (node (ref "X101") (pin "3") (pinfunction "3_3") (pintype "bidirectional"))
    )
    (net (code "70") (name "Net-(C103-2)") (class "Default")
      (node (ref "C103") (pin "P$2") (pinfunction "2_P$2") (pintype "passive"))
      (node (ref "U101") (pin "13") (pinfunction "OSC_OUT_13") (pintype "output"))
      (node (ref "X101") (pin "1") (pinfunction "1_1") (pintype "bidirectional"))
    )
    (net (code "71") (name "Net-(C504-1)") (class "Default")
      (node (ref "C504") (pin "P$1") (pinfunction "1_P$1") (pintype "passive"))
      (node (ref "U501") (pin "14") (pinfunction "PLLFILT_14") (pintype "bidirectional"))
    )
    (net (code "72") (name "Net-(C505-1)") (class "Default")
      (node (ref "C505") (pin "P$1") (pinfunction "1_P$1") (pintype "passive"))
      (node (ref "U502") (pin "14") (pinfunction "CAP_14") (pintype "bidirectional"))
    )
    (net (code "73") (name "Net-(C509-1)") (class "Default")
      (node (ref "C509") (pin "P$1") (pinfunction "1_P$1") (pintype "passive"))
      (node (ref "U504") (pin "15") (pinfunction "C1_15") (pintype "bidirectional"))
    )
    (net (code "74") (name "Net-(C510-1)") (class "Default")
      (node (ref "C510") (pin "P$1") (pinfunction "1_P$1") (pintype "passive"))
      (node (ref "U504") (pin "2") (pinfunction "SETC_2") (pintype "bidirectional"))
    )
    (net (code "75") (name "Net-(C510-2)") (class "Default")
      (node (ref "C510") (pin "P$2") (pinfunction "2_P$2") (pintype "passive"))
      (node (ref "U504") (pin "3") (pinfunction "SETP_3") (pintype "bidirectional"))
    )
    (net (code "76") (name "Net-(C512-1)") (class "Default")
      (node (ref "C512") (pin "P$1") (pinfunction "1_P$1") (pintype "passive"))
      (node (ref "U505") (pin "10") (pinfunction "REGOUT_10") (pintype "bidirectional"))
    )
    (net (code "77") (name "Net-(C515-1)") (class "Default")
      (node (ref "C515") (pin "P$1") (pinfunction "1_P$1") (pintype "passive"))
      (node (ref "U505") (pin "20") (pinfunction "CPOUT_20") (pintype "bidirectional"))
    )
    (net (code "78") (name "Net-(C601-1)") (class "Default")
      (node (ref "C601") (pin "P$1") (pinfunction "1_P$1") (pintype "passive"))
      (node (ref "C615") (pin "P$1") (pinfunction "1_P$1") (pintype "passive"))
      (node (ref "L603") (pin "P$2") (pinfunction "P$2_P$2") (pintype "bidirectional"))
      (node (ref "R603") (pin "P$1") (pinfunction "1_P$1") (pintype "passive"))
      (node (ref "U603") (pin "1") (pinfunction "VIN_1") (pintype "bidirectional"))
      (node (ref "U603") (pin "4") (pinfunction "EN2_4") (pintype "bidirectional"))
    )
    (net (code "79") (name "Net-(C602-2)") (class "Default")
      (node (ref "C602") (pin "P$2") (pinfunction "2_P$2") (pintype "passive"))
      (node (ref "U603") (pin "6") (pinfunction "CSET_6") (pintype "bidirectional"))
    )
    (net (code "80") (name "Net-(C611-1)") (class "Default")
      (node (ref "C611") (pin "P$1") (pinfunction "1_P$1") (pintype "passive"))
      (node (ref "U101") (pin "49") (pinfunction "VCAP_1_49") (pintype "power_in"))
    )
    (net (code "81") (name "Net-(C613-1)") (class "Default")
      (node (ref "C613") (pin "P$1") (pinfunction "1_P$1") (pintype "passive"))
      (node (ref "U101") (pin "73") (pinfunction "VCAP_2_73") (pintype "power_in"))
    )
    (net (code "82") (name "Net-(C703-1)") (class "Default")
      (node (ref "C703") (pin "P$1") (pinfunction "1_P$1") (pintype "passive"))
      (node (ref "J701") (pin "1") (pinfunction "1_1") (pintype "passive"))
      (node (ref "R703") (pin "P$1") (pinfunction "1_P$1") (pintype "passive"))
      (node (ref "U702") (pin "1") (pinfunction "OUT_1") (pintype "output"))
    )
    (net (code "83") (name "Net-(C704-1)") (class "Default")
      (node (ref "C704") (pin "P$1") (pinfunction "1_P$1") (pintype "passive"))
      (node (ref "R705") (pin "P$1") (pinfunction "1_P$1") (pintype "passive"))
      (node (ref "U702") (pin "6") (pinfunction "VCC_6") (pintype "bidirectional"))
    )
    (net (code "84") (name "Net-(C805-1)") (class "Default")
      (node (ref "C805") (pin "P$1") (pinfunction "1_P$1") (pintype "passive"))
      (node (ref "U801") (pin "5") (pinfunction "PD0/OSC<=_5") (pintype "bidirectional"))
      (node (ref "X801") (pin "3") (pinfunction "3_3") (pintype "bidirectional"))
    )
    (net (code "85") (name "Net-(C806-2)") (class "Default")
      (node (ref "C806") (pin "P$2") (pinfunction "2_P$2") (pintype "passive"))
      (node (ref "U801") (pin "6") (pinfunction "PD1/OSC=>_6") (pintype "bidirectional"))
      (node (ref "X801") (pin "1") (pinfunction "1_1") (pintype "bidirectional"))
    )
    (net (code "86") (name "Net-(C1002-1)") (class "Default")
      (node (ref "C1002") (pin "P$1") (pinfunction "1_P$1") (pintype "passive"))
      (node (ref "U1002") (pin "6") (pinfunction "CSET_6") (pintype "bidirectional"))
    )
    (net (code "87") (name "Net-(C1105-1)") (class "Default")
      (node (ref "C1105") (pin "P$1") (pinfunction "1_P$1") (pintype "passive"))
      (node (ref "U1101") (pin "P$18") (pinfunction "VS1_P$18") (pintype "bidirectional"))
      (node (ref "U1102") (pin "P$1") (pinfunction "S_P$1") (pintype "passive"))
      (node (ref "U1102") (pin "P$3") (pinfunction "S_P$3") (pintype "passive"))
    )
    (net (code "88") (name "Net-(C1106-1)") (class "Default")
      (node (ref "C1106") (pin "P$1") (pinfunction "1_P$1") (pintype "passive"))
      (node (ref "U1101") (pin "P$16") (pinfunction "VS2_P$16") (pintype "bidirectional"))
      (node (ref "U1103") (pin "P$1") (pinfunction "S_P$1") (pintype "passive"))
      (node (ref "U1103") (pin "P$3") (pinfunction "S_P$3") (pintype "passive"))
    )
    (net (code "89") (name "Net-(C1107-1)") (class "Default")
      (node (ref "C1107") (pin "P$1") (pinfunction "1_P$1") (pintype "passive"))
      (node (ref "U1101") (pin "P$14") (pinfunction "VS3_P$14") (pintype "bidirectional"))
      (node (ref "U1104") (pin "P$1") (pinfunction "S_P$1") (pintype "passive"))
      (node (ref "U1104") (pin "P$3") (pinfunction "S_P$3") (pintype "passive"))
    )
    (net (code "90") (name "Net-(C1108-1)") (class "Default")
      (node (ref "C1108") (pin "P$1") (pinfunction "1_P$1") (pintype "passive"))
      (node (ref "R1105") (pin "P$2") (pinfunction "2_P$2") (pintype "passive"))
      (node (ref "R1106") (pin "P$1") (pinfunction "1_P$1") (pintype "passive"))
      (node (ref "U1101") (pin "P$1") (pinfunction "UV1_P$1") (pintype "bidirectional"))
    )
    (net (code "91") (name "Net-(C1109-1)") (class "Default")
      (node (ref "C1109") (pin "P$1") (pinfunction "1_P$1") (pintype "passive"))
      (node (ref "R1109") (pin "P$2") (pinfunction "2_P$2") (pintype "passive"))
      (node (ref "R1110") (pin "P$1") (pinfunction "1_P$1") (pintype "passive"))
      (node (ref "U1101") (pin "P$3") (pinfunction "UV2_P$3") (pintype "bidirectional"))
    )
    (net (code "92") (name "Net-(C1110-1)") (class "Default")
      (node (ref "C1110") (pin "P$1") (pinfunction "1_P$1") (pintype "passive"))
      (node (ref "R1112") (pin "P$2") (pinfunction "2_P$2") (pintype "passive"))
      (node (ref "R1113") (pin "P$1") (pinfunction "1_P$1") (pintype "passive"))
      (node (ref "U1101") (pin "P$5") (pinfunction "UV3_P$5") (pintype "bidirectional"))
    )
    (net (code "93") (name "Net-(D201-PadC)") (class "Default")
      (node (ref "D201") (pin "C") (pinfunction "C_C") (pintype "passive"))
      (node (ref "J201") (pin "1") (pinfunction "1_1") (pintype "passive"))
      (node (ref "L201") (pin "P$2") (pinfunction "P$2_P$2") (pintype "bidirectional"))
    )
    (net (code "94") (name "Net-(D202-PadC)") (class "Default")
      (node (ref "D202") (pin "C") (pinfunction "C_C") (pintype "passive"))
      (node (ref "J202") (pin "1") (pinfunction "1_1") (pintype "passive"))
      (node (ref "L202") (pin "P$2") (pinfunction "P$2_P$2") (pintype "bidirectional"))
    )
    (net (code "95") (name "Net-(D203-PadC)") (class "Default")
      (node (ref "D203") (pin "C") (pinfunction "C_C") (pintype "passive"))
      (node (ref "J203") (pin "1") (pinfunction "1_1") (pintype "passive"))
      (node (ref "J204") (pin "1") (pinfunction "1_1") (pintype "passive"))
      (node (ref "L203") (pin "P$2") (pinfunction "P$2_P$2") (pintype "bidirectional"))
    )
    (net (code "96") (name "Net-(D401-PadC)") (class "Default")
      (node (ref "D401") (pin "C") (pinfunction "C_C") (pintype "passive"))
      (node (ref "J401") (pin "1") (pinfunction "1_1") (pintype "passive"))
      (node (ref "J402") (pin "1") (pinfunction "1_1") (pintype "passive"))
      (node (ref "L401") (pin "P$2") (pinfunction "P$2_P$2") (pintype "bidirectional"))
    )
    (net (code "97") (name "Net-(D402-PadC)") (class "Default")
      (node (ref "D402") (pin "C") (pinfunction "C_C") (pintype "passive"))
      (node (ref "J403") (pin "1") (pinfunction "1_1") (pintype "passive"))
      (node (ref "L402") (pin "P$2") (pinfunction "P$2_P$2") (pintype "bidirectional"))
    )
    (net (code "98") (name "Net-(D403-PadC)") (class "Default")
      (node (ref "D403") (pin "C") (pinfunction "C_C") (pintype "passive"))
      (node (ref "J404") (pin "1") (pinfunction "1_1") (pintype "passive"))
      (node (ref "L404") (pin "P$2") (pinfunction "P$2_P$2") (pintype "bidirectional"))
    )
    (net (code "99") (name "Net-(D404-PadC)") (class "Default")
      (node (ref "D404") (pin "C") (pinfunction "C_C") (pintype "passive"))
      (node (ref "J405") (pin "1") (pinfunction "1_1") (pintype "passive"))
      (node (ref "L403") (pin "P$2") (pinfunction "P$2_P$2") (pintype "bidirectional"))
    )
    (net (code "100") (name "Net-(D904-C)") (class "Default")
      (node (ref "D903") (pin "C") (pinfunction "C_C") (pintype "passive"))
      (node (ref "D904") (pin "CATHODE") (pinfunction "C_CATHODE") (pintype "passive"))
      (node (ref "L901") (pin "P$1") (pinfunction "P$1_P$1") (pintype "bidirectional"))
    )
    (net (code "101") (name "Net-(D1001-A1)") (class "Default")
      (node (ref "D1001") (pin "1") (pinfunction "A1_1") (pintype "passive"))
      (node (ref "F1001") (pin "2") (pinfunction "2_2") (pintype "bidirectional"))
    )
    (net (code "102") (name "Net-(D1001-A2)") (class "Default")
      (node (ref "D1001") (pin "2") (pinfunction "A2_2") (pintype "passive"))
      (node (ref "U1001") (pin "8") (pinfunction "OUT_8") (pintype "bidirectional"))
    )
    (net (code "103") (name "Net-(J301-2)") (class "Default")
      (node (ref "J301") (pin "D-") (pinfunction "2_D-") (pintype "bidirectional"))
      (node (ref "J302") (pin "3") (pinfunction "3_3") (pintype "passive"))
      (node (ref "U302") (pin "1") (pinfunction "D1I_1") (pintype "bidirectional"))
    )
    (net (code "104") (name "Net-(J301-3)") (class "Default")
      (node (ref "J301") (pin "D+") (pinfunction "3_D+") (pintype "bidirectional"))
      (node (ref "J302") (pin "2") (pinfunction "2_2") (pintype "passive"))
      (node (ref "U302") (pin "3") (pinfunction "D2I_3") (pintype "bidirectional"))
    )
    (net (code "105") (name "Net-(J901A-S)") (class "Default")
      (node (ref "J901") (pin "1") (pinfunction "S_1") (pintype "passive"))
      (node (ref "R909") (pin "P$2") (pinfunction "2_P$2") (pintype "passive"))
    )
    (net (code "106") (name "Net-(J901B-S)") (class "Default")
      (node (ref "J901") (pin "10") (pinfunction "S_10") (pintype "passive"))
      (node (ref "R914") (pin "P$2") (pinfunction "2_P$2") (pintype "passive"))
    )
    (net (code "107") (name "Net-(J901C-S)") (class "Default")
      (node (ref "J901") (pin "13") (pinfunction "S_13") (pintype "passive"))
      (node (ref "R906") (pin "P$2") (pinfunction "2_P$2") (pintype "passive"))
    )
    (net (code "108") (name "Net-(J901D-S)") (class "Default")
      (node (ref "J901") (pin "16") (pinfunction "S_16") (pintype "passive"))
      (node (ref "R915") (pin "P$2") (pinfunction "2_P$2") (pintype "passive"))
    )
    (net (code "109") (name "Net-(J901E-S)") (class "Default")
      (node (ref "J901") (pin "19") (pinfunction "S_19") (pintype "passive"))
      (node (ref "R907") (pin "P$2") (pinfunction "2_P$2") (pintype "passive"))
    )
    (net (code "110") (name "Net-(J901G-S)") (class "Default")
      (node (ref "J901") (pin "22") (pinfunction "S_22") (pintype "passive"))
      (node (ref "R916") (pin "P$2") (pinfunction "2_P$2") (pintype "passive"))
    )
    (net (code "111") (name "Net-(J901H-S)") (class "Default")
      (node (ref "J901") (pin "25") (pinfunction "S_25") (pintype "passive"))
      (node (ref "R908") (pin "P$2") (pinfunction "2_P$2") (pintype "passive"))
    )
    (net (code "112") (name "Net-(J901I-S)") (class "Default")
      (node (ref "J901") (pin "28") (pinfunction "S_28") (pintype "passive"))
      (node (ref "R917") (pin "P$2") (pinfunction "2_P$2") (pintype "passive"))
    )
    (net (code "113") (name "Net-(J901J-S)") (class "Default")
      (node (ref "J901") (pin "31") (pinfunction "S_31") (pintype "passive"))
      (node (ref "R902") (pin "P$2") (pinfunction "2_P$2") (pintype "passive"))
    )
    (net (code "114") (name "Net-(J901K-S)") (class "Default")
      (node (ref "J901") (pin "34") (pinfunction "S_34") (pintype "passive"))
      (node (ref "R911") (pin "P$2") (pinfunction "2_P$2") (pintype "passive"))
    )
    (net (code "115") (name "Net-(J901L-S)") (class "Default")
      (node (ref "J901") (pin "37") (pinfunction "S_37") (pintype "passive"))
      (node (ref "R903") (pin "P$2") (pinfunction "2_P$2") (pintype "passive"))
    )
    (net (code "116") (name "Net-(J901M-S)") (class "Default")
      (node (ref "J901") (pin "4") (pinfunction "S_4") (pintype "passive"))
      (node (ref "R910") (pin "P$2") (pinfunction "2_P$2") (pintype "passive"))
    )
    (net (code "117") (name "Net-(J901N-S)") (class "Default")
      (node (ref "J901") (pin "40") (pinfunction "S_40") (pintype "passive"))
      (node (ref "R912") (pin "P$2") (pinfunction "2_P$2") (pintype "passive"))
    )
    (net (code "118") (name "Net-(J901O-S)") (class "Default")
      (node (ref "J901") (pin "43") (pinfunction "S_43") (pintype "passive"))
      (node (ref "R904") (pin "P$2") (pinfunction "2_P$2") (pintype "passive"))
    )
    (net (code "119") (name "Net-(J901P-S)") (class "Default")
      (node (ref "J901") (pin "46") (pinfunction "S_46") (pintype "passive"))
      (node (ref "R913") (pin "P$2") (pinfunction "2_P$2") (pintype "passive"))
    )
    (net (code "120") (name "Net-(J901Q-S)") (class "Default")
      (node (ref "J901") (pin "7") (pinfunction "S_7") (pintype "passive"))
      (node (ref "R905") (pin "P$2") (pinfunction "2_P$2") (pintype "passive"))
    )
    (net (code "121") (name "Net-(L701-2)") (class "Default")
      (node (ref "L701") (pin "P$2") (pinfunction "2_P$2") (pintype "passive"))
      (node (ref "U702") (pin "5") (pinfunction "SW_5") (pintype "passive"))
    )
    (net (code "122") (name "Net-(Q601-PadC)") (class "Default")
      (node (ref "Q601") (pin "C") (pinfunction "C_C") (pintype "passive"))
      (node (ref "R621") (pin "2") (pinfunction "2_2") (pintype "passive"))
    )
    (net (code "123") (name "Net-(R101-1)") (class "Default")
      (node (ref "R101") (pin "P$1") (pinfunction "1_P$1") (pintype "passive"))
      (node (ref "U101") (pin "69") (pinfunction "PA10_69") (pintype "bidirectional"))
    )
    (net (code "124") (name "Net-(R102-1)") (class "Default")
      (node (ref "R102") (pin "P$1") (pinfunction "1_P$1") (pintype "passive"))
      (node (ref "U101") (pin "37") (pinfunction "PB2_37") (pintype "bidirectional"))
    )
    (net (code "125") (name "Net-(R201-1)") (class "Default")
      (node (ref "R201") (pin "P$1") (pinfunction "1_P$1") (pintype "passive"))
      (node (ref "U201") (pin "20") (pinfunction "B1_20") (pintype "bidirectional"))
    )
    (net (code "126") (name "Net-(R202-1)") (class "Default")
      (node (ref "R202") (pin "P$1") (pinfunction "1_P$1") (pintype "passive"))
      (node (ref "U201") (pin "17") (pinfunction "B3_17") (pintype "bidirectional"))
    )
    (net (code "127") (name "Net-(R203-1)") (class "Default")
      (node (ref "R203") (pin "P$1") (pinfunction "1_P$1") (pintype "passive"))
      (node (ref "U201") (pin "15") (pinfunction "B5_15") (pintype "bidirectional"))
    )
    (net (code "128") (name "Net-(R204-1)") (class "Default")
      (node (ref "R204") (pin "P$1") (pinfunction "1_P$1") (pintype "passive"))
      (node (ref "U201") (pin "13") (pinfunction "B7_13") (pintype "bidirectional"))
    )
    (net (code "129") (name "Net-(R205-1)") (class "Default")
      (node (ref "R205") (pin "P$1") (pinfunction "1_P$1") (pintype "passive"))
      (node (ref "U202") (pin "17") (pinfunction "B3_17") (pintype "bidirectional"))
    )
    (net (code "130") (name "Net-(R206-1)") (class "Default")
      (node (ref "R206") (pin "P$1") (pinfunction "1_P$1") (pintype "passive"))
      (node (ref "U202") (pin "15") (pinfunction "B5_15") (pintype "bidirectional"))
    )
    (net (code "131") (name "Net-(R207-1)") (class "Default")
      (node (ref "R207") (pin "P$1") (pinfunction "1_P$1") (pintype "passive"))
      (node (ref "U202") (pin "13") (pinfunction "B7_13") (pintype "bidirectional"))
    )
    (net (code "132") (name "Net-(R208-1)") (class "Default")
      (node (ref "R208") (pin "P$1") (pinfunction "1_P$1") (pintype "passive"))
      (node (ref "U201") (pin "18") (pinfunction "B2_18") (pintype "bidirectional"))
    )
    (net (code "133") (name "Net-(R209-1)") (class "Default")
      (node (ref "R209") (pin "P$1") (pinfunction "1_P$1") (pintype "passive"))
      (node (ref "U201") (pin "16") (pinfunction "B4_16") (pintype "bidirectional"))
    )
    (net (code "134") (name "Net-(R210-1)") (class "Default")
      (node (ref "R210") (pin "P$1") (pinfunction "1_P$1") (pintype "passive"))
      (node (ref "U201") (pin "14") (pinfunction "B6_14") (pintype "bidirectional"))
    )
    (net (code "135") (name "Net-(R211-1)") (class "Default")
      (node (ref "R211") (pin "P$1") (pinfunction "1_P$1") (pintype "passive"))
      (node (ref "U201") (pin "12") (pinfunction "B8_12") (pintype "bidirectional"))
    )
    (net (code "136") (name "Net-(R212-1)") (class "Default")
      (node (ref "R212") (pin "P$1") (pinfunction "1_P$1") (pintype "passive"))
      (node (ref "U202") (pin "16") (pinfunction "B4_16") (pintype "bidirectional"))
    )
    (net (code "137") (name "Net-(R213-1)") (class "Default")
      (node (ref "R213") (pin "P$1") (pinfunction "1_P$1") (pintype "passive"))
      (node (ref "U202") (pin "14") (pinfunction "B6_14") (pintype "bidirectional"))
    )
    (net (code "138") (name "Net-(R214-1)") (class "Default")
      (node (ref "R214") (pin "P$1") (pinfunction "1_P$1") (pintype "passive"))
      (node (ref "U202") (pin "12") (pinfunction "B8_12") (pintype "bidirectional"))
    )
    (net (code "139") (name "Net-(R215-2)") (class "Default")
      (node (ref "J203") (pin "4") (pinfunction "4_4") (pintype "passive"))
      (node (ref "R215") (pin "P$2") (pinfunction "2_P$2") (pintype "passive"))
    )
    (net (code "140") (name "Net-(R216-2)") (class "Default")
      (node (ref "J203") (pin "5") (pinfunction "5_5") (pintype "passive"))
      (node (ref "R216") (pin "P$2") (pinfunction "2_P$2") (pintype "passive"))
    )
    (net (code "141") (name "Net-(R404-2)") (class "Default")
      (node (ref "J401") (pin "2") (pinfunction "2_2") (pintype "passive"))
      (node (ref "R404") (pin "P$2") (pinfunction "2_P$2") (pintype "passive"))
    )
    (net (code "142") (name "Net-(R405-2)") (class "Default")
      (node (ref "J401") (pin "3") (pinfunction "3_3") (pintype "passive"))
      (node (ref "R405") (pin "P$2") (pinfunction "2_P$2") (pintype "passive"))
    )
    (net (code "143") (name "Net-(R407-2)") (class "Default")
      (node (ref "J404") (pin "2") (pinfunction "2_2") (pintype "passive"))
      (node (ref "R407") (pin "P$2") (pinfunction "2_P$2") (pintype "passive"))
    )
    (net (code "144") (name "Net-(R408-2)") (class "Default")
      (node (ref "J404") (pin "4") (pinfunction "4_4") (pintype "passive"))
      (node (ref "R408") (pin "P$2") (pinfunction "2_P$2") (pintype "passive"))
    )
    (net (code "145") (name "Net-(R608-2)") (class "Default")
      (node (ref "D602") (pin "C") (pinfunction "C_C") (pintype "passive"))
      (node (ref "R608") (pin "P$2") (pinfunction "2_P$2") (pintype "passive"))
    )
    (net (code "146") (name "Net-(R616-1)") (class "Default")
      (node (ref "R616") (pin "P$1") (pinfunction "1_P$1") (pintype "passive"))
      (node (ref "U602") (pin "7") (pinfunction "ILIM_7") (pintype "bidirectional"))
    )
    (net (code "147") (name "Net-(R617-1)") (class "Default")
      (node (ref "R617") (pin "P$1") (pinfunction "1_P$1") (pintype "passive"))
      (node (ref "U601") (pin "7") (pinfunction "ILIM_7") (pintype "bidirectional"))
    )
    (net (code "148") (name "Net-(R620-1)") (class "Default")
      (node (ref "Q601") (pin "B") (pinfunction "B_B") (pintype "passive"))
      (node (ref "R620") (pin "P$1") (pinfunction "1_P$1") (pintype "passive"))
    )
    (net (code "149") (name "Net-(R701-1)") (class "Default")
      (node (ref "R701") (pin "P$1") (pinfunction "1_P$1") (pintype "passive"))
      (node (ref "U702") (pin "7") (pinfunction "+IN_7") (pintype "input"))
    )
    (net (code "150") (name "Net-(R702-1)") (class "Default")
      (node (ref "R702") (pin "P$1") (pinfunction "1_P$1") (pintype "passive"))
      (node (ref "R703") (pin "P$2") (pinfunction "2_P$2") (pintype "passive"))
      (node (ref "U702") (pin "8") (pinfunction "-IN_8") (pintype "input"))
    )
    (net (code "151") (name "Net-(R704-2)") (class "Default")
      (node (ref "R704") (pin "P$2") (pinfunction "2_P$2") (pintype "passive"))
      (node (ref "U701") (pin "6") (pinfunction "REXT_6") (pintype "bidirectional"))
    )
    (net (code "152") (name "Net-(R705-2)") (class "Default")
      (node (ref "R705") (pin "P$2") (pinfunction "2_P$2") (pintype "passive"))
      (node (ref "R706") (pin "P$1") (pinfunction "1_P$1") (pintype "passive"))
      (node (ref "U702") (pin "2") (pinfunction "FB_2") (pintype "bidirectional"))
    )
    (net (code "153") (name "Net-(R707-2)") (class "Default")
      (node (ref "R707") (pin "P$2") (pinfunction "2_P$2") (pintype "passive"))
      (node (ref "R735") (pin "P$1") (pinfunction "1_P$1") (pintype "passive"))
    )
    (net (code "154") (name "Net-(R708-2)") (class "Default")
      (node (ref "LED702") (pin "C") (pinfunction "C_C") (pintype "passive"))
      (node (ref "R708") (pin "P$2") (pinfunction "2_P$2") (pintype "passive"))
    )
    (net (code "155") (name "Net-(R709-2)") (class "Default")
      (node (ref "R709") (pin "P$2") (pinfunction "2_P$2") (pintype "passive"))
      (node (ref "R736") (pin "P$1") (pinfunction "1_P$1") (pintype "passive"))
    )
    (net (code "156") (name "Net-(R710-1)") (class "Default")
      (node (ref "J702") (pin "2") (pinfunction "2_2") (pintype "passive"))
      (node (ref "R710") (pin "P$1") (pinfunction "1_P$1") (pintype "passive"))
    )
    (net (code "157") (name "Net-(R711-2)") (class "Default")
      (node (ref "LED704") (pin "C") (pinfunction "C_C") (pintype "passive"))
      (node (ref "R711") (pin "P$2") (pinfunction "2_P$2") (pintype "passive"))
    )
    (net (code "158") (name "Net-(R712-2)") (class "Default")
      (node (ref "LED705") (pin "C") (pinfunction "C_C") (pintype "passive"))
      (node (ref "R712") (pin "P$2") (pinfunction "2_P$2") (pintype "passive"))
    )
    (net (code "159") (name "Net-(R735-2)") (class "Default")
      (node (ref "LED701") (pin "C") (pinfunction "C_C") (pintype "passive"))
      (node (ref "R735") (pin "P$2") (pinfunction "2_P$2") (pintype "passive"))
    )
    (net (code "160") (name "Net-(R736-2)") (class "Default")
      (node (ref "LED703") (pin "C") (pinfunction "C_C") (pintype "passive"))
      (node (ref "R736") (pin "P$2") (pinfunction "2_P$2") (pintype "passive"))
    )
    (net (code "161") (name "Net-(R802-1)") (class "Default")
      (node (ref "R802") (pin "P$1") (pinfunction "1_P$1") (pintype "passive"))
      (node (ref "U801") (pin "20") (pinfunction "PB2_20") (pintype "bidirectional"))
    )
    (net (code "162") (name "Net-(R803-1)") (class "Default")
      (node (ref "R803") (pin "P$1") (pinfunction "1_P$1") (pintype "passive"))
      (node (ref "U801") (pin "12") (pinfunction "PA2_12") (pintype "bidirectional"))
    )
    (net (code "163") (name "Net-(R804-1)") (class "Default")
      (node (ref "R804") (pin "P$1") (pinfunction "1_P$1") (pintype "passive"))
      (node (ref "U801") (pin "13") (pinfunction "PA3_13") (pintype "bidirectional"))
    )
    (net (code "164") (name "Net-(R901-2)") (class "Default")
      (node (ref "D902") (pin "C") (pinfunction "C_C") (pintype "passive"))
      (node (ref "R901") (pin "P$2") (pinfunction "2_P$2") (pintype "passive"))
      (node (ref "R910") (pin "P$1") (pinfunction "1_P$1") (pintype "passive"))
      (node (ref "U903") (pin "3") (pinfunction "2Y_3") (pintype "bidirectional"))
    )
    (net (code "165") (name "Net-(R902-1)") (class "Default")
      (node (ref "R902") (pin "P$1") (pinfunction "1_P$1") (pintype "passive"))
      (node (ref "U901") (pin "20") (pinfunction "B1_20") (pintype "bidirectional"))
    )
    (net (code "166") (name "Net-(R903-1)") (class "Default")
      (node (ref "R903") (pin "P$1") (pinfunction "1_P$1") (pintype "passive"))
      (node (ref "U901") (pin "17") (pinfunction "B3_17") (pintype "bidirectional"))
    )
    (net (code "167") (name "Net-(R904-1)") (class "Default")
      (node (ref "R904") (pin "P$1") (pinfunction "1_P$1") (pintype "passive"))
      (node (ref "U901") (pin "15") (pinfunction "B5_15") (pintype "bidirectional"))
    )
    (net (code "168") (name "Net-(R905-1)") (class "Default")
      (node (ref "R905") (pin "P$1") (pinfunction "1_P$1") (pintype "passive"))
      (node (ref "U902") (pin "20") (pinfunction "B1_20") (pintype "bidirectional"))
    )
    (net (code "169") (name "Net-(R906-1)") (class "Default")
      (node (ref "R906") (pin "P$1") (pinfunction "1_P$1") (pintype "passive"))
      (node (ref "U902") (pin "17") (pinfunction "B3_17") (pintype "bidirectional"))
    )
    (net (code "170") (name "Net-(R907-1)") (class "Default")
      (node (ref "R907") (pin "P$1") (pinfunction "1_P$1") (pintype "passive"))
      (node (ref "U902") (pin "15") (pinfunction "B5_15") (pintype "bidirectional"))
    )
    (net (code "171") (name "Net-(R908-1)") (class "Default")
      (node (ref "R908") (pin "P$1") (pinfunction "1_P$1") (pintype "passive"))
      (node (ref "U902") (pin "13") (pinfunction "B7_13") (pintype "bidirectional"))
    )
    (net (code "172") (name "Net-(R911-1)") (class "Default")
      (node (ref "R911") (pin "P$1") (pinfunction "1_P$1") (pintype "passive"))
      (node (ref "U901") (pin "18") (pinfunction "B2_18") (pintype "bidirectional"))
    )
    (net (code "173") (name "Net-(R912-1)") (class "Default")
      (node (ref "R912") (pin "P$1") (pinfunction "1_P$1") (pintype "passive"))
      (node (ref "U901") (pin "16") (pinfunction "B4_16") (pintype "bidirectional"))
    )
    (net (code "174") (name "Net-(R913-1)") (class "Default")
      (node (ref "R913") (pin "P$1") (pinfunction "1_P$1") (pintype "passive"))
      (node (ref "U901") (pin "14") (pinfunction "B6_14") (pintype "bidirectional"))
    )
    (net (code "175") (name "Net-(R914-1)") (class "Default")
      (node (ref "R914") (pin "P$1") (pinfunction "1_P$1") (pintype "passive"))
      (node (ref "U902") (pin "18") (pinfunction "B2_18") (pintype "bidirectional"))
    )
    (net (code "176") (name "Net-(R915-1)") (class "Default")
      (node (ref "R915") (pin "P$1") (pinfunction "1_P$1") (pintype "passive"))
      (node (ref "U902") (pin "16") (pinfunction "B4_16") (pintype "bidirectional"))
    )
    (net (code "177") (name "Net-(R916-1)") (class "Default")
      (node (ref "R916") (pin "P$1") (pinfunction "1_P$1") (pintype "passive"))
      (node (ref "U902") (pin "14") (pinfunction "B6_14") (pintype "bidirectional"))
    )
    (net (code "178") (name "Net-(R917-1)") (class "Default")
      (node (ref "R917") (pin "P$1") (pinfunction "1_P$1") (pintype "passive"))
      (node (ref "U902") (pin "12") (pinfunction "B8_12") (pintype "bidirectional"))
    )
    (net (code "179") (name "Net-(R918-2)") (class "Default")
      (node (ref "R918") (pin "P$2") (pinfunction "2_P$2") (pintype "passive"))
      (node (ref "R922") (pin "P$1") (pinfunction "1_P$1") (pintype "passive"))
    )
    (net (code "180") (name "Net-(R1001-2)") (class "Default")
      (node (ref "R1001") (pin "P$2") (pinfunction "2_P$2") (pintype "passive"))
      (node (ref "U1001") (pin "7") (pinfunction "ILIM_7") (pintype "bidirectional"))
    )
    (net (code "181") (name "Net-(R1101-2)") (class "Default")
      (node (ref "L1101") (pin "P$2") (pinfunction "P$2_P$2") (pintype "bidirectional"))
      (node (ref "R1101") (pin "P$2") (pinfunction "2_P$2") (pintype "passive"))
    )
    (net (code "182") (name "Net-(R1102-2)") (class "Default")
      (node (ref "L1102") (pin "P$2") (pinfunction "P$2_P$2") (pintype "bidirectional"))
      (node (ref "R1102") (pin "P$2") (pinfunction "2_P$2") (pintype "passive"))
    )
    (net (code "183") (name "Net-(R1103-1)") (class "Default")
      (node (ref "J601") (pin "4") (pinfunction "4_4") (pintype "passive"))
      (node (ref "L1102") (pin "P$1") (pinfunction "P$1_P$1") (pintype "bidirectional"))
      (node (ref "R1103") (pin "P$1") (pinfunction "1_P$1") (pintype "passive"))
    )
    (net (code "184") (name "Net-(R1104-1)") (class "Default")
      (node (ref "J601") (pin "3") (pinfunction "3_3") (pintype "passive"))
      (node (ref "L1101") (pin "P$1") (pinfunction "P$1_P$1") (pintype "bidirectional"))
      (node (ref "R1104") (pin "P$1") (pinfunction "1_P$1") (pintype "passive"))
    )
    (net (code "185") (name "Net-(R1106-2)") (class "Default")
      (node (ref "R1106") (pin "P$2") (pinfunction "2_P$2") (pintype "passive"))
      (node (ref "R1107") (pin "P$1") (pinfunction "1_P$1") (pintype "passive"))
      (node (ref "U1101") (pin "P$2") (pinfunction "OV1_P$2") (pintype "bidirectional"))
    )
    (net (code "186") (name "Net-(R1110-2)") (class "Default")
      (node (ref "R1110") (pin "P$2") (pinfunction "2_P$2") (pintype "passive"))
      (node (ref "R1111") (pin "P$1") (pinfunction "1_P$1") (pintype "passive"))
      (node (ref "U1101") (pin "P$4") (pinfunction "OV2_P$4") (pintype "bidirectional"))
    )
    (net (code "187") (name "Net-(R1113-2)") (class "Default")
      (node (ref "R1113") (pin "P$2") (pinfunction "2_P$2") (pintype "passive"))
      (node (ref "R1114") (pin "P$1") (pinfunction "1_P$1") (pintype "passive"))
      (node (ref "U1101") (pin "P$6") (pinfunction "OV3_P$6") (pintype "bidirectional"))
    )
    (net (code "188") (name "Net-(R1115-2)") (class "Default")
      (node (ref "R1115") (pin "P$2") (pinfunction "2_P$2") (pintype "passive"))
      (node (ref "U1101") (pin "P$24") (pinfunction "HYS_P$24") (pintype "bidirectional"))
    )
    (net (code "189") (name "Net-(U701-OUT0)") (class "Default")
      (node (ref "U701") (pin "9") (pinfunction "OUT0_9") (pintype "open_collector"))
      (node (ref "U703") (pin "C1") (pinfunction "C_C1") (pintype "passive"))
    )
    (net (code "190") (name "Net-(U701-OUT1)") (class "Default")
      (node (ref "U701") (pin "8") (pinfunction "OUT1_8") (pintype "open_collector"))
      (node (ref "U703") (pin "C2") (pinfunction "C_C2") (pintype "passive"))
    )
    (net (code "191") (name "Net-(U701-OUT2)") (class "Default")
      (node (ref "U701") (pin "7") (pinfunction "OUT2_7") (pintype "open_collector"))
      (node (ref "U703") (pin "C3") (pinfunction "C_C3") (pintype "passive"))
    )
    (net (code "192") (name "Net-(U1101-G1)") (class "Default")
      (node (ref "U1101") (pin "P$17") (pinfunction "G1_P$17") (pintype "bidirectional"))
      (node (ref "U1102") (pin "P$2") (pinfunction "G_P$2") (pintype "passive"))
      (node (ref "U1102") (pin "P$4") (pinfunction "G_P$4") (pintype "passive"))
    )
    (net (code "193") (name "Net-(U1101-G2)") (class "Default")
      (node (ref "U1101") (pin "P$15") (pinfunction "G2_P$15") (pintype "bidirectional"))
      (node (ref "U1103") (pin "P$2") (pinfunction "G_P$2") (pintype "passive"))
      (node (ref "U1103") (pin "P$4") (pinfunction "G_P$4") (pintype "passive"))
    )
    (net (code "194") (name "Net-(U1101-G3)") (class "Default")
      (node (ref "U1101") (pin "P$13") (pinfunction "G3_P$13") (pintype "bidirectional"))
      (node (ref "U1104") (pin "P$2") (pinfunction "G_P$2") (pintype "passive"))
      (node (ref "U1104") (pin "P$4") (pinfunction "G_P$4") (pintype "passive"))
    )
    (net (code "195") (name "OTG_FS_DM") (class "Default")
      (node (ref "U101") (pin "70") (pinfunction "PA11_70") (pintype "bidirectional"))
      (node (ref "U302") (pin "6") (pinfunction "D1O_6") (pintype "bidirectional"))
    )
    (net (code "196") (name "OTG_FS_DP") (class "Default")
      (node (ref "U101") (pin "71") (pinfunction "PA12_71") (pintype "bidirectional"))
      (node (ref "U302") (pin "4") (pinfunction "D2O_4") (pintype "bidirectional"))
    )
    (net (code "197") (name "PPM_INPUT") (class "Default")
      (node (ref "D901") (pin "C") (pinfunction "C_C") (pintype "passive"))
      (node (ref "R909") (pin "P$1") (pinfunction "1_P$1") (pintype "passive"))
      (node (ref "U801") (pin "29") (pinfunction "PA8_29") (pintype "bidirectional"))
      (node (ref "U903") (pin "2") (pinfunction "1A_2") (pintype "bidirectional"))
    )
    (net (code "198") (name "PRESSURE_SENS") (class "Default")
      (node (ref "C401") (pin "P$1") (pinfunction "1_P$1") (pintype "passive"))
      (node (ref "R403") (pin "P$2") (pinfunction "2_P$2") (pintype "passive"))
      (node (ref "R406") (pin "P$1") (pinfunction "1_P$1") (pintype "passive"))
      (node (ref "U101") (pin "34") (pinfunction "PC5_34") (pintype "bidirectional"))
    )
    (net (code "199") (name "PRESSURE_SENS_IN") (class "Default")
      (node (ref "ADC_PR") (pin "P$1") (pinfunction "P$1_P$1") (pintype "passive"))
      (node (ref "J402") (pin "2") (pinfunction "2_2") (pintype "passive"))
      (node (ref "R406") (pin "P$2") (pinfunction "2_P$2") (pintype "passive"))
    )
    (net (code "200") (name "RSSI_IN") (class "Default")
      (node (ref "R901") (pin "P$1") (pinfunction "1_P$1") (pintype "passive"))
      (node (ref "U801") (pin "15") (pinfunction "PA5_15") (pintype "bidirectional"))
      (node (ref "U801") (pin "33") (pinfunction "PA12_33") (pintype "bidirectional"))
    )
    (net (code "201") (name "SAFETY") (class "Default")
      (node (ref "J702") (pin "3") (pinfunction "3_3") (pintype "passive"))
      (node (ref "R713") (pin "P$1") (pinfunction "1_P$1") (pintype "passive"))
      (node (ref "U801") (pin "41") (pinfunction "PB5_41") (pintype "bidirectional"))
    )
    (net (code "202") (name "SBUS_INPUT") (class "Default")
      (node (ref "U801") (pin "22") (pinfunction "PB11_22") (pintype "bidirectional"))
      (node (ref "U903") (pin "6") (pinfunction "1Y_6") (pintype "bidirectional"))
    )
    (net (code "203") (name "SBUS_OUTPUT") (class "Default")
      (node (ref "U801") (pin "21") (pinfunction "PB10_21") (pintype "bidirectional"))
      (node (ref "U903") (pin "5") (pinfunction "2A_5") (pintype "bidirectional"))
    )
    (net (code "204") (name "SDIO_CK") (class "Default")
      (node (ref "U101") (pin "80") (pinfunction "PC12_80") (pintype "bidirectional"))
      (node (ref "U301") (pin "5") (pinfunction "CLK_5") (pintype "bidirectional"))
    )
    (net (code "205") (name "SDIO_CMD") (class "Default")
      (node (ref "R303") (pin "P$1") (pinfunction "1_P$1") (pintype "passive"))
      (node (ref "U101") (pin "83") (pinfunction "PD2_83") (pintype "bidirectional"))
      (node (ref "U301") (pin "3") (pinfunction "CMD_3") (pintype "bidirectional"))
    )
    (net (code "206") (name "SDIO_D0") (class "Default")
      (node (ref "R304") (pin "P$1") (pinfunction "1_P$1") (pintype "passive"))
      (node (ref "U101") (pin "65") (pinfunction "PC8_65") (pintype "bidirectional"))
      (node (ref "U301") (pin "7") (pinfunction "D0_7") (pintype "bidirectional"))
    )
    (net (code "207") (name "SDIO_D1") (class "Default")
      (node (ref "R305") (pin "P$1") (pinfunction "1_P$1") (pintype "passive"))
      (node (ref "U101") (pin "66") (pinfunction "PC9_66") (pintype "bidirectional"))
      (node (ref "U301") (pin "8") (pinfunction "D1_8") (pintype "bidirectional"))
    )
    (net (code "208") (name "SDIO_D2") (class "Default")
      (node (ref "R301") (pin "P$1") (pinfunction "1_P$1") (pintype "passive"))
      (node (ref "U101") (pin "78") (pinfunction "PC10_78") (pintype "bidirectional"))
      (node (ref "U301") (pin "1") (pinfunction "D2_1") (pintype "bidirectional"))
    )
    (net (code "209") (name "SDIO_D3") (class "Default")
      (node (ref "R302") (pin "P$1") (pinfunction "1_P$1") (pintype "passive"))
      (node (ref "U101") (pin "79") (pinfunction "PC11_79") (pintype "bidirectional"))
      (node (ref "U301") (pin "2") (pinfunction "D3_2") (pintype "bidirectional"))
    )
    (net (code "210") (name "SERIAL1_CTS") (class "Default")
      (node (ref "J201") (pin "4") (pinfunction "4_4") (pintype "passive"))
      (node (ref "R211") (pin "P$2") (pinfunction "2_P$2") (pintype "passive"))
    )
    (net (code "211") (name "SERIAL1_RTS") (class "Default")
      (node (ref "J201") (pin "5") (pinfunction "5_5") (pintype "passive"))
      (node (ref "R204") (pin "P$2") (pinfunction "2_P$2") (pintype "passive"))
    )
    (net (code "212") (name "SERIAL1_RX") (class "Default")
      (node (ref "J201") (pin "3") (pinfunction "3_3") (pintype "passive"))
      (node (ref "R203") (pin "P$2") (pinfunction "2_P$2") (pintype "passive"))
      (node (ref "S1RX") (pin "P$1") (pinfunction "P$1_P$1") (pintype "passive"))
    )
    (net (code "213") (name "SERIAL1_TX") (class "Default")
      (node (ref "J201") (pin "2") (pinfunction "2_2") (pintype "passive"))
      (node (ref "R210") (pin "P$2") (pinfunction "2_P$2") (pintype "passive"))
      (node (ref "S1TX") (pin "P$1") (pinfunction "P$1_P$1") (pintype "passive"))
    )
    (net (code "214") (name "SERIAL2_CTS") (class "Default")
      (node (ref "J202") (pin "4") (pinfunction "4_4") (pintype "passive"))
      (node (ref "R208") (pin "P$2") (pinfunction "2_P$2") (pintype "passive"))
    )
    (net (code "215") (name "SERIAL2_RTS") (class "Default")
      (node (ref "J202") (pin "5") (pinfunction "5_5") (pintype "passive"))
      (node (ref "R201") (pin "P$2") (pinfunction "2_P$2") (pintype "passive"))
    )
    (net (code "216") (name "SERIAL2_RX") (class "Default")
      (node (ref "J202") (pin "3") (pinfunction "3_3") (pintype "passive"))
      (node (ref "R202") (pin "P$2") (pinfunction "2_P$2") (pintype "passive"))
      (node (ref "S2RX") (pin "P$1") (pinfunction "P$1_P$1") (pintype "passive"))
    )
    (net (code "217") (name "SERIAL2_TX") (class "Default")
      (node (ref "J202") (pin "2") (pinfunction "2_2") (pintype "passive"))
      (node (ref "R209") (pin "P$2") (pinfunction "2_P$2") (pintype "passive"))
      (node (ref "S2TX") (pin "P$1") (pinfunction "P$1_P$1") (pintype "passive"))
    )
    (net (code "218") (name "SERIAL3_RX") (class "Default")
      (node (ref "J203") (pin "3") (pinfunction "3_3") (pintype "passive"))
      (node (ref "R207") (pin "P$2") (pinfunction "2_P$2") (pintype "passive"))
      (node (ref "S3RX") (pin "P$1") (pinfunction "P$1_P$1") (pintype "passive"))
    )
    (net (code "219") (name "SERIAL3_TX") (class "Default")
      (node (ref "J203") (pin "2") (pinfunction "2_2") (pintype "passive"))
      (node (ref "R214") (pin "P$2") (pinfunction "2_P$2") (pintype "passive"))
      (node (ref "S3TX") (pin "P$1") (pinfunction "P$1_P$1") (pintype "passive"))
    )
    (net (code "220") (name "SERIAL4_RX") (class "Default")
      (node (ref "J204") (pin "3") (pinfunction "3_3") (pintype "passive"))
      (node (ref "R206") (pin "P$2") (pinfunction "2_P$2") (pintype "passive"))
      (node (ref "S4RX") (pin "P$1") (pinfunction "P$1_P$1") (pintype "passive"))
    )
    (net (code "221") (name "SERIAL4_TX") (class "Default")
      (node (ref "J204") (pin "2") (pinfunction "2_2") (pintype "passive"))
      (node (ref "R213") (pin "P$2") (pinfunction "2_P$2") (pintype "passive"))
      (node (ref "S4TX") (pin "P$1") (pinfunction "P$1_P$1") (pintype "passive"))
    )
    (net (code "222") (name "SERIAL5_RX") (class "Default")
      (node (ref "J204") (pin "5") (pinfunction "5_5") (pintype "passive"))
      (node (ref "R205") (pin "P$2") (pinfunction "2_P$2") (pintype "passive"))
      (node (ref "S5_RX") (pin "P$1") (pinfunction "P$1_P$1") (pintype "passive"))
    )
    (net (code "223") (name "SERIAL5_TX") (class "Default")
      (node (ref "J204") (pin "4") (pinfunction "4_4") (pintype "passive"))
      (node (ref "R212") (pin "P$2") (pinfunction "2_P$2") (pintype "passive"))
      (node (ref "S5_TX") (pin "P$1") (pinfunction "P$1_P$1") (pintype "passive"))
    )
    (net (code "224") (name "SERIAL_FMU_TO_IO") (class "Default")
      (node (ref "R804") (pin "P$2") (pinfunction "2_P$2") (pintype "passive"))
      (node (ref "U101") (pin "63") (pinfunction "PC6_63") (pintype "bidirectional"))
    )
    (net (code "225") (name "SERIAL_IO_TO_FMU") (class "Default")
      (node (ref "R803") (pin "P$2") (pinfunction "2_P$2") (pintype "passive"))
      (node (ref "U101") (pin "64") (pinfunction "PC7_64") (pintype "bidirectional"))
    )
    (net (code "226") (name "SPI_EXT_MISO") (class "Default")
      (node (ref "J403") (pin "3") (pinfunction "3_3") (pintype "passive"))
      (node (ref "U101") (pin "4") (pinfunction "PE5_4") (pintype "bidirectional"))
    )
    (net (code "227") (name "SPI_EXT_MOSI") (class "Default")
      (node (ref "J403") (pin "4") (pinfunction "4_4") (pintype "passive"))
      (node (ref "U101") (pin "5") (pinfunction "PE6_5") (pintype "bidirectional"))
    )
    (net (code "228") (name "SPI_EXT_SCK") (class "Default")
      (node (ref "J403") (pin "2") (pinfunction "2_2") (pintype "passive"))
      (node (ref "U101") (pin "1") (pinfunction "PE2_1") (pintype "bidirectional"))
    )
    (net (code "229") (name "SPI_INT_MISO") (class "Default")
      (node (ref "U101") (pin "31") (pinfunction "PA6_31") (pintype "bidirectional"))
      (node (ref "U501") (pin "4") (pinfunction "SDO/SA0_4") (pintype "bidirectional"))
      (node (ref "U502") (pin "4") (pinfunction "SDO/SA0_4") (pintype "bidirectional"))
      (node (ref "U504") (pin "7") (pinfunction "SDO/SA0_7") (pintype "bidirectional"))
      (node (ref "U505") (pin "9") (pinfunction "AD0/SDO_9") (pintype "bidirectional"))
      (node (ref "U506") (pin "6") (pinfunction "SDO_6") (pintype "bidirectional"))
      (node (ref "X503") (pin "9") (pinfunction "S_9") (pintype "passive"))
    )
    (net (code "230") (name "SPI_INT_MOSI") (class "Default")
      (node (ref "U101") (pin "32") (pinfunction "PA7_32") (pintype "bidirectional"))
      (node (ref "U501") (pin "3") (pinfunction "SDA/SDI/SDO_3") (pintype "bidirectional"))
      (node (ref "U502") (pin "3") (pinfunction "SDA/SDI/SDO_3") (pintype "bidirectional"))
      (node (ref "U504") (pin "6") (pinfunction "SDA/SDI/SDO_6") (pintype "bidirectional"))
      (node (ref "U505") (pin "24") (pinfunction "SDA/SDI_24") (pintype "bidirectional"))
      (node (ref "U506") (pin "7") (pinfunction "SDI/SDA_7") (pintype "bidirectional"))
      (node (ref "X503") (pin "8") (pinfunction "S_8") (pintype "passive"))
    )
    (net (code "231") (name "SPI_INT_SCK") (class "Default")
      (node (ref "U101") (pin "30") (pinfunction "PA5_30") (pintype "bidirectional"))
      (node (ref "U501") (pin "2") (pinfunction "SCL/SPC_2") (pintype "input"))
      (node (ref "U502") (pin "2") (pinfunction "SCL/SPC_2") (pintype "bidirectional"))
      (node (ref "U504") (pin "4") (pinfunction "SCL/SPC_4") (pintype "bidirectional"))
      (node (ref "U505") (pin "23") (pinfunction "SCL/SCLK_23") (pintype "bidirectional"))
      (node (ref "U506") (pin "8") (pinfunction "SCLK_8") (pintype "bidirectional"))
      (node (ref "X503") (pin "10") (pinfunction "S_10") (pintype "passive"))
    )
    (net (code "232") (name "VBAT") (class "Default")
      (node (ref "B601") (pin "1") (pinfunction "POS_1") (pintype "bidirectional"))
      (node (ref "R608") (pin "P$1") (pinfunction "1_P$1") (pintype "passive"))
      (node (ref "U101") (pin "6") (pinfunction "VBAT_6") (pintype "power_in"))
      (node (ref "U801") (pin "1") (pinfunction "VBAT_1") (pintype "power_in"))
    )
    (net (code "233") (name "VBUS") (class "Default")
      (node (ref "C1103") (pin "P$1") (pinfunction "1_P$1") (pintype "passive"))
      (node (ref "J301") (pin "VBUS") (pinfunction "1_VBUS") (pintype "power_in"))
      (node (ref "J302") (pin "1") (pinfunction "1_1") (pintype "passive"))
      (node (ref "R1112") (pin "P$1") (pinfunction "1_P$1") (pintype "passive"))
      (node (ref "U101") (pin "68") (pinfunction "PA9_68") (pintype "bidirectional"))
      (node (ref "U1101") (pin "P$19") (pinfunction "V3_P$19") (pintype "bidirectional"))
      (node (ref "U1104") (pin "P$7") (pinfunction "D_P$7") (pintype "passive"))
      (node (ref "U1104") (pin "P$8") (pinfunction "D_P$8") (pintype "passive"))
      (node (ref "U302") (pin "5") (pinfunction "VBUS_5") (pintype "bidirectional"))
      (node (ref "VBUS") (pin "P$1") (pinfunction "P$1_P$1") (pintype "passive"))
    )
    (net (code "234") (name "VDD_3V3_SENSORS") (class "Default")
      (node (ref "C501") (pin "P$1") (pinfunction "1_P$1") (pintype "passive"))
      (node (ref "C502") (pin "P$1") (pinfunction "1_P$1") (pintype "passive"))
      (node (ref "C503") (pin "P$1") (pinfunction "1_P$1") (pintype "passive"))
      (node (ref "C506") (pin "P$1") (pinfunction "1_P$1") (pintype "passive"))
      (node (ref "C507") (pin "P$1") (pinfunction "1_P$1") (pintype "passive"))
      (node (ref "C508") (pin "P$1") (pinfunction "1_P$1") (pintype "passive"))
      (node (ref "C511") (pin "P$1") (pinfunction "1_P$1") (pintype "passive"))
      (node (ref "C513") (pin "P$1") (pinfunction "1_P$1") (pintype "passive"))
      (node (ref "C514") (pin "P$1") (pinfunction "1_P$1") (pintype "passive"))
      (node (ref "C605") (pin "P$1") (pinfunction "1_P$1") (pintype "passive"))
      (node (ref "C617") (pin "P$1") (pinfunction "1_P$1") (pintype "passive"))
      (node (ref "Q601") (pin "E") (pinfunction "E_E") (pintype "passive"))
      (node (ref "U501") (pin "1") (pinfunction "VDD_IO_1") (pintype "bidirectional"))
      (node (ref "U501") (pin "15") (pinfunction "RES_P15_VDD_15") (pintype "bidirectional"))
      (node (ref "U501") (pin "16") (pinfunction "VDD_16") (pintype "bidirectional"))
      (node (ref "U502") (pin "1") (pinfunction "VDD_IO_1") (pintype "bidirectional"))
      (node (ref "U502") (pin "15") (pinfunction "VDD_15") (pintype "bidirectional"))
      (node (ref "U502") (pin "16") (pinfunction "VDD_16") (pintype "bidirectional"))
      (node (ref "U504") (pin "1") (pinfunction "VDD_IO_1") (pintype "bidirectional"))
      (node (ref "U504") (pin "14") (pinfunction "VDD_14") (pintype "bidirectional"))
      (node (ref "U505") (pin "13") (pinfunction "VDD_13") (pintype "bidirectional"))
      (node (ref "U506") (pin "1") (pinfunction "VDD_1") (pintype "bidirectional"))
      (node (ref "U603") (pin "8") (pinfunction "VOUT1_8") (pintype "bidirectional"))
      (node (ref "VDDA_3V1101") (pin "P$1") (pinfunction "P$1_P$1") (pintype "passive"))
      (node (ref "X503") (pin "1") (pinfunction "S_1") (pintype "passive"))
    )
    (net (code "235") (name "VDD_3V3_SENSORS_EN") (class "Default")
      (node (ref "R603") (pin "P$2") (pinfunction "2_P$2") (pintype "passive"))
      (node (ref "R620") (pin "P$2") (pinfunction "2_P$2") (pintype "passive"))
      (node (ref "R635") (pin "P$2") (pinfunction "2_P$2") (pintype "passive"))
      (node (ref "U101") (pin "2") (pinfunction "PE3_2") (pintype "bidirectional"))
      (node (ref "U603") (pin "5") (pinfunction "EN1_5") (pintype "bidirectional"))
    )
    (net (code "236") (name "VDD_3V3_SPEKTRUM") (class "Default")
      (node (ref "C1008") (pin "P$1") (pinfunction "1_P$1") (pintype "passive"))
      (node (ref "D801") (pin "C") (pinfunction "C_C") (pintype "passive"))
      (node (ref "J801") (pin "P$1") (pinfunction "P$1_P$1") (pintype "bidirectional"))
      (node (ref "U1002") (pin "8") (pinfunction "VOUT1_8") (pintype "bidirectional"))
    )
    (net (code "237") (name "VDD_3V3_SPEKTRUM_EN") (class "Default")
      (node (ref "R1002") (pin "P$2") (pinfunction "2_P$2") (pintype "passive"))
      (node (ref "U1002") (pin "5") (pinfunction "EN1_5") (pintype "bidirectional"))
      (node (ref "U801") (pin "2") (pinfunction "PC13_2") (pintype "bidirectional"))
    )
    (net (code "238") (name "VDD_5V_BRICK") (class "Default")
      (node (ref "C1101") (pin "P$1") (pinfunction "1_P$1") (pintype "passive"))
      (node (ref "J601") (pin "1") (pinfunction "1_1") (pintype "passive"))
      (node (ref "J601") (pin "2") (pinfunction "2_2") (pintype "passive"))
      (node (ref "R1105") (pin "P$1") (pinfunction "1_P$1") (pintype "passive"))
      (node (ref "U1101") (pin "P$21") (pinfunction "V1_P$21") (pintype "bidirectional"))
      (node (ref "U1102") (pin "P$7") (pinfunction "D_P$7") (pintype "passive"))
      (node (ref "U1102") (pin "P$8") (pinfunction "D_P$8") (pintype "passive"))
      (node (ref "VDD_5V_BRICK") (pin "P$1") (pinfunction "P$1_P$1") (pintype "passive"))
    )
    (net (code "239") (name "VDD_5V_HIPOWER") (class "Default")
      (node (ref "C614") (pin "P$1") (pinfunction "1_P$1") (pintype "passive"))
      (node (ref "L201") (pin "P$1") (pinfunction "P$1_P$1") (pintype "bidirectional"))
      (node (ref "U601") (pin "8") (pinfunction "OUT_8") (pintype "bidirectional"))
    )
    (net (code "240") (name "VDD_5V_IN") (class "Default")
      (node (ref "C1104") (pin "P$1") (pinfunction "1_P$1") (pintype "passive"))
      (node (ref "C702") (pin "P$1") (pinfunction "1_P$1") (pintype "passive"))
      (node (ref "F1001") (pin "1") (pinfunction "1_1") (pintype "bidirectional"))
      (node (ref "L603") (pin "P$1") (pinfunction "P$1_P$1") (pintype "bidirectional"))
      (node (ref "L701") (pin "P$1") (pinfunction "1_P$1") (pintype "passive"))
      (node (ref "LED701") (pin "A") (pinfunction "A_A") (pintype "passive"))
      (node (ref "LED704") (pin "A") (pinfunction "A_A") (pintype "passive"))
      (node (ref "R609") (pin "P$2") (pinfunction "2_P$2") (pintype "passive"))
      (node (ref "RN1101") (pin "5") (pinfunction "2_5") (pintype "passive"))
      (node (ref "RN1101") (pin "6") (pinfunction "2_6") (pintype "passive"))
      (node (ref "RN1101") (pin "7") (pinfunction "2_7") (pintype "passive"))
      (node (ref "U1101") (pin "P$12") (pinfunction "VOUT_P$12") (pintype "bidirectional"))
      (node (ref "U1102") (pin "P$5") (pinfunction "D_P$5") (pintype "passive"))
      (node (ref "U1102") (pin "P$6") (pinfunction "D_P$6") (pintype "passive"))
      (node (ref "U1103") (pin "P$5") (pinfunction "D_P$5") (pintype "passive"))
      (node (ref "U1103") (pin "P$6") (pinfunction "D_P$6") (pintype "passive"))
      (node (ref "U1104") (pin "P$5") (pinfunction "D_P$5") (pintype "passive"))
      (node (ref "U1104") (pin "P$6") (pinfunction "D_P$6") (pintype "passive"))
      (node (ref "U601") (pin "1") (pinfunction "IN_1") (pintype "bidirectional"))
      (node (ref "U602") (pin "1") (pinfunction "IN_1") (pintype "bidirectional"))
      (node (ref "U702") (pin "3") (pinfunction "VIN_3") (pintype "power_in"))
      (node (ref "U703") (pin "A1") (pinfunction "A_A1") (pintype "passive"))
      (node (ref "U703") (pin "A2") (pinfunction "A_A2") (pintype "passive"))
      (node (ref "U703") (pin "A3") (pinfunction "A_A3") (pintype "passive"))
      (node (ref "VDD_5V_IN") (pin "P$1") (pinfunction "P$1_P$1") (pintype "passive"))
    )
    (net (code "241") (name "VDD_5V_PERIPH") (class "Default")
      (node (ref "C618") (pin "P$1") (pinfunction "1_P$1") (pintype "passive"))
      (node (ref "L202") (pin "P$1") (pinfunction "P$1_P$1") (pintype "bidirectional"))
      (node (ref "L203") (pin "P$1") (pinfunction "P$1_P$1") (pintype "bidirectional"))
      (node (ref "L401") (pin "P$1") (pinfunction "P$1_P$1") (pintype "bidirectional"))
      (node (ref "L402") (pin "P$1") (pinfunction "P$1_P$1") (pintype "bidirectional"))
      (node (ref "L403") (pin "P$1") (pinfunction "P$1_P$1") (pintype "bidirectional"))
      (node (ref "L404") (pin "P$1") (pinfunction "P$1_P$1") (pintype "bidirectional"))
      (node (ref "U602") (pin "8") (pinfunction "OUT_8") (pintype "bidirectional"))
    )
    (net (code "242") (name "VDD_5V_SENS") (class "Default")
      (node (ref "R609") (pin "P$1") (pinfunction "1_P$1") (pintype "passive"))
      (node (ref "R610") (pin "P$1") (pinfunction "1_P$1") (pintype "passive"))
      (node (ref "U101") (pin "29") (pinfunction "PA4_29") (pintype "bidirectional"))
    )
    (net (code "243") (name "VDD_SERVO") (class "Default")
      (node (ref "C1102") (pin "P$1") (pinfunction "1_P$1") (pintype "passive"))
      (node (ref "D904") (pin "ANODE") (pinfunction "A_ANODE") (pintype "passive"))
      (node (ref "J901") (pin "11") (pinfunction "S_11") (pintype "passive"))
      (node (ref "J901") (pin "14") (pinfunction "S_14") (pintype "passive"))
      (node (ref "J901") (pin "17") (pinfunction "S_17") (pintype "passive"))
      (node (ref "J901") (pin "20") (pinfunction "S_20") (pintype "passive"))
      (node (ref "J901") (pin "23") (pinfunction "S_23") (pintype "passive"))
      (node (ref "J901") (pin "26") (pinfunction "S_26") (pintype "passive"))
      (node (ref "J901") (pin "29") (pinfunction "S_29") (pintype "passive"))
      (node (ref "J901") (pin "32") (pinfunction "S_32") (pintype "passive"))
      (node (ref "J901") (pin "35") (pinfunction "S_35") (pintype "passive"))
      (node (ref "J901") (pin "38") (pinfunction "S_38") (pintype "passive"))
      (node (ref "J901") (pin "41") (pinfunction "S_41") (pintype "passive"))
      (node (ref "J901") (pin "44") (pinfunction "S_44") (pintype "passive"))
      (node (ref "J901") (pin "47") (pinfunction "S_47") (pintype "passive"))
      (node (ref "J901") (pin "5") (pinfunction "S_5") (pintype "passive"))
      (node (ref "J901") (pin "8") (pinfunction "S_8") (pintype "passive"))
      (node (ref "R1109") (pin "P$1") (pinfunction "1_P$1") (pintype "passive"))
      (node (ref "R922") (pin "P$2") (pinfunction "2_P$2") (pintype "passive"))
      (node (ref "U1101") (pin "P$20") (pinfunction "V2_P$20") (pintype "bidirectional"))
      (node (ref "U1103") (pin "P$7") (pinfunction "D_P$7") (pintype "passive"))
      (node (ref "U1103") (pin "P$8") (pinfunction "D_P$8") (pintype "passive"))
      (node (ref "VDD_SERVO") (pin "P$1") (pinfunction "P$1_P$1") (pintype "passive"))
    )
    (net (code "244") (name "VDD_SERVO_IN") (class "Default")
      (node (ref "L901") (pin "P$2") (pinfunction "P$2_P$2") (pintype "bidirectional"))
      (node (ref "U1001") (pin "1") (pinfunction "IN_1") (pintype "bidirectional"))
    )
    (net (code "245") (name "VDD_SERVO_SENS") (class "Default")
      (node (ref "R918") (pin "P$1") (pinfunction "1_P$1") (pintype "passive"))
      (node (ref "R919") (pin "P$2") (pinfunction "2_P$2") (pintype "passive"))
      (node (ref "U801") (pin "14") (pinfunction "PA4_14") (pintype "bidirectional"))
    )
    (net (code "246") (name "unconnected-(J301-4-PadID)") (class "Default")
      (node (ref "J301") (pin "ID") (pinfunction "4_ID") (pintype "passive"))
    )
    (net (code "247") (name "unconnected-(JX301A-S-Pad10)") (class "Default")
      (node (ref "JX301") (pin "10") (pinfunction "S_10") (pintype "passive"))
    )
    (net (code "248") (name "unconnected-(JX301F-S-Pad8)") (class "Default")
      (node (ref "JX301") (pin "8") (pinfunction "S_8") (pintype "passive"))
    )
    (net (code "249") (name "unconnected-(JX802A-S-Pad10)") (class "Default")
      (node (ref "JX802") (pin "10") (pinfunction "S_10") (pintype "passive"))
    )
    (net (code "250") (name "unconnected-(JX802F-S-Pad8)") (class "Default")
      (node (ref "JX802") (pin "8") (pinfunction "S_8") (pintype "passive"))
    )
    (net (code "251") (name "unconnected-(U101I-PC1-Pad16)") (class "Default")
      (node (ref "U101") (pin "16") (pinfunction "PC1_16") (pintype "bidirectional"))
    )
    (net (code "252") (name "unconnected-(U202-A1-Pad1)") (class "Default")
      (node (ref "U202") (pin "1") (pinfunction "A1_1") (pintype "bidirectional"))
    )
    (net (code "253") (name "unconnected-(U202-A2-Pad3)") (class "Default")
      (node (ref "U202") (pin "3") (pinfunction "A2_3") (pintype "bidirectional"))
    )
    (net (code "254") (name "unconnected-(U202-B1-Pad20)") (class "Default")
      (node (ref "U202") (pin "20") (pinfunction "B1_20") (pintype "bidirectional"))
    )
    (net (code "255") (name "unconnected-(U202-B2-Pad18)") (class "Default")
      (node (ref "U202") (pin "18") (pinfunction "B2_18") (pintype "bidirectional"))
    )
    (net (code "256") (name "unconnected-(U501-INT1-Pad7)") (class "Default")
      (node (ref "U501") (pin "7") (pinfunction "INT1_7") (pintype "output"))
    )
    (net (code "257") (name "unconnected-(U502-DEN-Pad8)") (class "Default")
      (node (ref "U502") (pin "8") (pinfunction "DEN_8") (pintype "bidirectional"))
    )
    (net (code "258") (name "unconnected-(U502-INT1-Pad7)") (class "Default")
      (node (ref "U502") (pin "7") (pinfunction "INT1_7") (pintype "bidirectional"))
    )
    (net (code "259") (name "unconnected-(U505-AUX_CL-Pad7)") (class "Default")
      (node (ref "U505") (pin "7") (pinfunction "AUX_CL_7") (pintype "bidirectional"))
    )
    (net (code "260") (name "unconnected-(U505-AUX_DA-Pad6)") (class "Default")
      (node (ref "U505") (pin "6") (pinfunction "AUX_DA_6") (pintype "bidirectional"))
    )
    (net (code "261") (name "unconnected-(U505-CLKOUT-Pad22)") (class "Default")
      (node (ref "U505") (pin "22") (pinfunction "CLKOUT_22") (pintype "bidirectional"))
    )
    (net (code "262") (name "unconnected-(U505-FSYNC-Pad11)") (class "Default")
      (node (ref "U505") (pin "11") (pinfunction "FSYNC_11") (pintype "bidirectional"))
    )
    (net (code "263") (name "unconnected-(U505-NC1-Pad2)") (class "Default")
      (node (ref "U505") (pin "2") (pinfunction "NC1_2") (pintype "bidirectional"))
    )
    (net (code "264") (name "unconnected-(U505-NC2-Pad3)") (class "Default")
      (node (ref "U505") (pin "3") (pinfunction "NC2_3") (pintype "bidirectional"))
    )
    (net (code "265") (name "unconnected-(U505-NC3-Pad4)") (class "Default")
      (node (ref "U505") (pin "4") (pinfunction "NC3_4") (pintype "bidirectional"))
    )
    (net (code "266") (name "unconnected-(U505-NC4-Pad5)") (class "Default")
      (node (ref "U505") (pin "5") (pinfunction "NC4_5") (pintype "bidirectional"))
    )
    (net (code "267") (name "unconnected-(U505-NC5-Pad14)") (class "Default")
      (node (ref "U505") (pin "14") (pinfunction "NC5_14") (pintype "bidirectional"))
    )
    (net (code "268") (name "unconnected-(U505-NC6-Pad15)") (class "Default")
      (node (ref "U505") (pin "15") (pinfunction "NC6_15") (pintype "bidirectional"))
    )
    (net (code "269") (name "unconnected-(U505-NC7-Pad16)") (class "Default")
      (node (ref "U505") (pin "16") (pinfunction "NC7_16") (pintype "bidirectional"))
    )
    (net (code "270") (name "unconnected-(U505-NC8-Pad17)") (class "Default")
      (node (ref "U505") (pin "17") (pinfunction "NC8_17") (pintype "bidirectional"))
    )
    (net (code "271") (name "unconnected-(U505-RESV1-Pad19)") (class "Default")
      (node (ref "U505") (pin "19") (pinfunction "RESV1_19") (pintype "bidirectional"))
    )
    (net (code "272") (name "unconnected-(U505-RESV2-Pad21)") (class "Default")
      (node (ref "U505") (pin "21") (pinfunction "RESV2_21") (pintype "bidirectional"))
    )
    (net (code "273") (name "unconnected-(U506-CSB1-Pad4)") (class "Default")
      (node (ref "U506") (pin "4") (pinfunction "CSB1_4") (pintype "bidirectional"))
    )
    (net (code "274") (name "unconnected-(U801B-PA11-Pad32)") (class "Default")
      (node (ref "U801") (pin "32") (pinfunction "PA11_32") (pintype "bidirectional"))
    )
    (net (code "275") (name "unconnected-(U801D-PB12-Pad25)") (class "Default")
      (node (ref "U801") (pin "25") (pinfunction "PB12_25") (pintype "bidirectional"))
    )
    (net (code "276") (name "unconnected-(U801E-PB6-Pad42)") (class "Default")
      (node (ref "U801") (pin "42") (pinfunction "PB6_42") (pintype "bidirectional"))
    )
    (net (code "277") (name "unconnected-(U801E-PB7-Pad43)") (class "Default")
      (node (ref "U801") (pin "43") (pinfunction "PB7_43") (pintype "bidirectional"))
    )
    (net (code "278") (name "unconnected-(U801F-PC14-Pad3)") (class "Default")
      (node (ref "U801") (pin "3") (pinfunction "PC14_3") (pintype "bidirectional"))
    )
    (net (code "279") (name "unconnected-(U801F-PC15-Pad4)") (class "Default")
      (node (ref "U801") (pin "4") (pinfunction "PC15_4") (pintype "bidirectional"))
    )
    (net (code "280") (name "unconnected-(U901-A7-Pad8)") (class "Default")
      (node (ref "U901") (pin "8") (pinfunction "A7_8") (pintype "bidirectional"))
    )
    (net (code "281") (name "unconnected-(U901-A8-Pad9)") (class "Default")
      (node (ref "U901") (pin "9") (pinfunction "A8_9") (pintype "bidirectional"))
    )
    (net (code "282") (name "unconnected-(U901-B7-Pad13)") (class "Default")
      (node (ref "U901") (pin "13") (pinfunction "B7_13") (pintype "bidirectional"))
    )
    (net (code "283") (name "unconnected-(U901-B8-Pad12)") (class "Default")
      (node (ref "U901") (pin "12") (pinfunction "B8_12") (pintype "bidirectional"))
    )
    (net (code "284") (name "unconnected-(U1101-CAS-PadP$11)") (class "Default")
      (node (ref "U1101") (pin "P$11") (pinfunction "CAS_P$11") (pintype "bidirectional"))
    )
    (net (code "285") (name "unconnected-(U1101-EN-PadP$22)") (class "Default")
      (node (ref "U1101") (pin "P$22") (pinfunction "EN_P$22") (pintype "bidirectional"))
    )
    (net (code "286") (name "unconnected-(U1101-~{SHDN}-PadP$23)") (class "Default")
      (node (ref "U1101") (pin "P$23") (pinfunction "~{SHDN}_P$23") (pintype "bidirectional"))
    )
    (net (code "287") (name "~{ACCEL_MAG_CS}") (class "Default")
      (node (ref "U101") (pin "9") (pinfunction "PC15_9") (pintype "bidirectional"))
      (node (ref "U504") (pin "8") (pinfunction "CS_8") (pintype "bidirectional"))
      (node (ref "X503") (pin "6") (pinfunction "S_6") (pintype "passive"))
    )
    (net (code "288") (name "~{BARO_CS}") (class "Default")
      (node (ref "U101") (pin "88") (pinfunction "PD7_88") (pintype "bidirectional"))
      (node (ref "U506") (pin "5") (pinfunction "CSB2_5") (pintype "bidirectional"))
    )
    (net (code "289") (name "~{FMU-LED_AMBER}") (class "Default")
      (node (ref "R707") (pin "P$1") (pinfunction "1_P$1") (pintype "passive"))
      (node (ref "U101") (pin "43") (pinfunction "PE12_43") (pintype "bidirectional"))
    )
    (net (code "290") (name "~{FRAM_CS}") (class "Default")
      (node (ref "U101") (pin "57") (pinfunction "PD10_57") (pintype "bidirectional"))
      (node (ref "U102") (pin "1") (pinfunction "~{S}_1") (pintype "bidirectional"))
    )
    (net (code "291") (name "~{GYRO_CS}") (class "Default")
      (node (ref "U101") (pin "7") (pinfunction "PC13_7") (pintype "bidirectional"))
      (node (ref "U501") (pin "5") (pinfunction "CS_5") (pintype "input"))
      (node (ref "U502") (pin "5") (pinfunction "CS_5") (pintype "bidirectional"))
      (node (ref "X503") (pin "7") (pinfunction "S_7") (pintype "passive"))
    )
    (net (code "292") (name "~{IO-LED_AMBER}") (class "Default")
      (node (ref "R709") (pin "P$1") (pinfunction "1_P$1") (pintype "passive"))
      (node (ref "U801") (pin "28") (pinfunction "PB15_28") (pintype "bidirectional"))
    )
    (net (code "293") (name "~{IO-LED_BLUE}") (class "Default")
      (node (ref "R712") (pin "P$1") (pinfunction "1_P$1") (pintype "passive"))
      (node (ref "U801") (pin "27") (pinfunction "PB14_27") (pintype "bidirectional"))
    )
    (net (code "294") (name "~{IO-LED_SAFETY}") (class "Default")
      (node (ref "R710") (pin "P$2") (pinfunction "2_P$2") (pintype "passive"))
      (node (ref "U801") (pin "26") (pinfunction "PB13_26") (pintype "bidirectional"))
    )
    (net (code "295") (name "~{MPU_CS}") (class "Default")
      (node (ref "U101") (pin "17") (pinfunction "PC2_17") (pintype "bidirectional"))
      (node (ref "U505") (pin "8") (pinfunction "/CS_8") (pintype "bidirectional"))
    )
    (net (code "296") (name "~{SBUS_OUTPUT_EN}") (class "Default")
      (node (ref "U801") (pin "40") (pinfunction "PB4_40") (pintype "bidirectional"))
      (node (ref "U903") (pin "7") (pinfunction "~{2OE}_7") (pintype "input"))
    )
    (net (code "297") (name "~{SPI_EXT_NSS}") (class "Default")
      (node (ref "J403") (pin "5") (pinfunction "5_5") (pintype "passive"))
      (node (ref "U101") (pin "3") (pinfunction "PE4_3") (pintype "bidirectional"))
    )
    (net (code "298") (name "~{VBUS_VALID}") (class "Default")
      (node (ref "!VBUS_VALID") (pin "P$1") (pinfunction "P$1_P$1") (pintype "passive"))
      (node (ref "RN1101") (pin "2") (pinfunction "1_2") (pintype "passive"))
      (node (ref "U101") (pin "15") (pinfunction "PC0_15") (pintype "bidirectional"))
      (node (ref "U1101") (pin "P$9") (pinfunction "~{VALID3}_P$9") (pintype "bidirectional"))
    )
    (net (code "299") (name "~{VDD_5V_HIPOWER_OC}") (class "Default")
      (node (ref "R602") (pin "P$1") (pinfunction "1_P$1") (pintype "passive"))
      (node (ref "U101") (pin "41") (pinfunction "PE10_41") (pintype "bidirectional"))
      (node (ref "U601") (pin "4") (pinfunction "~{FAULT}_4") (pintype "bidirectional"))
    )
    (net (code "300") (name "~{VDD_5V_PERIPH_EN}") (class "Default")
      (node (ref "R615") (pin "P$1") (pinfunction "1_P$1") (pintype "passive"))
      (node (ref "U101") (pin "67") (pinfunction "PA8_67") (pintype "bidirectional"))
      (node (ref "U601") (pin "5") (pinfunction "~{CE}_5") (pintype "bidirectional"))
      (node (ref "U602") (pin "5") (pinfunction "~{CE}_5") (pintype "bidirectional"))
    )
    (net (code "301") (name "~{VDD_5V_PERIPH_OC}") (class "Default")
      (node (ref "R604") (pin "P$1") (pinfunction "1_P$1") (pintype "passive"))
      (node (ref "U101") (pin "46") (pinfunction "PE15_46") (pintype "bidirectional"))
      (node (ref "U602") (pin "4") (pinfunction "~{FAULT}_4") (pintype "bidirectional"))
    )
    (net (code "302") (name "~{VDD_BRICK_VALID}") (class "Default")
      (node (ref "!VDD_BRICK_VALID") (pin "P$1") (pinfunction "P$1_P$1") (pintype "passive"))
      (node (ref "RN1101") (pin "4") (pinfunction "1_4") (pintype "passive"))
      (node (ref "U101") (pin "91") (pinfunction "PB5_91") (pintype "bidirectional"))
      (node (ref "U1101") (pin "P$7") (pinfunction "~{VALID1}_P$7") (pintype "bidirectional"))
    )
    (net (code "303") (name "~{VDD_SERVO_VALID}") (class "Default")
      (node (ref "!VDD_SERVO_VALID") (pin "P$1") (pinfunction "P$1_P$1") (pintype "passive"))
      (node (ref "RN1101") (pin "3") (pinfunction "1_3") (pintype "passive"))
      (node (ref "U101") (pin "93") (pinfunction "PB7_93") (pintype "bidirectional"))
      (node (ref "U1101") (pin "P$8") (pinfunction "~{VALID2}_P$8") (pintype "bidirectional"))
    )
  )
)
